# SCH_ReA4091_Rev3_20221019.net
KiCad netlist of a schematic drawn in EasyEDA
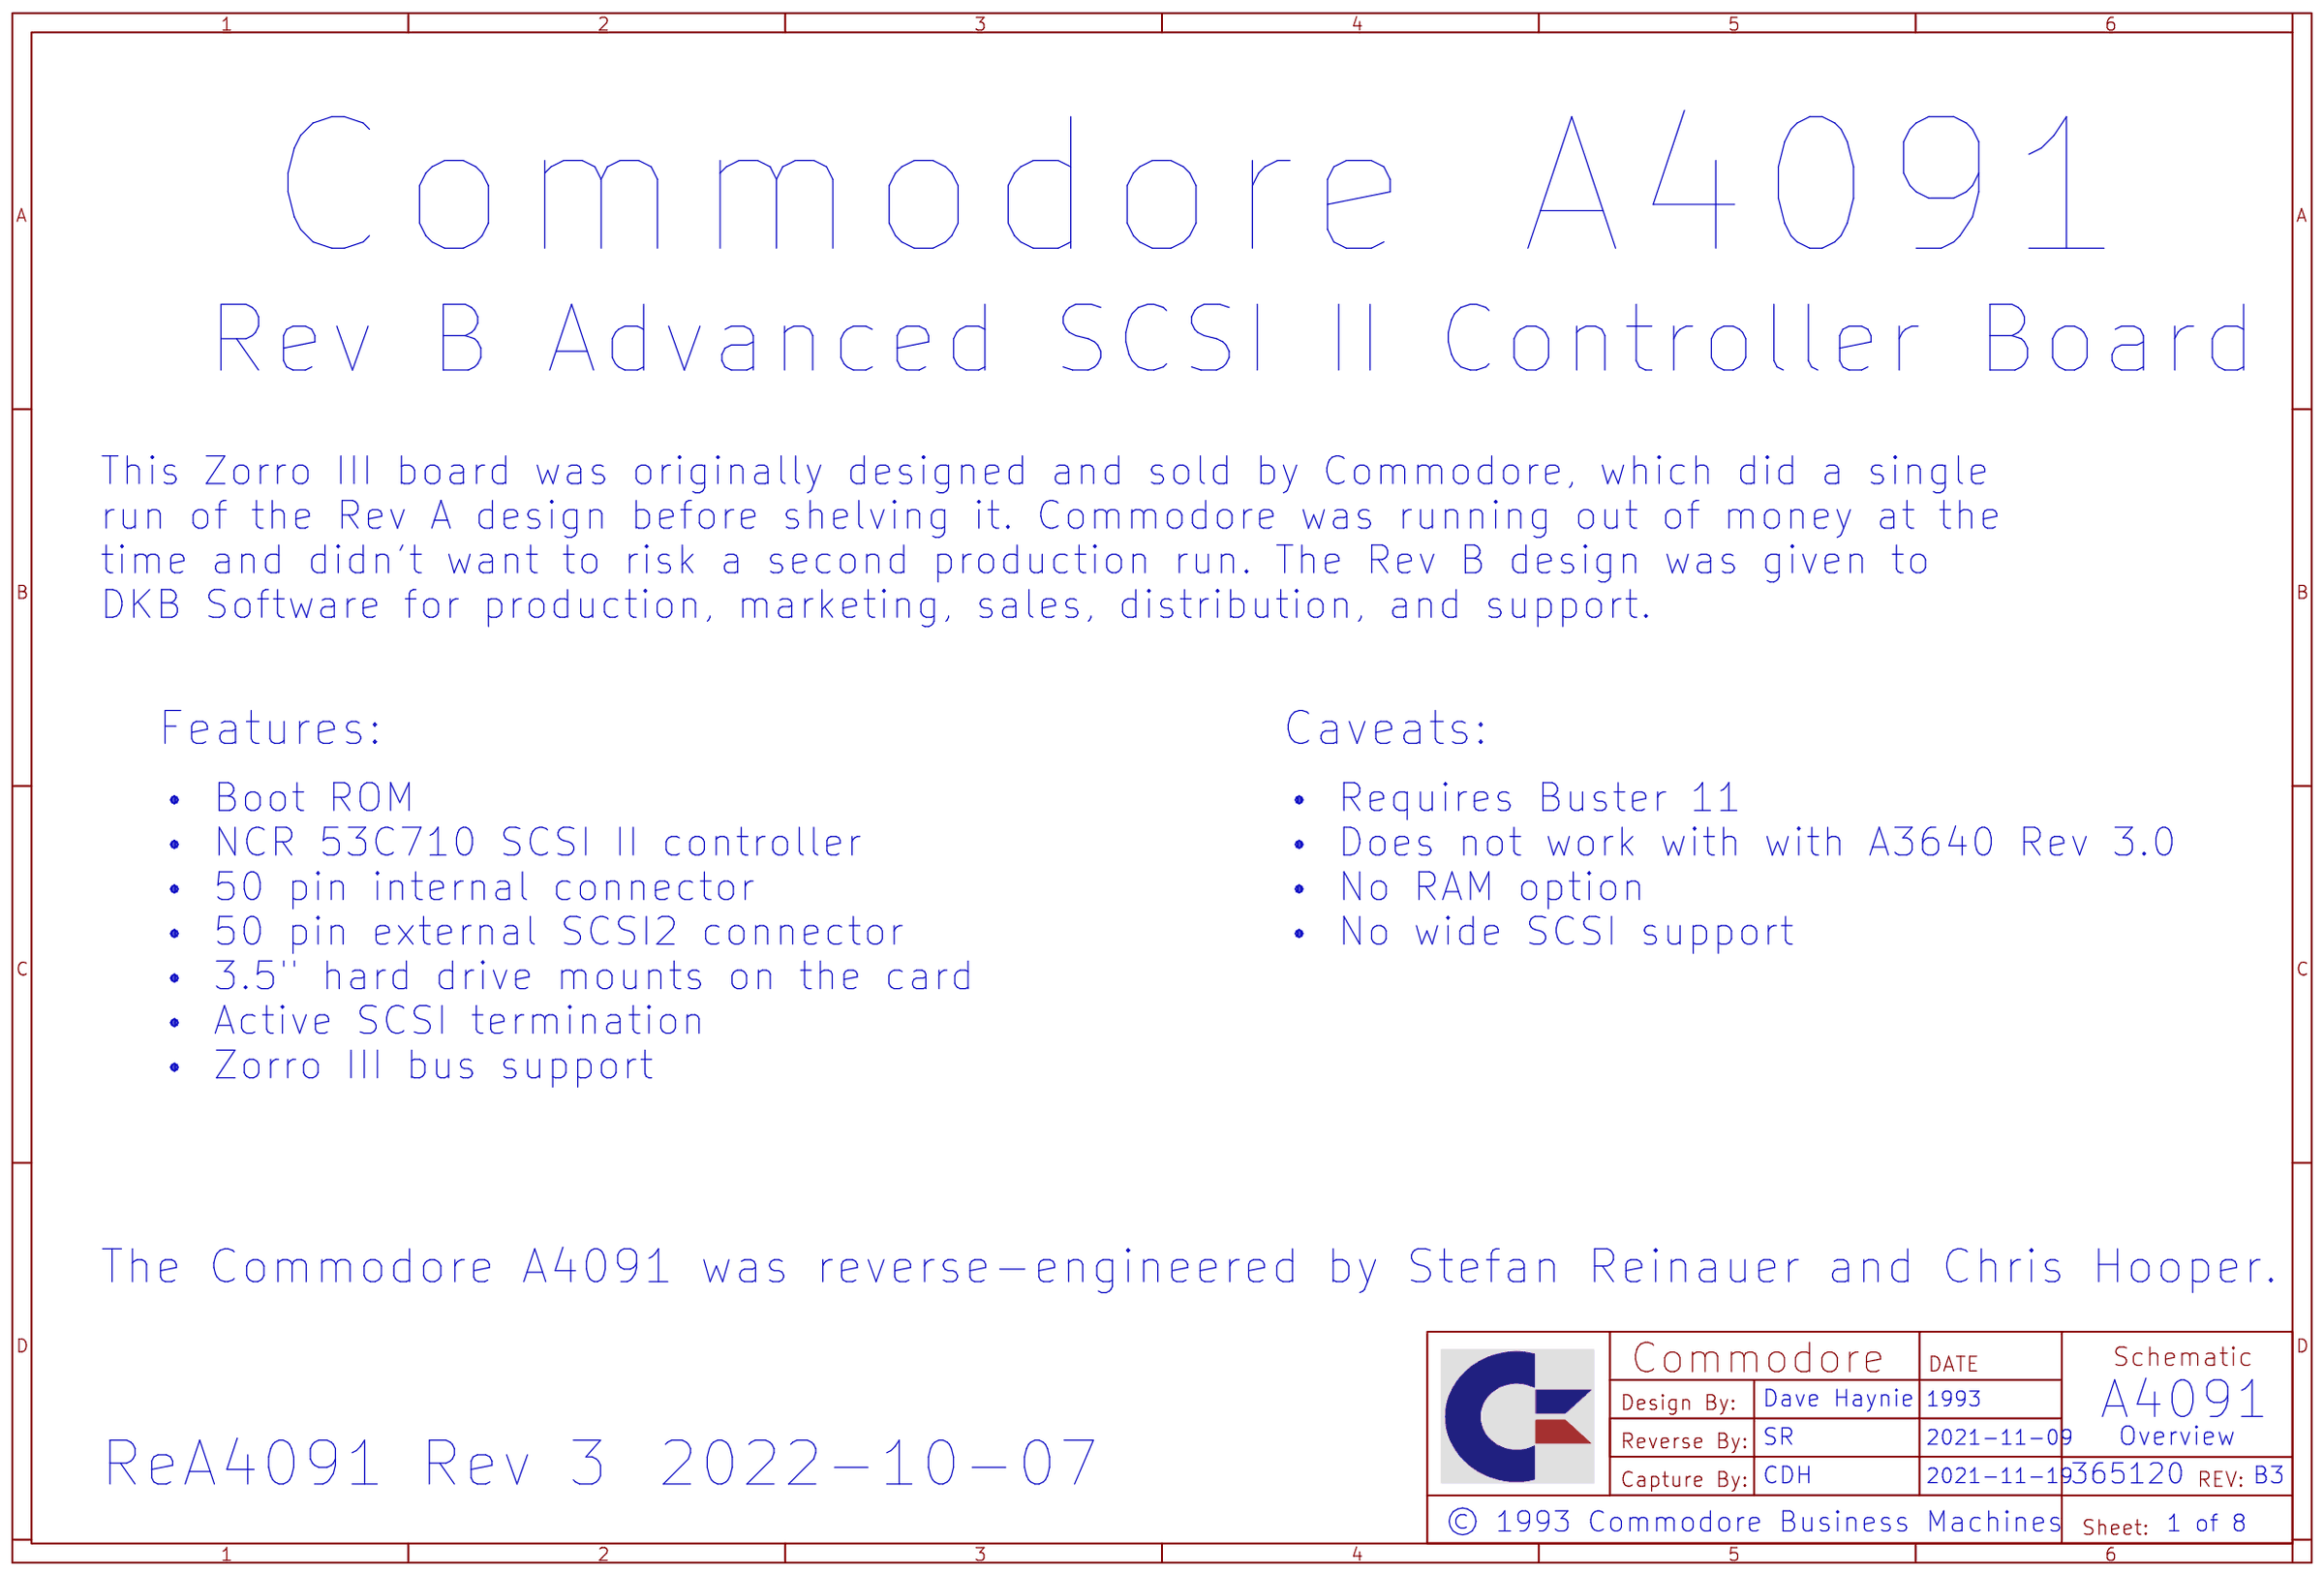
[diagram p0: Overview]
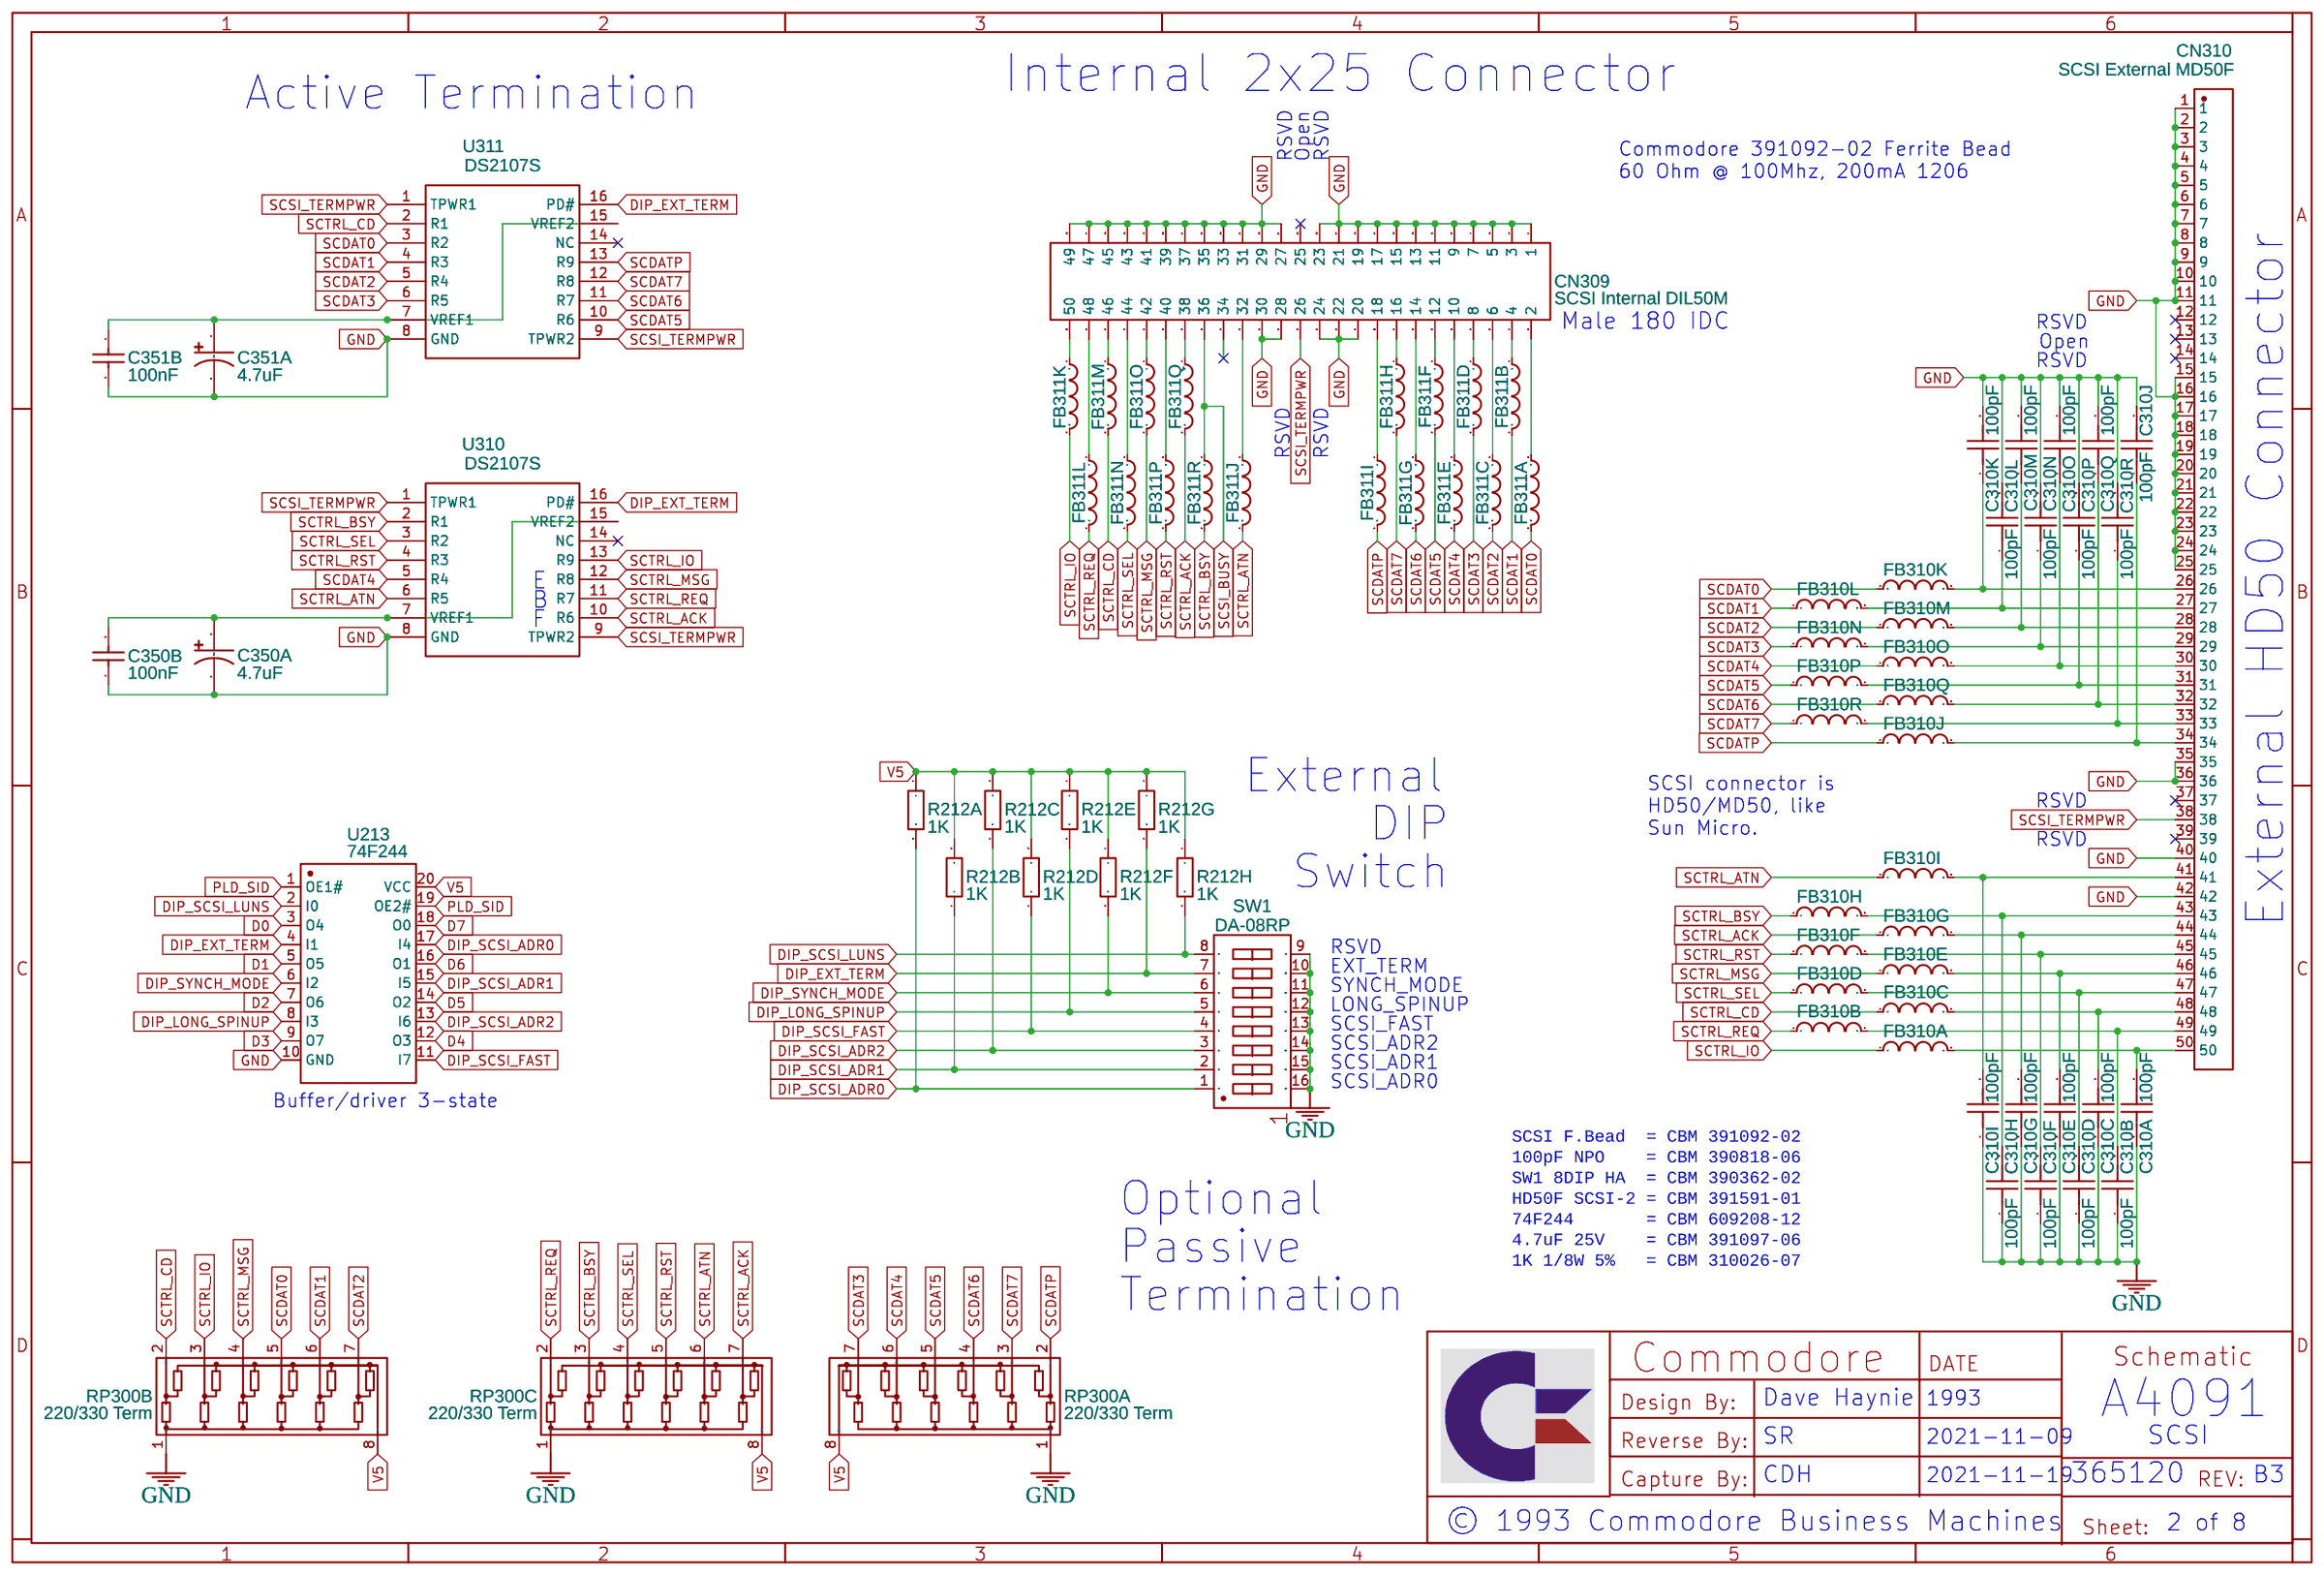
[diagram p1: SCSI]
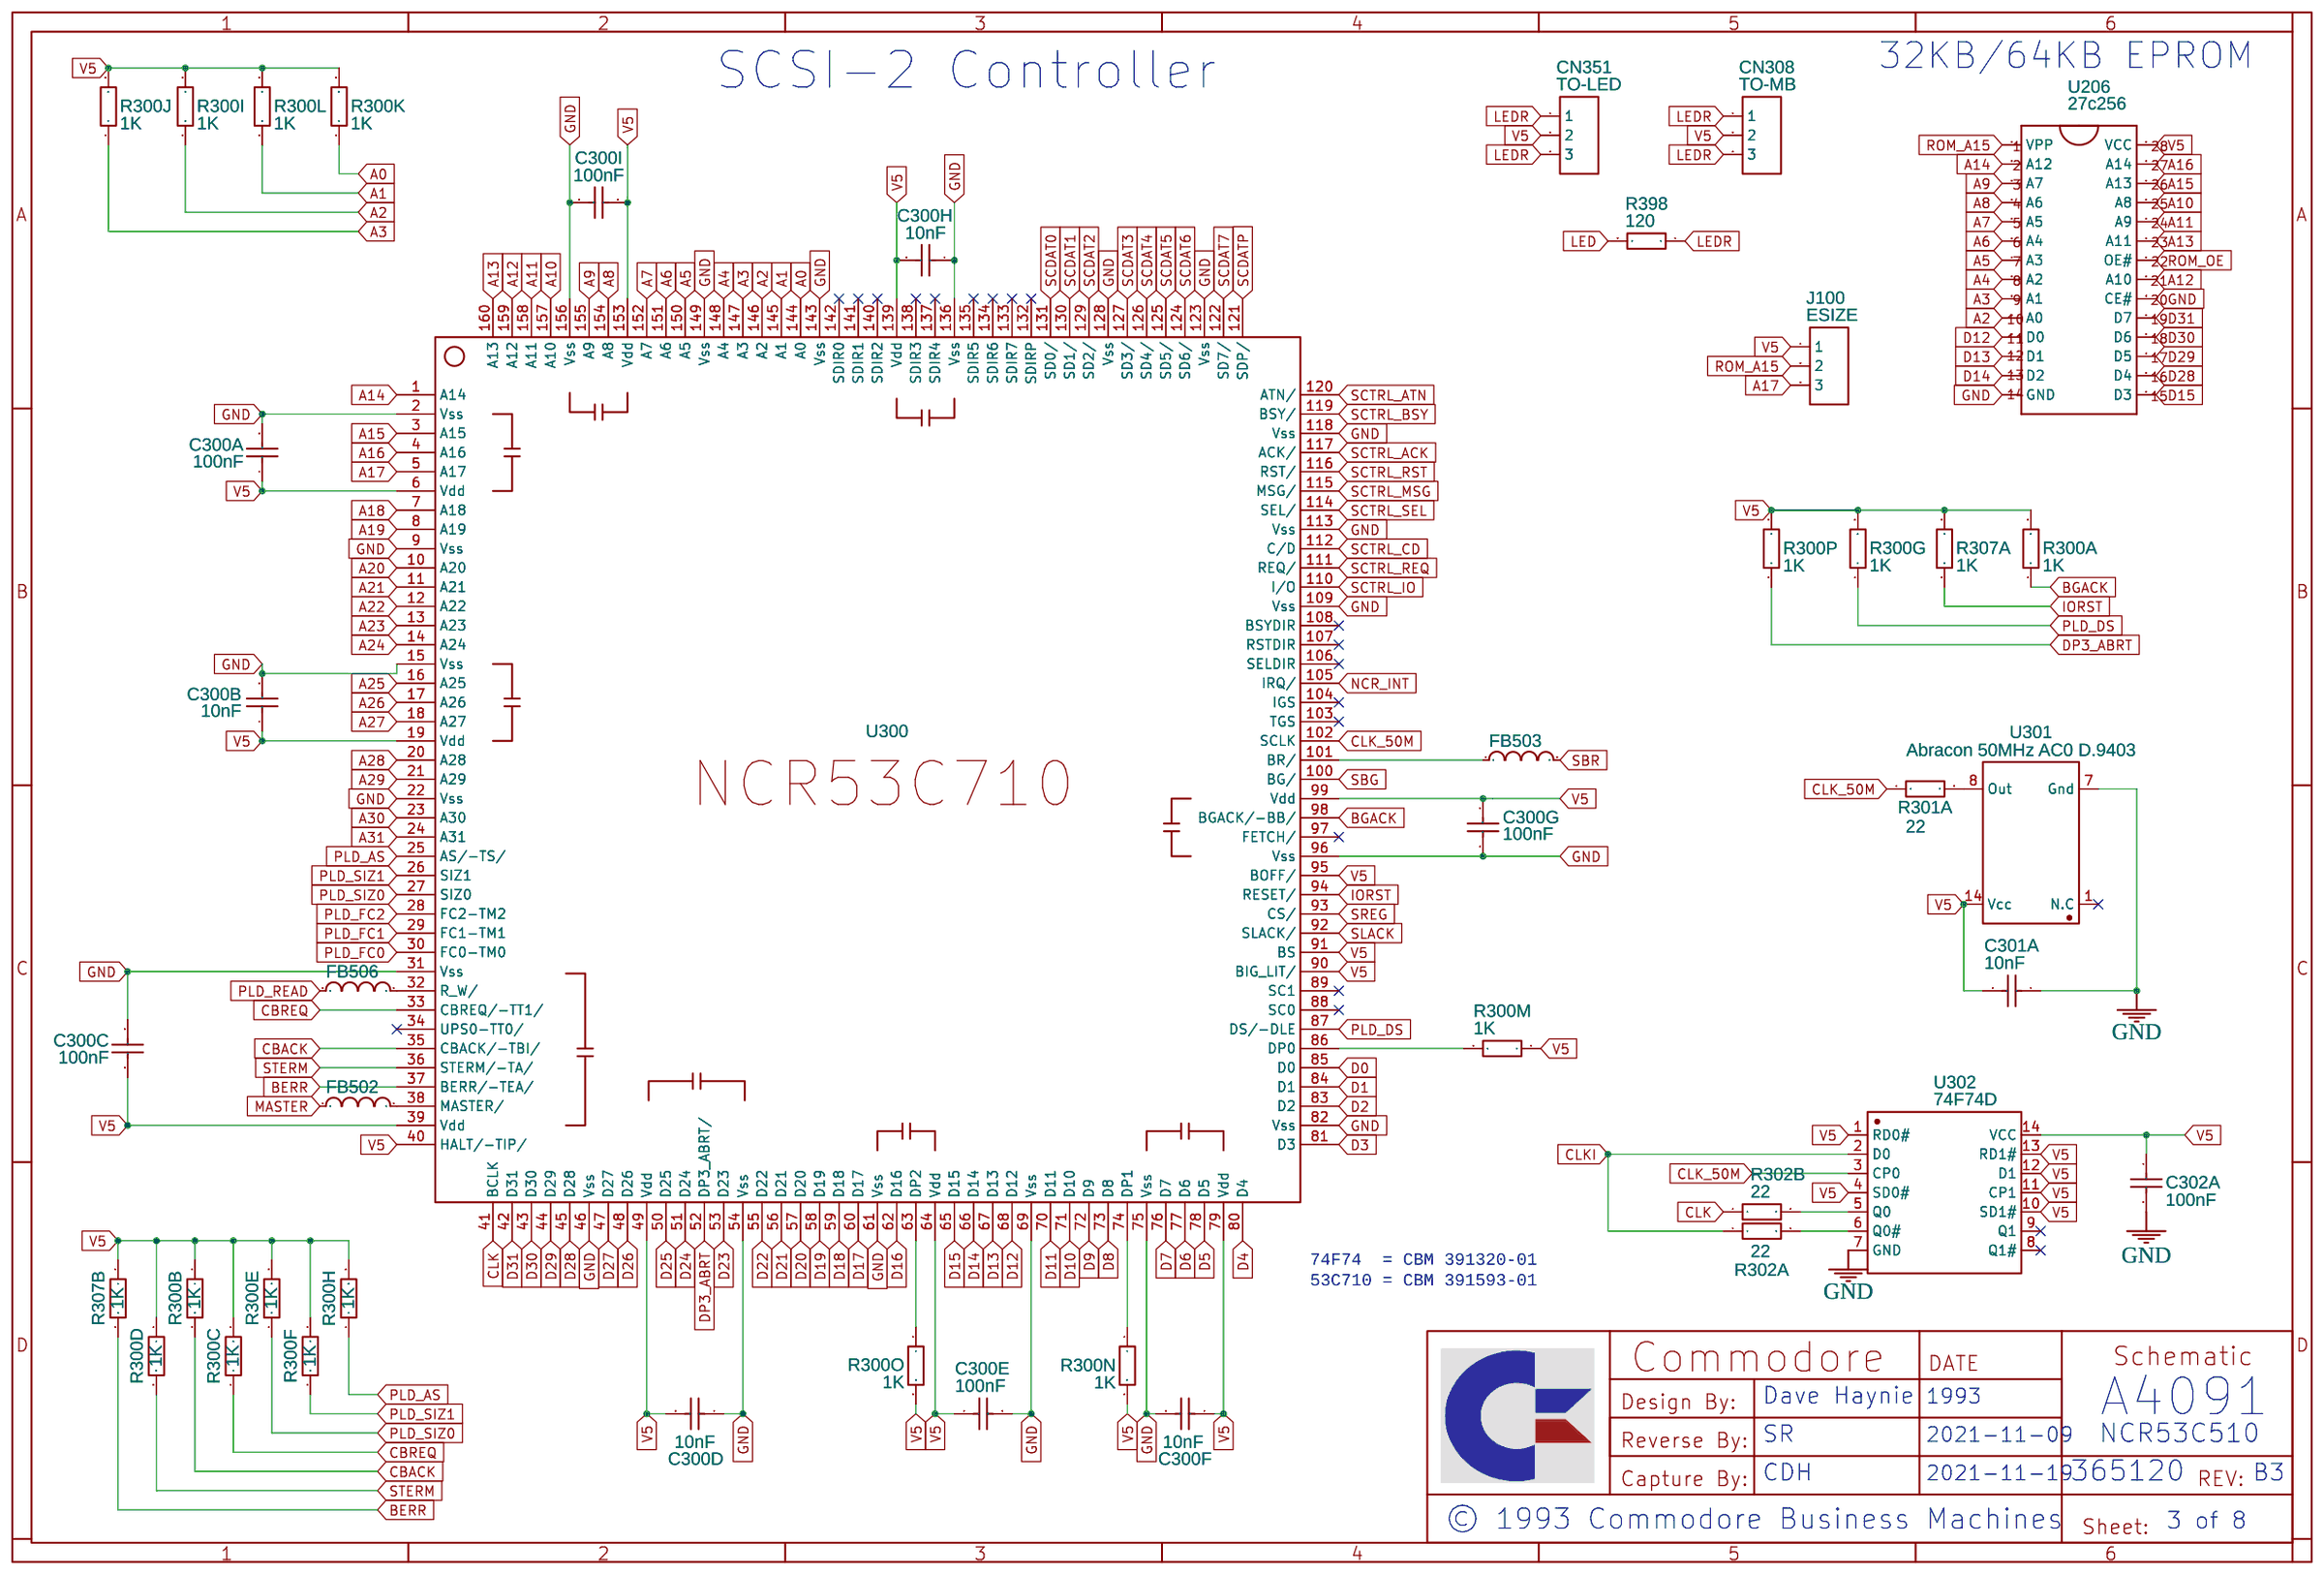
[diagram p2: NCR53C710]
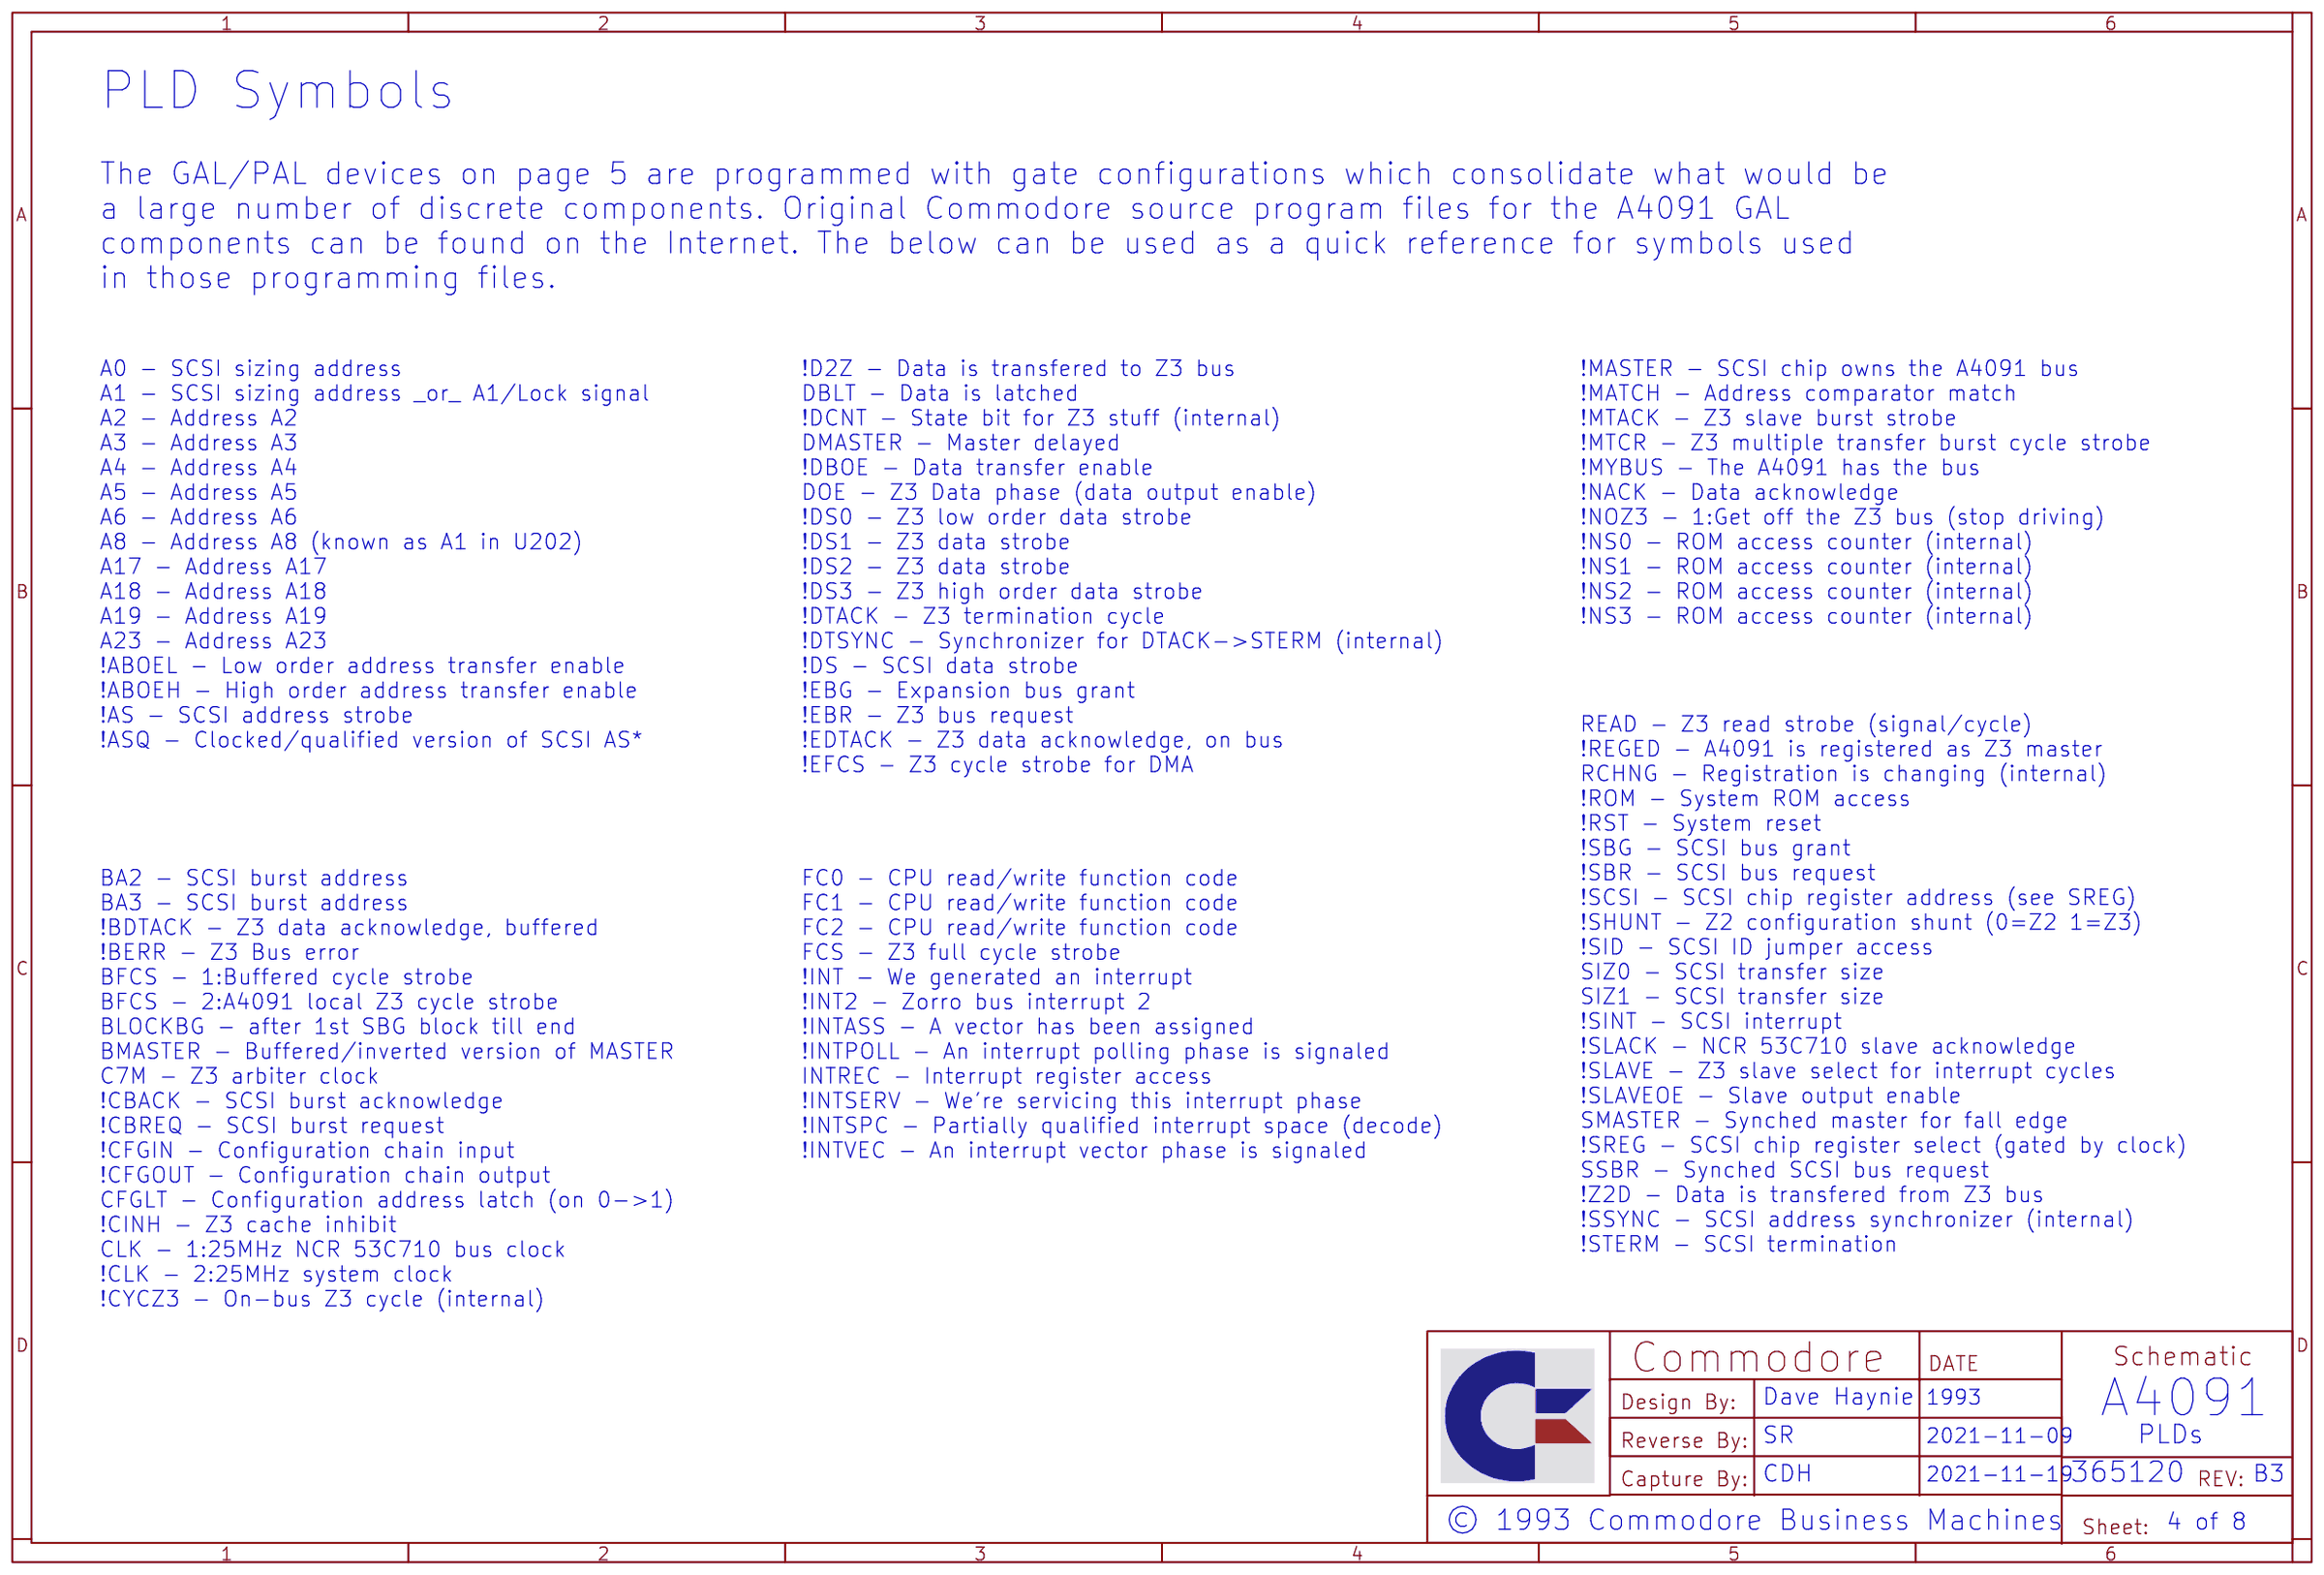
[diagram p3: PLD Symbols]
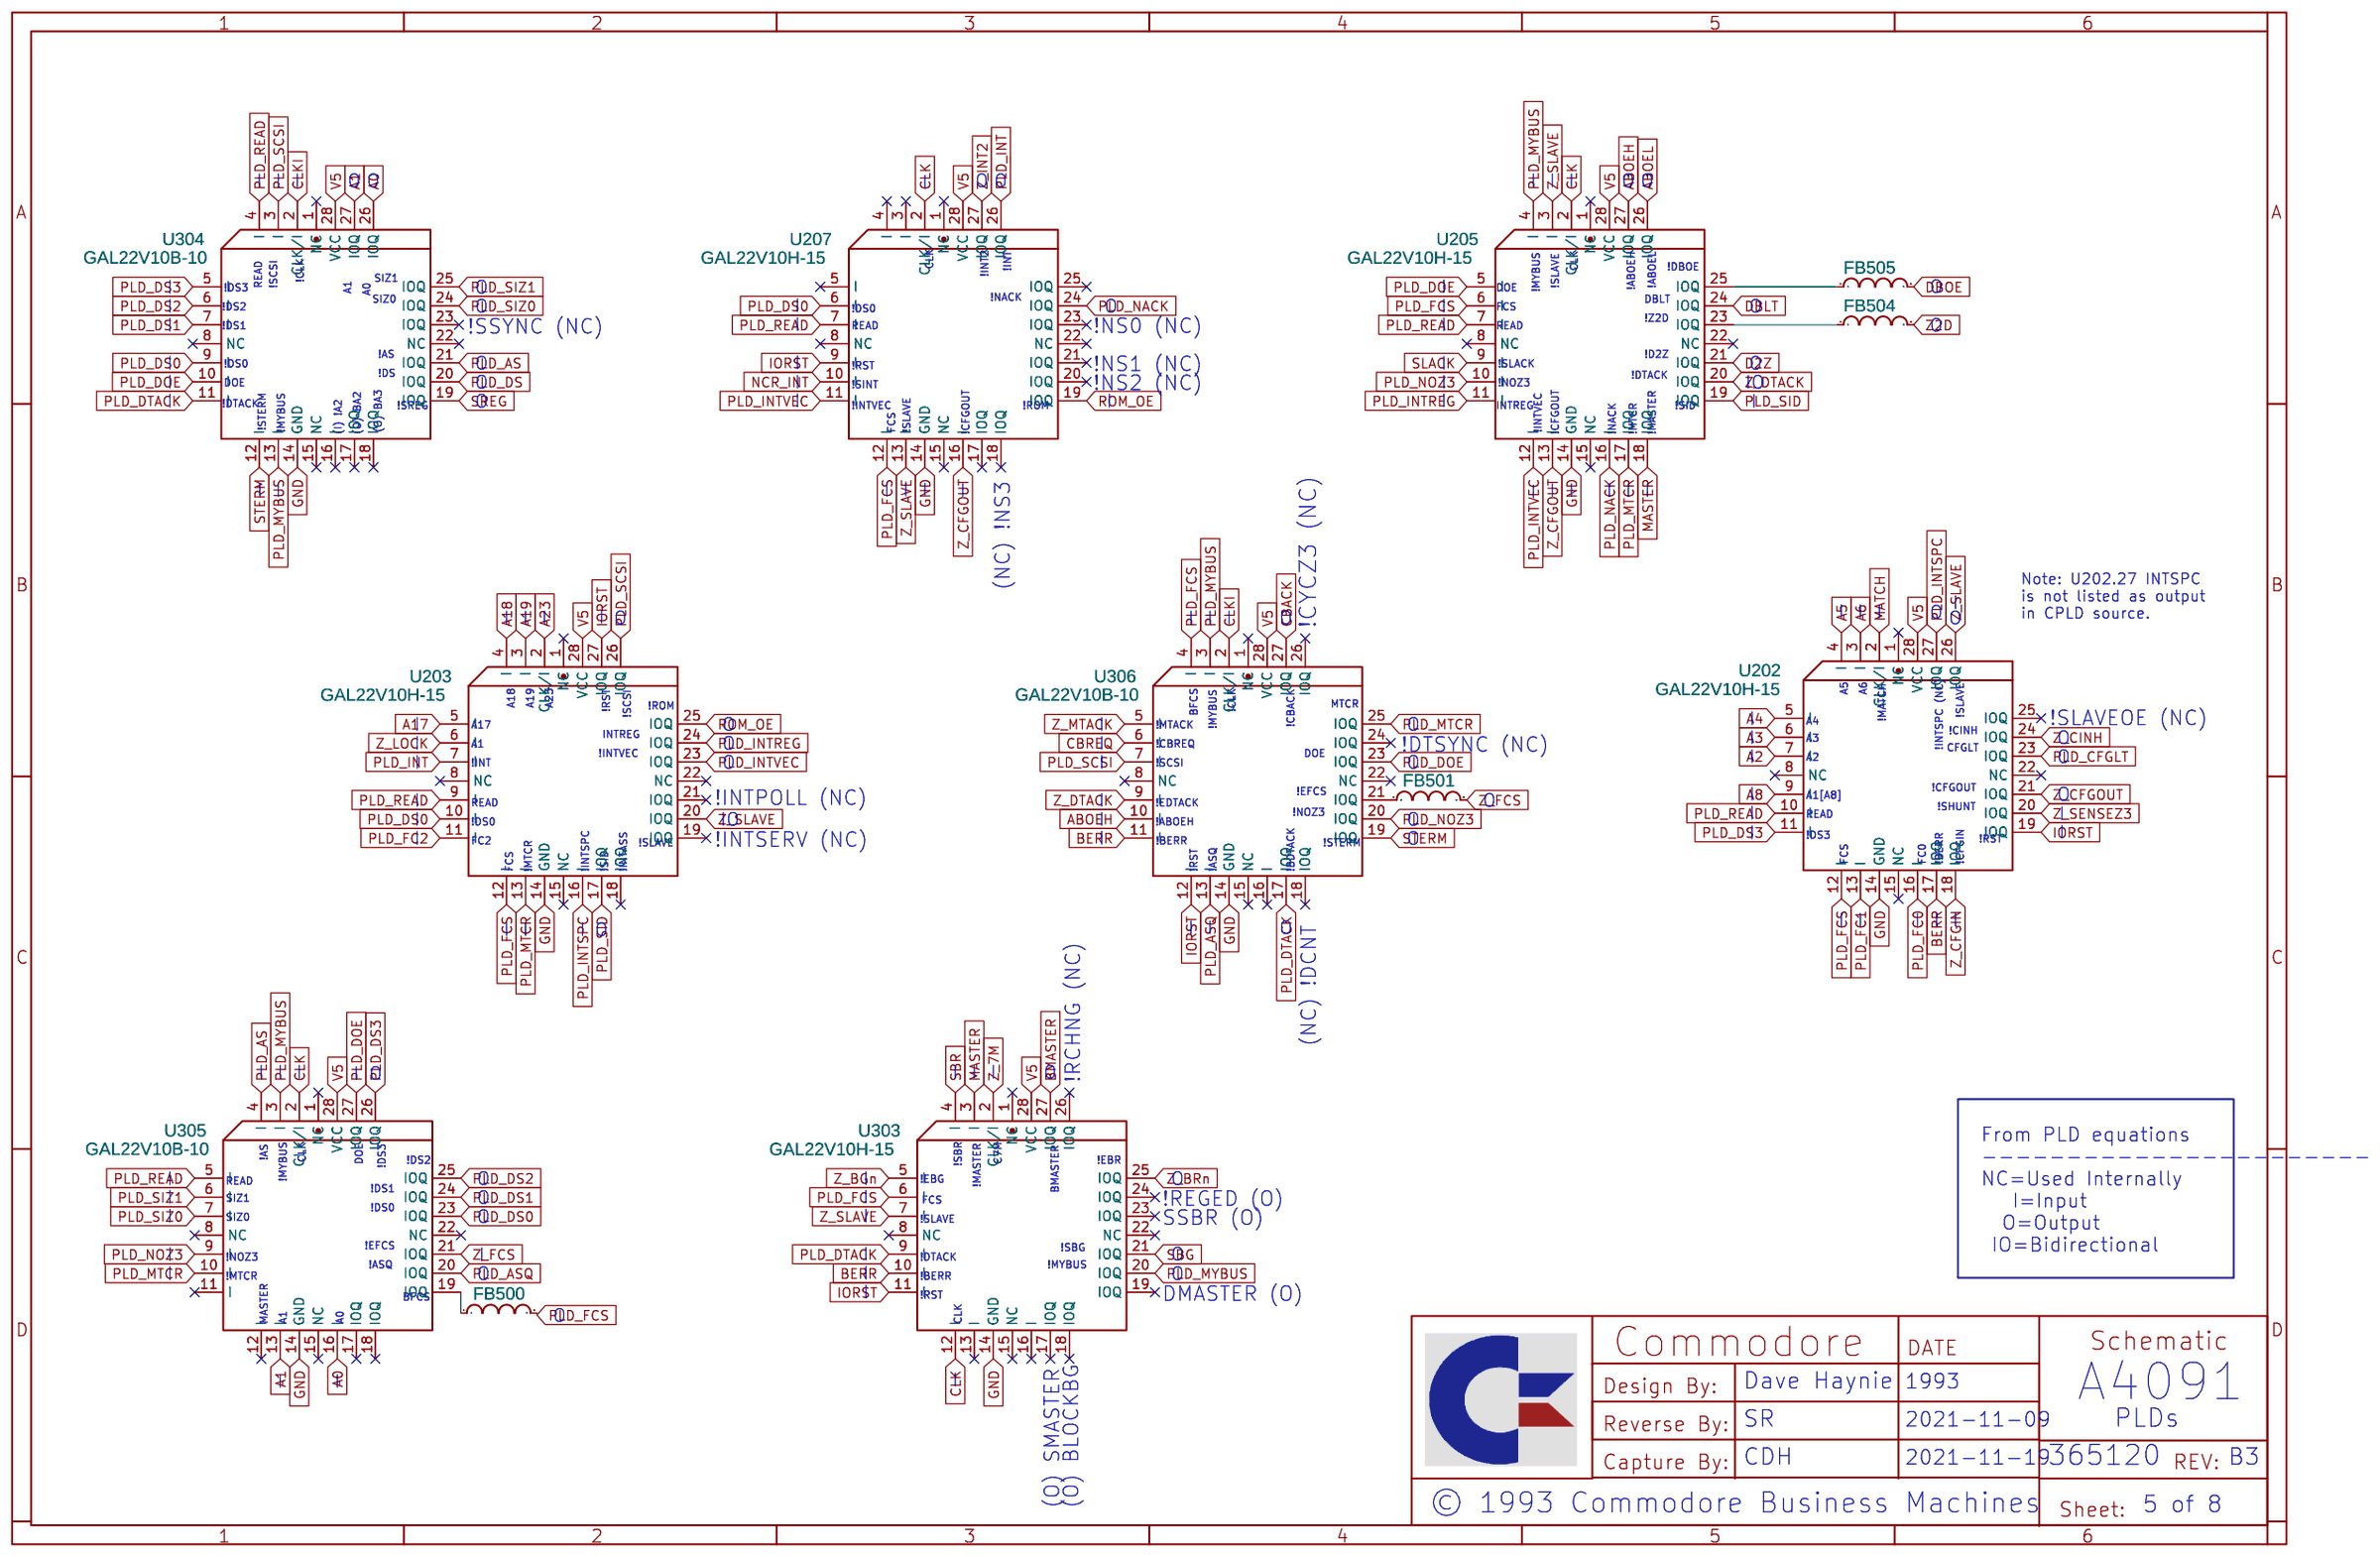
[diagram p4: PLDs]
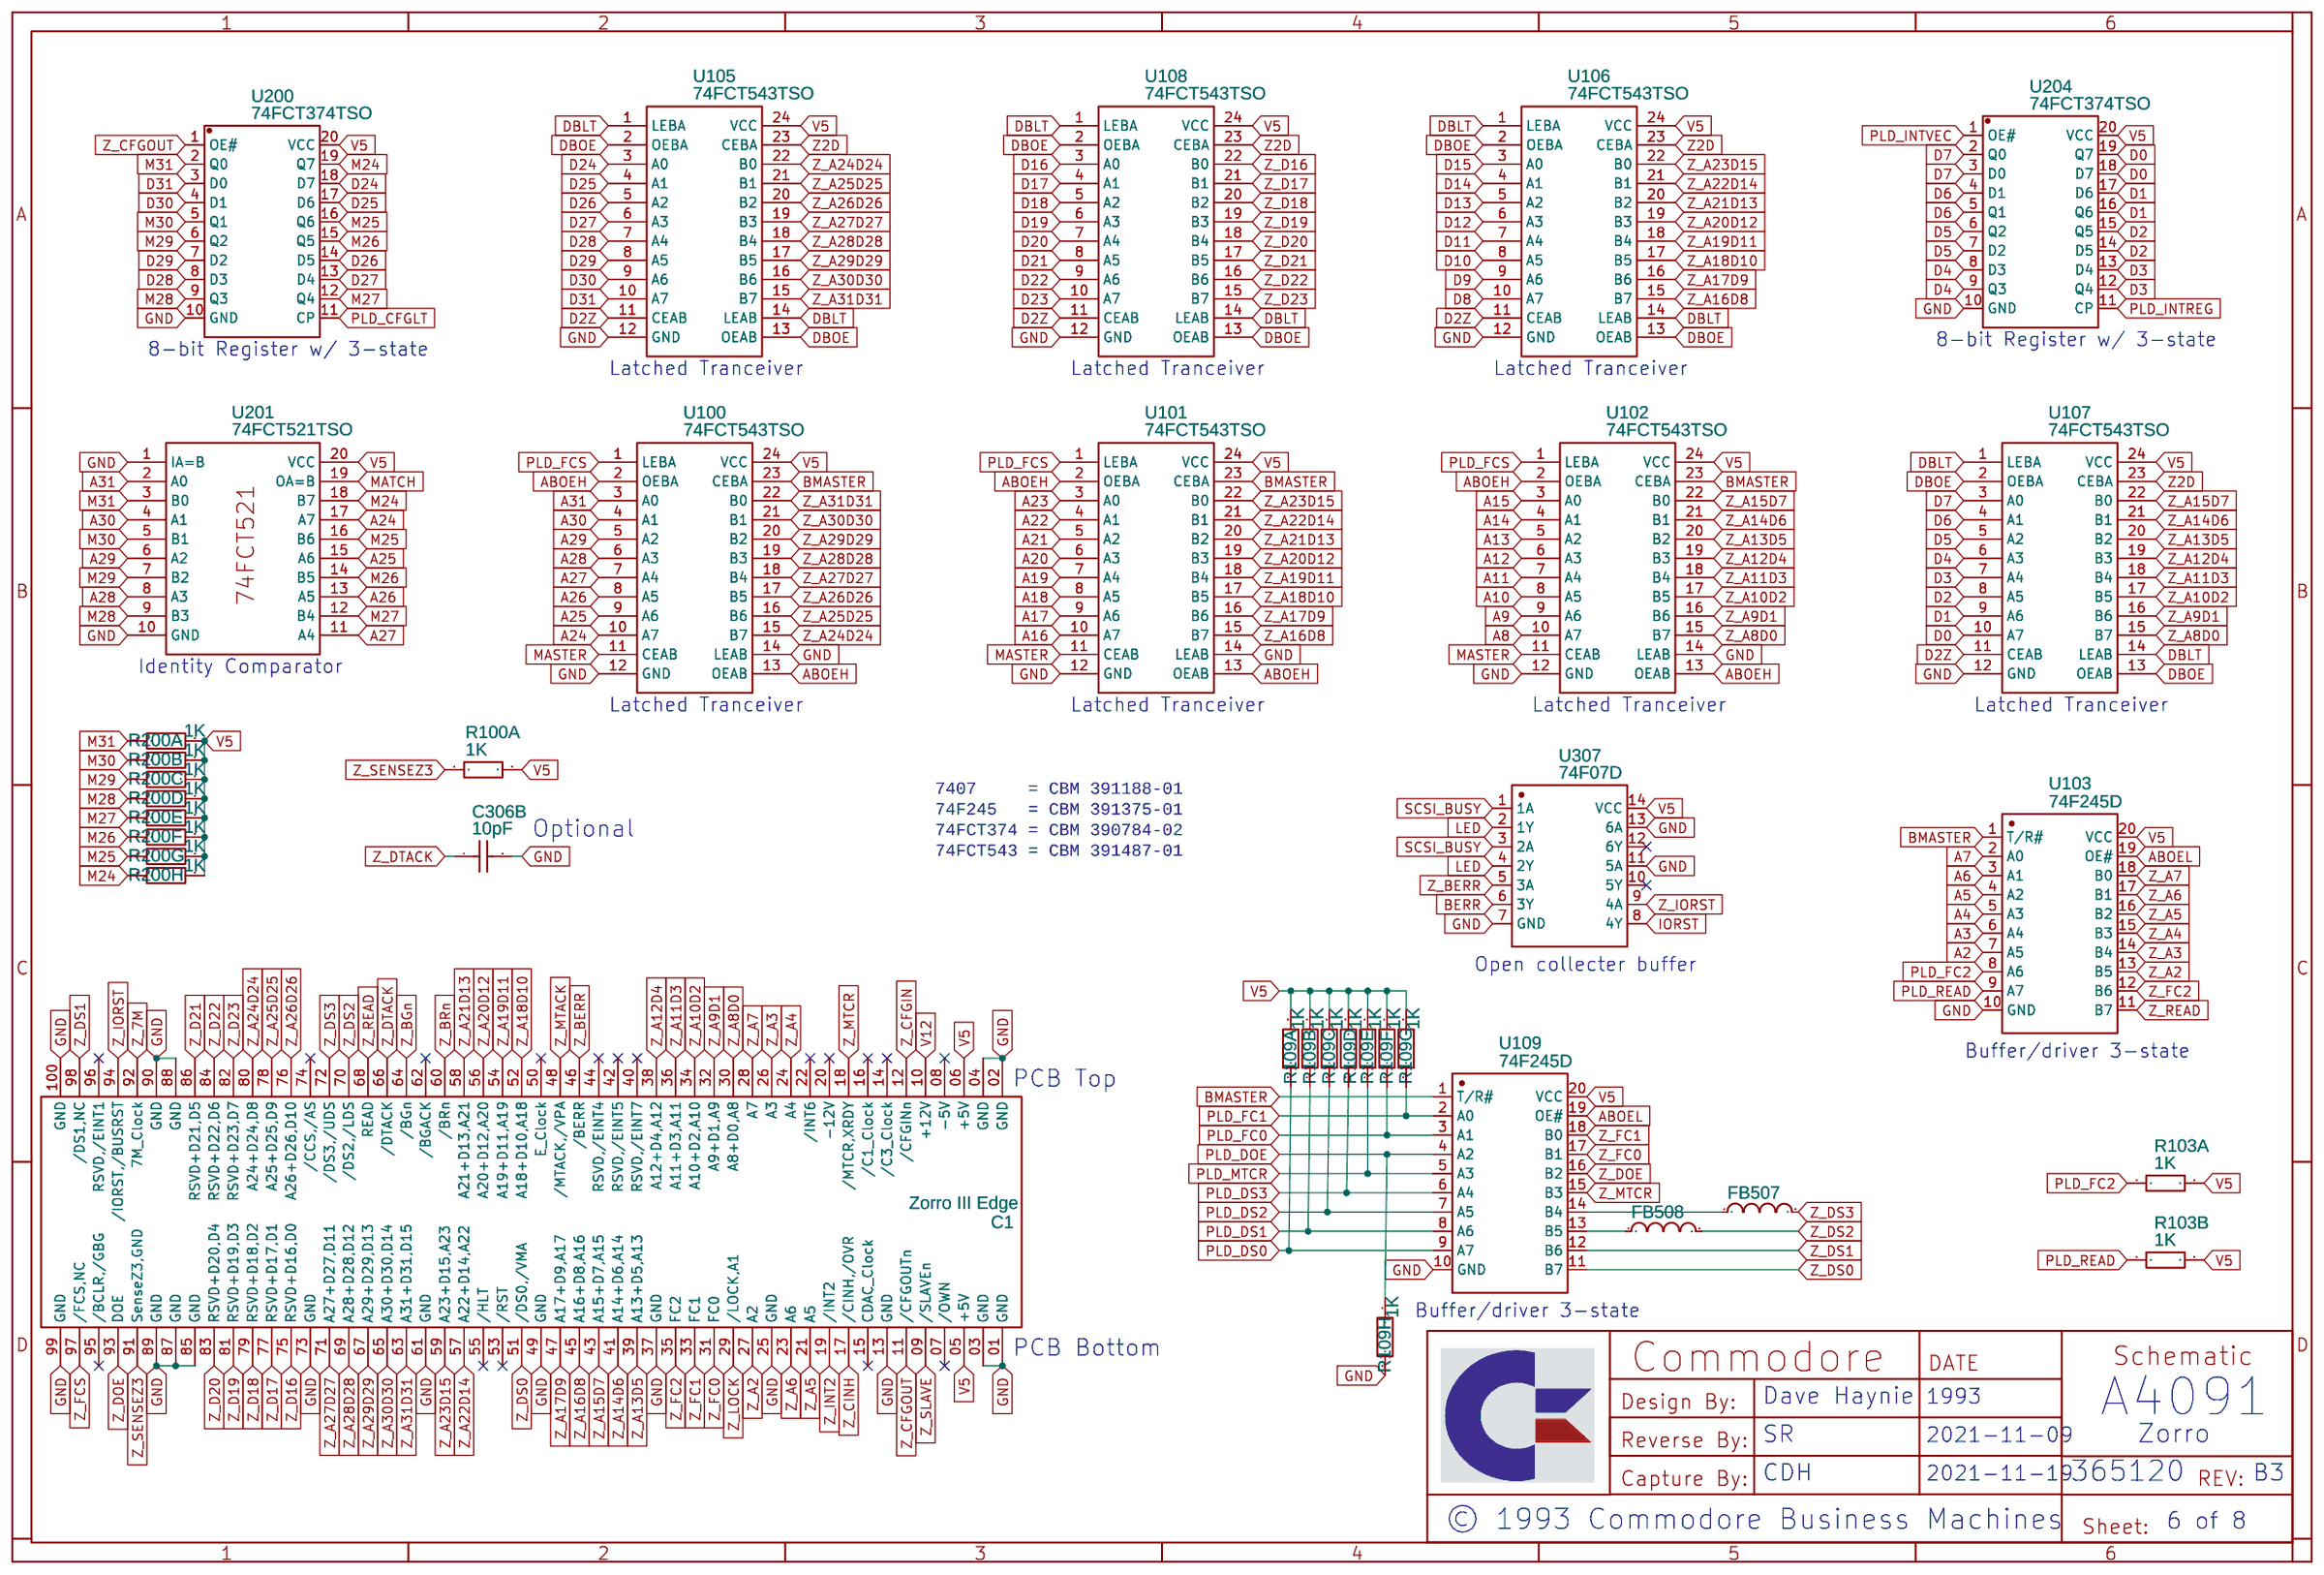
[diagram p5: Zorro]
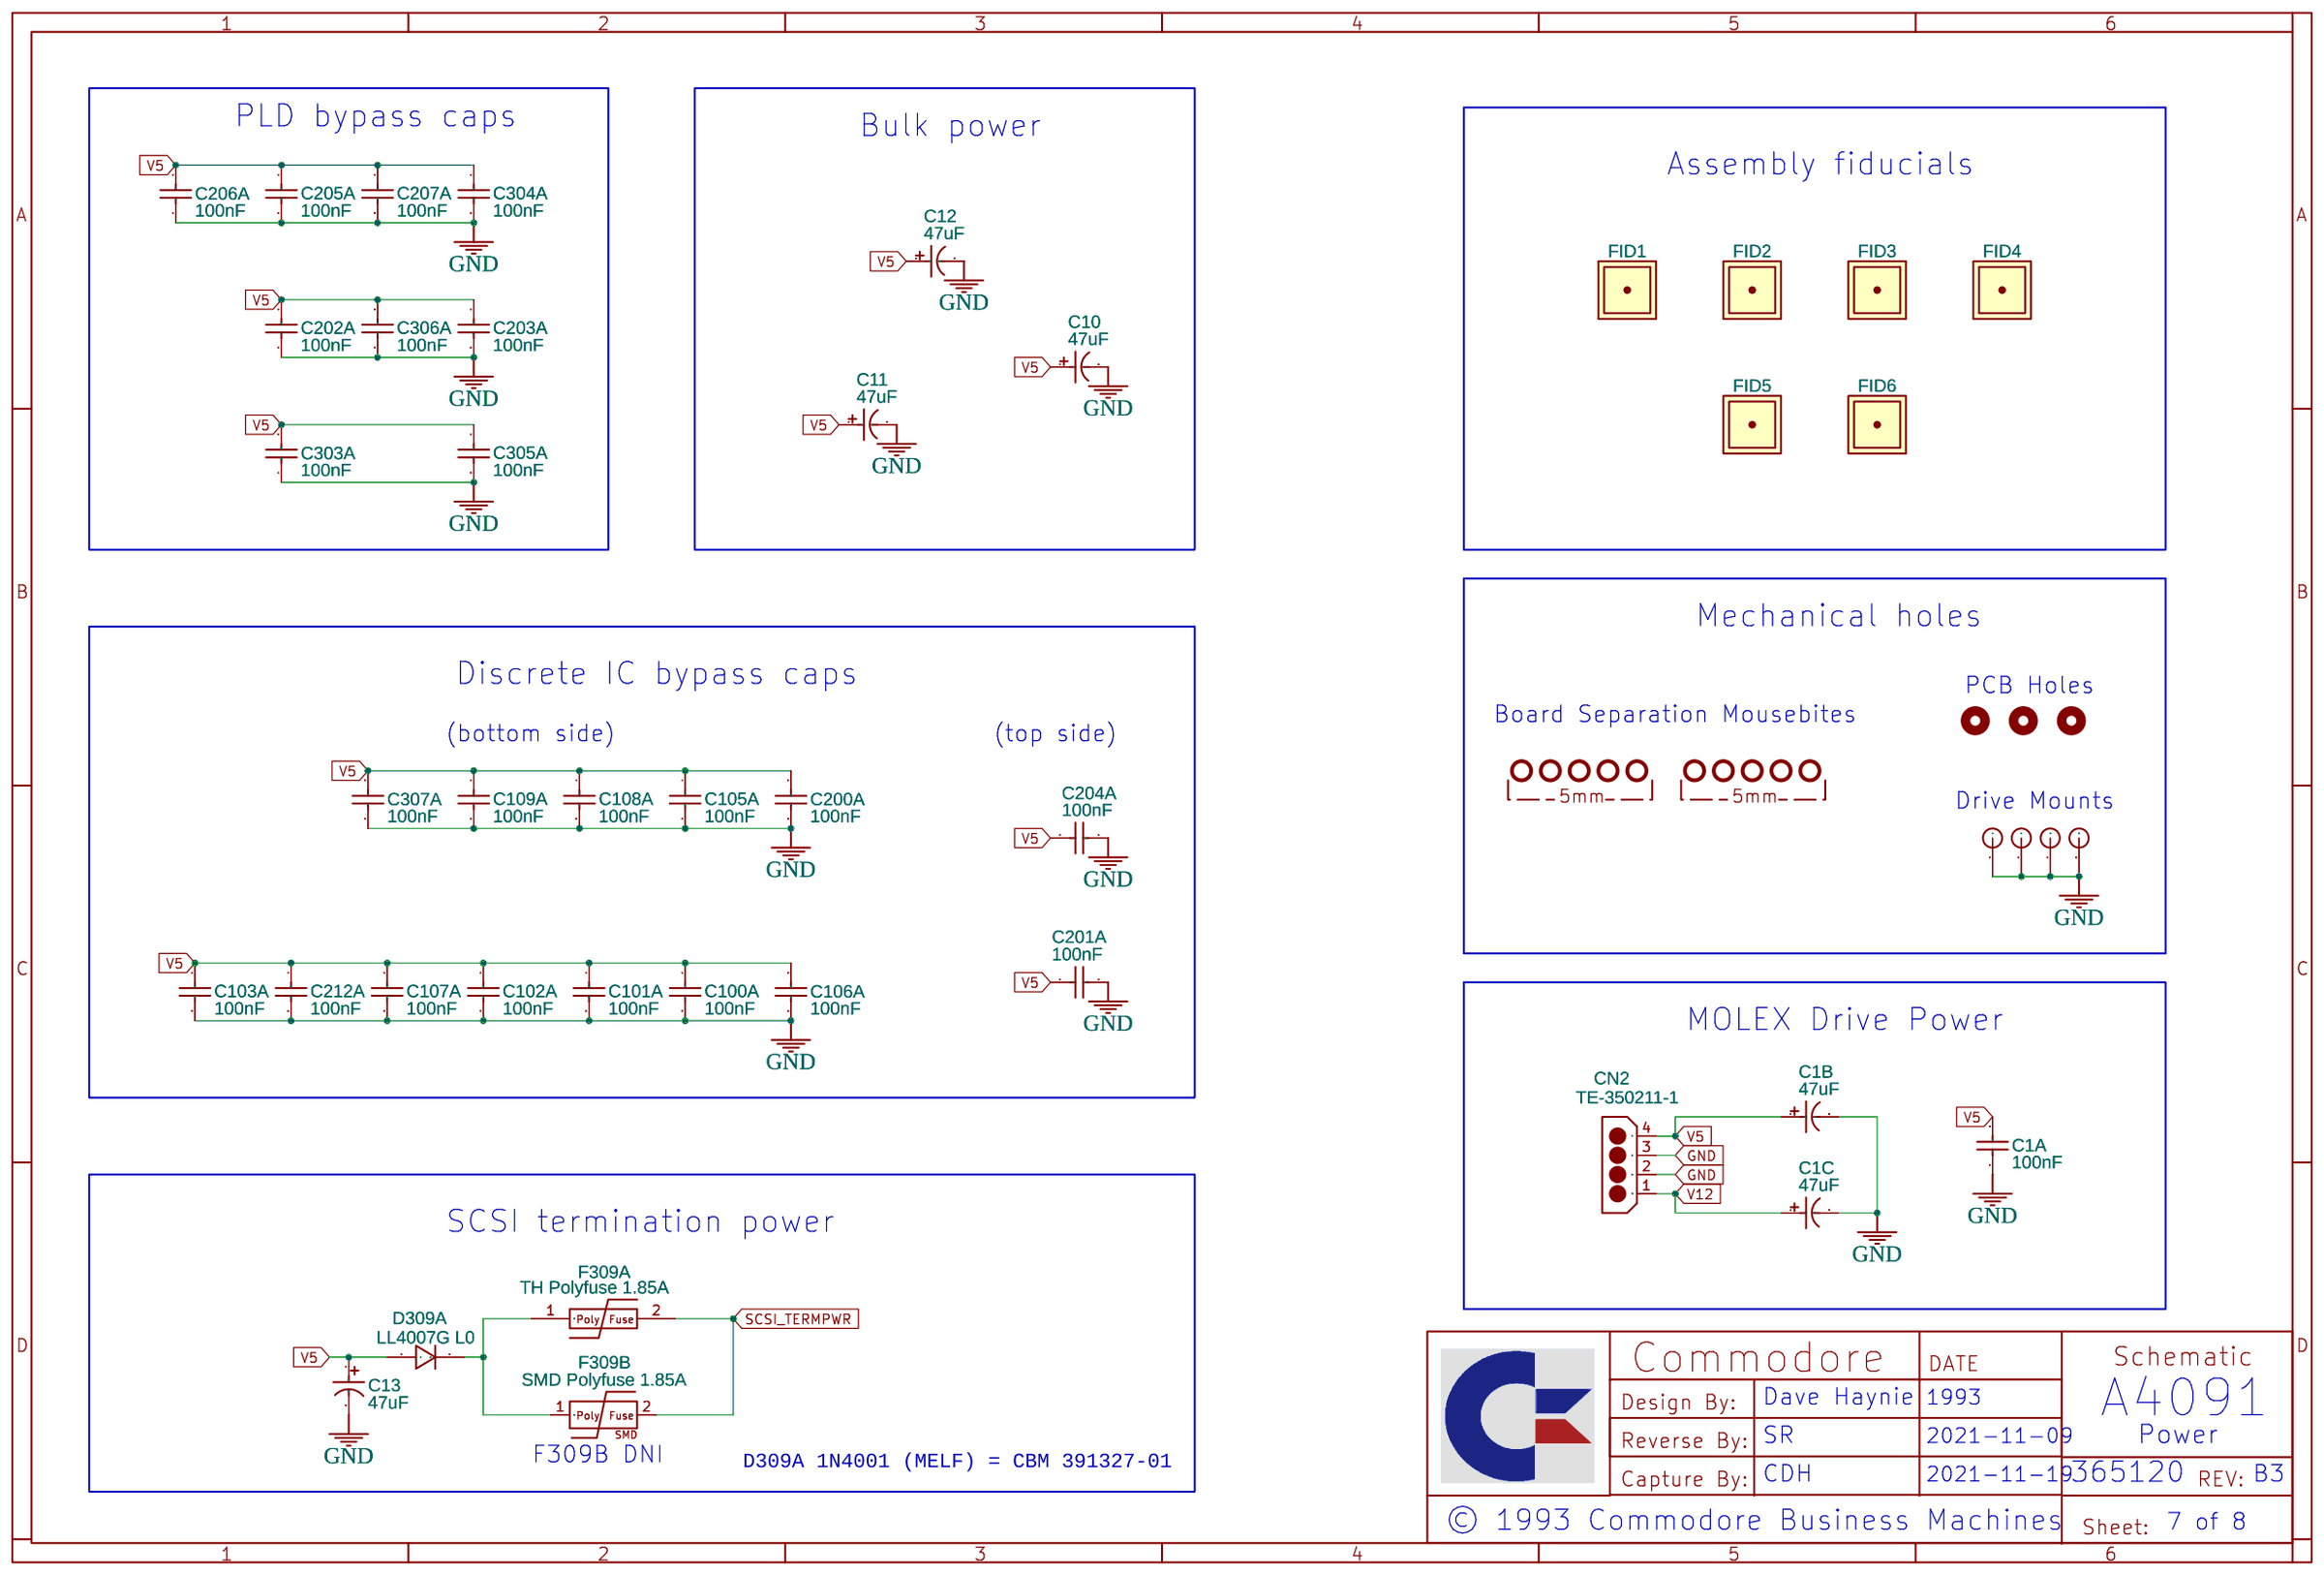
[diagram p6: Power]
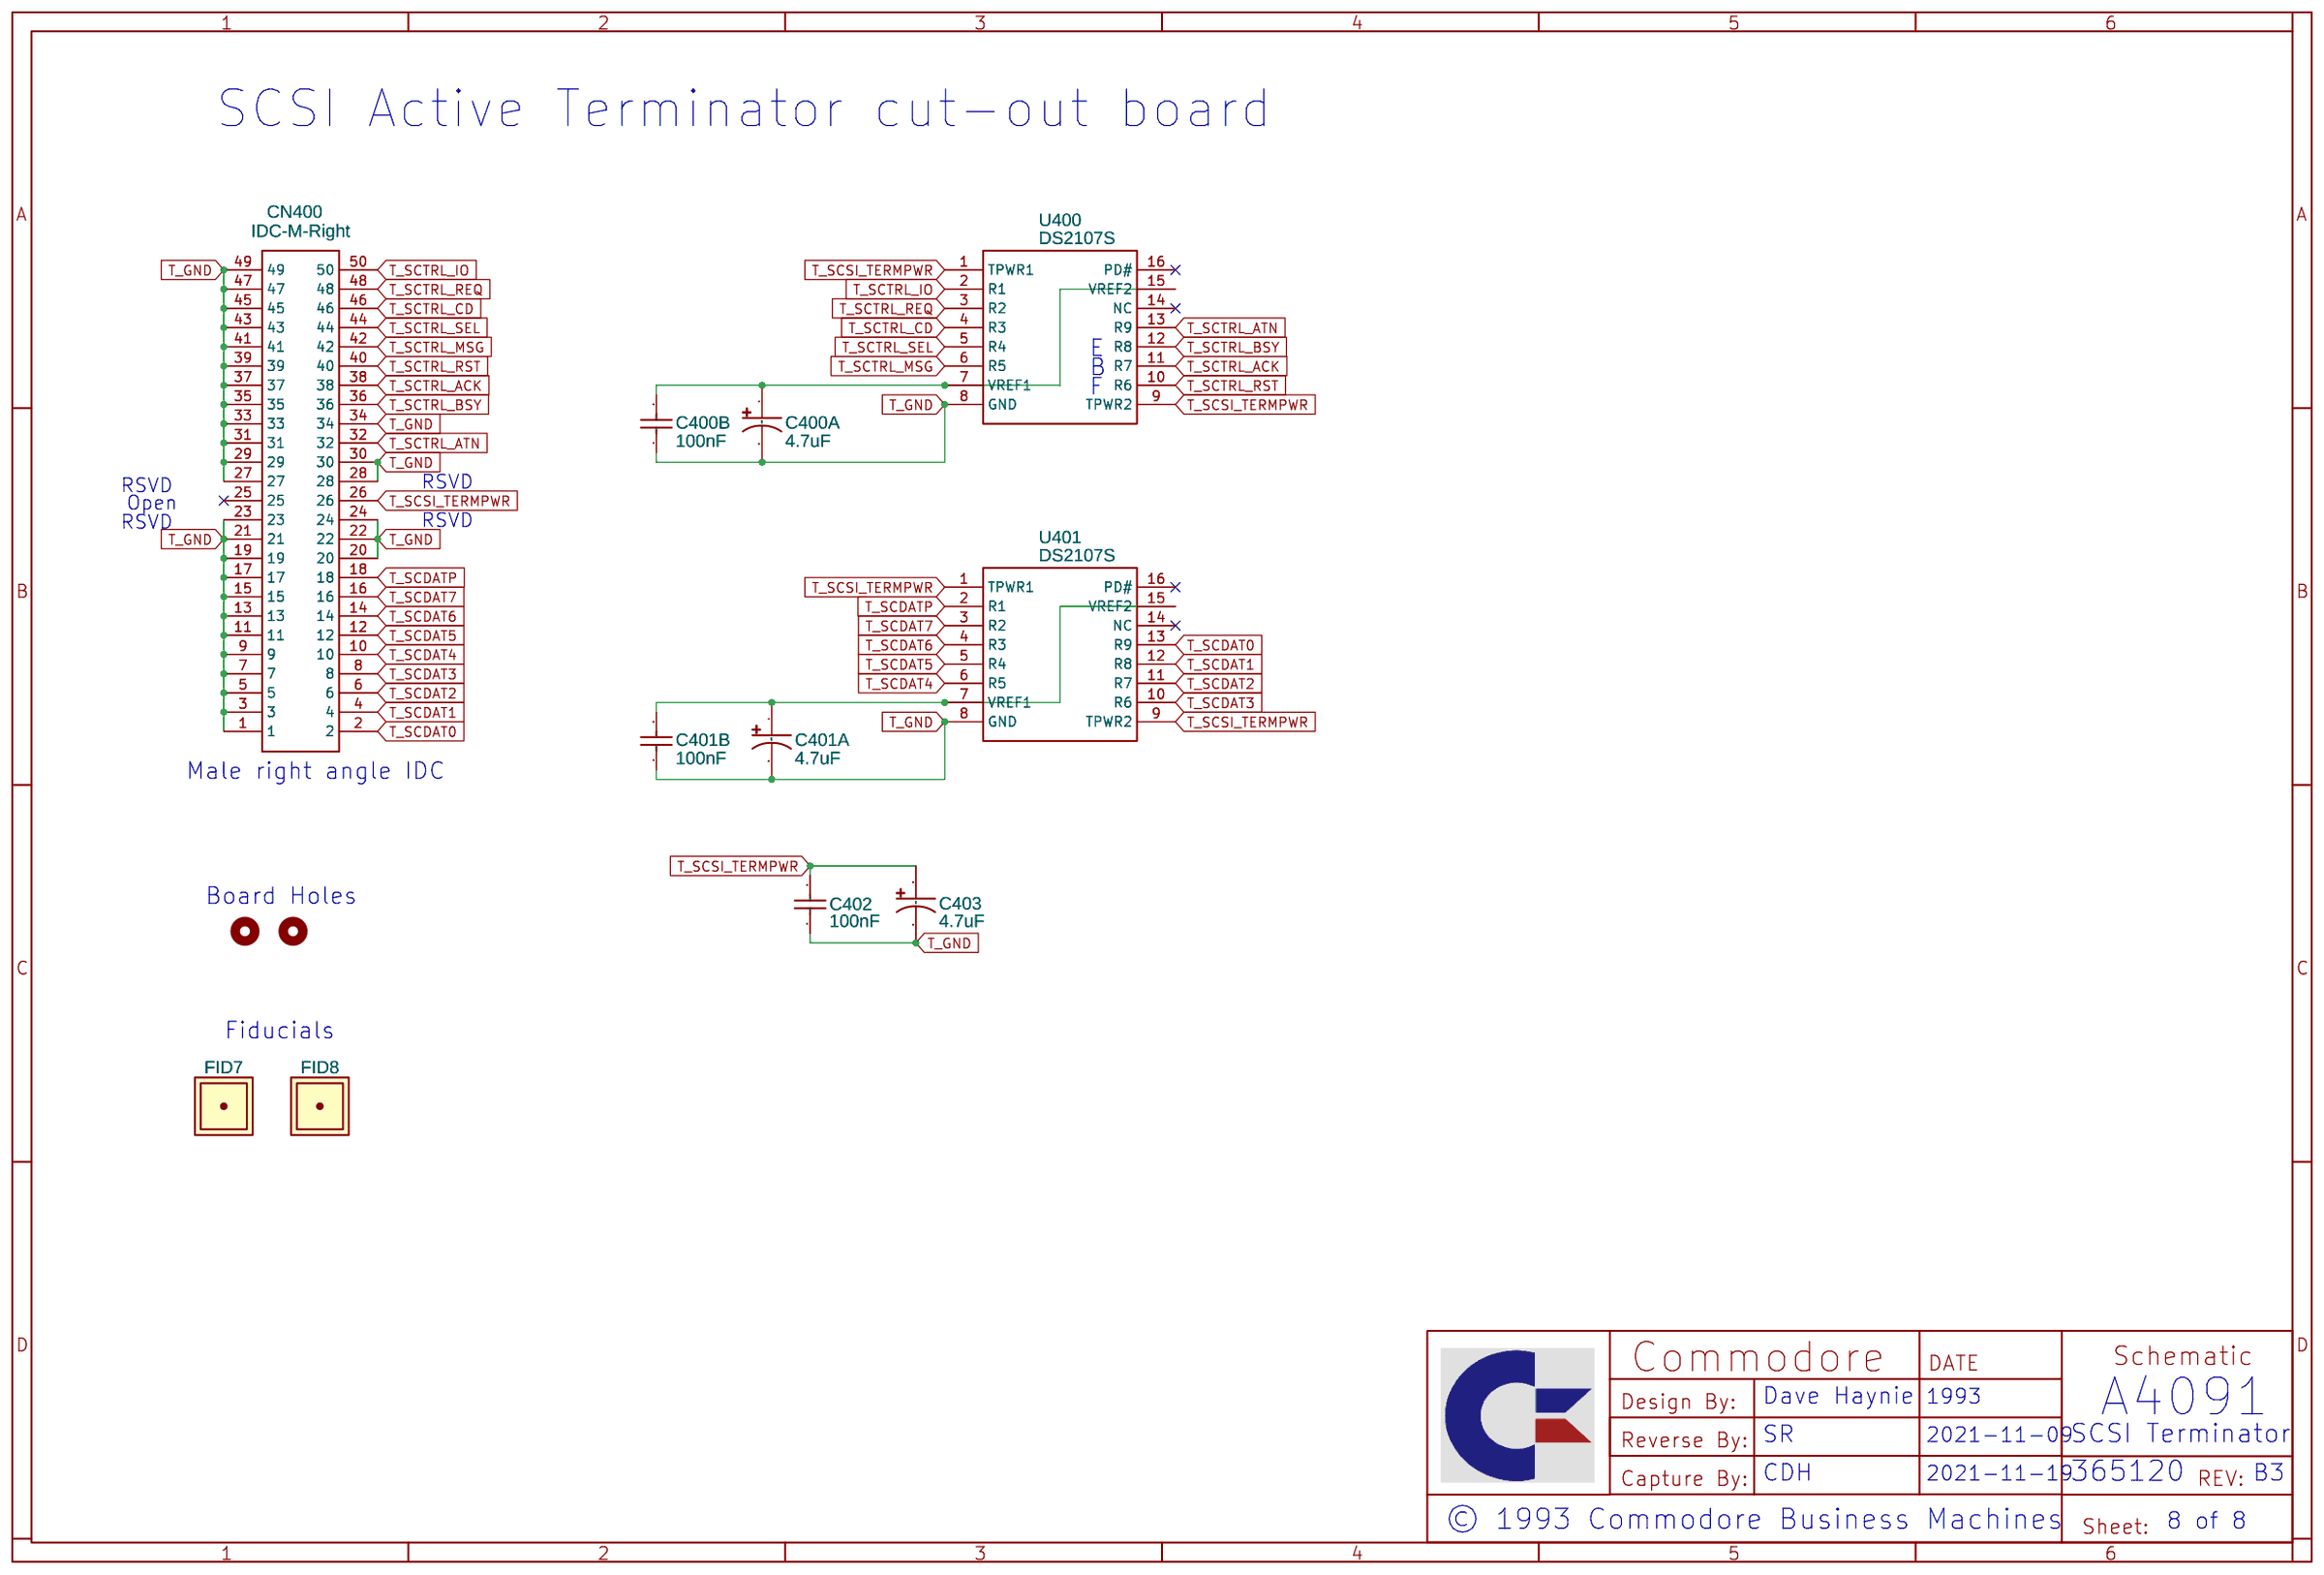
[diagram p7: SCSI Term]

(export (version "E")
  (design (tool "Eeschema 10.0.6"))
  (components
    (comp (ref "C310A")
      (value "100pF")
      (fields
        (field (name "BOM_Manufacturer Part") "CL31C101JHFNNNE")
        (field (name "BOM_Supplier Part") "C307580")
      )
      (libsource (lib "") (part "CL31C101JHFNNNE_13"))
    )
    (comp (ref "C310B")
      (value "100pF")
      (fields
        (field (name "BOM_Manufacturer Part") "CL31C101JHFNNNE")
        (field (name "BOM_Supplier Part") "C307580")
      )
      (libsource (lib "") (part "CL31C101JHFNNNE_3"))
    )
    (comp (ref "C310C")
      (value "100pF")
      (fields
        (field (name "BOM_Manufacturer Part") "CL31C101JHFNNNE")
        (field (name "BOM_Supplier Part") "C307580")
      )
      (libsource (lib "") (part "CL31C101JHFNNNE_7"))
    )
    (comp (ref "C310D")
      (value "100pF")
      (fields
        (field (name "BOM_Manufacturer Part") "CL31C101JHFNNNE")
        (field (name "BOM_Supplier Part") "C307580")
      )
      (libsource (lib "") (part "CL31C101JHFNNNE"))
    )
    (comp (ref "C310E")
      (value "100pF")
      (fields
        (field (name "BOM_Manufacturer Part") "CL31C101JHFNNNE")
        (field (name "BOM_Supplier Part") "C307580")
      )
      (libsource (lib "") (part "CL31C101JHFNNNE_4"))
    )
    (comp (ref "C310F")
      (value "100pF")
      (fields
        (field (name "BOM_Manufacturer Part") "CL31C101JHFNNNE")
        (field (name "BOM_Supplier Part") "C307580")
      )
      (libsource (lib "") (part "CL31C101JHFNNNE_1"))
    )
    (comp (ref "C310G")
      (value "100pF")
      (fields
        (field (name "BOM_Manufacturer Part") "CL31C101JHFNNNE")
        (field (name "BOM_Supplier Part") "C307580")
      )
      (libsource (lib "") (part "CL31C101JHFNNNE_2"))
    )
    (comp (ref "C310H")
      (value "100pF")
      (fields
        (field (name "BOM_Manufacturer Part") "CL31C101JHFNNNE")
        (field (name "BOM_Supplier Part") "C307580")
      )
      (libsource (lib "") (part "CL31C101JHFNNNE_14"))
    )
    (comp (ref "C310I")
      (value "100pF")
      (fields
        (field (name "BOM_Manufacturer Part") "CL31C101JHFNNNE")
        (field (name "BOM_Supplier Part") "C307580")
      )
      (libsource (lib "") (part "CL31C101JHFNNNE_17"))
    )
    (comp (ref "C310J")
      (value "100pF")
      (fields
        (field (name "BOM_Manufacturer Part") "CL31C101JHFNNNE")
        (field (name "BOM_Supplier Part") "C307580")
      )
      (libsource (lib "") (part "CL31C101JHFNNNE_16"))
    )
    (comp (ref "C310K")
      (value "100pF")
      (fields
        (field (name "BOM_Manufacturer Part") "CL31C101JHFNNNE")
        (field (name "BOM_Supplier Part") "C307580")
      )
      (libsource (lib "") (part "CL31C101JHFNNNE_11"))
    )
    (comp (ref "C310L")
      (value "100pF")
      (fields
        (field (name "BOM_Manufacturer Part") "CL31C101JHFNNNE")
        (field (name "BOM_Supplier Part") "C307580")
      )
      (libsource (lib "") (part "CL31C101JHFNNNE_9"))
    )
    (comp (ref "C310M")
      (value "100pF")
      (fields
        (field (name "BOM_Manufacturer Part") "CL31C101JHFNNNE")
        (field (name "BOM_Supplier Part") "C307580")
      )
      (libsource (lib "") (part "CL31C101JHFNNNE_6"))
    )
    (comp (ref "C310N")
      (value "100pF")
      (fields
        (field (name "BOM_Manufacturer Part") "CL31C101JHFNNNE")
        (field (name "BOM_Supplier Part") "C307580")
      )
      (libsource (lib "") (part "CL31C101JHFNNNE_10"))
    )
    (comp (ref "C310O")
      (value "100pF")
      (fields
        (field (name "BOM_Manufacturer Part") "CL31C101JHFNNNE")
        (field (name "BOM_Supplier Part") "C307580")
      )
      (libsource (lib "") (part "CL31C101JHFNNNE_8"))
    )
    (comp (ref "C310P")
      (value "100pF")
      (fields
        (field (name "BOM_Manufacturer Part") "CL31C101JHFNNNE")
        (field (name "BOM_Supplier Part") "C307580")
      )
      (libsource (lib "") (part "CL31C101JHFNNNE_12"))
    )
    (comp (ref "C310Q")
      (value "100pF")
      (fields
        (field (name "BOM_Manufacturer Part") "CL31C101JHFNNNE")
        (field (name "BOM_Supplier Part") "C307580")
      )
      (libsource (lib "") (part "CL31C101JHFNNNE_15"))
    )
    (comp (ref "C310R")
      (value "100pF")
      (fields
        (field (name "BOM_Manufacturer Part") "CL31C101JHFNNNE")
        (field (name "BOM_Supplier Part") "C307580")
      )
      (libsource (lib "") (part "CL31C101JHFNNNE_5"))
    )
    (comp (ref "C350A")
      (value "4.7uF")
      (fields
        (field (name "BOM_Manufacturer Part") "VZH4R7M1HTR-0406")
        (field (name "BOM_Supplier Part") "C164079")
      )
      (libsource (lib "") (part "VZH4R7M1HTR-0406"))
    )
    (comp (ref "C350B")
      (value "100nF")
      (fields
        (field (name "BOM_Manufacturer Part") "CL31B104KBCNNNC")
        (field (name "BOM_Supplier Part") "C24497")
      )
      (libsource (lib "") (part "CL31B104KBCNNNC"))
    )
    (comp (ref "C351A")
      (value "4.7uF")
      (fields
        (field (name "BOM_Manufacturer Part") "VZH4R7M1HTR-0406")
        (field (name "BOM_Supplier Part") "C164079")
      )
      (libsource (lib "") (part "VZH4R7M1HTR-0406_1"))
    )
    (comp (ref "C351B")
      (value "100nF")
      (fields
        (field (name "BOM_Manufacturer Part") "CL31B104KBCNNNC")
        (field (name "BOM_Supplier Part") "C24497")
      )
      (libsource (lib "") (part "CL31B104KBCNNNC_1"))
    )
    (comp (ref "CN309")
      (value "SCSI Internal DIL50M")
      (fields
        (field (name "BOM_Manufacturer Part") "Header-Male-2.54_2x20")
        (field (name "BOM_Supplier Part") "C50980")
      )
      (libsource (lib "") (part "HEADER-MALE-2.54_2X25"))
    )
    (comp (ref "CN310") (value "SCSI External MD50F") (libsource (lib "") (part "MD50R")))
    (comp (ref "FB310A")
      (value "60Ω")
      (fields
        (field (name "BOM_Manufacturer Part") "CBG321609U600T")
        (field (name "BOM_Supplier Part") "C1020")
      )
      (libsource (lib "") (part "MLB3216-601(f)_1"))
    )
    (comp (ref "FB310B")
      (value "60Ω")
      (fields
        (field (name "BOM_Manufacturer Part") "CBG321609U600T")
        (field (name "BOM_Supplier Part") "C1020")
      )
      (libsource (lib "") (part "MLB3216-601(f)_27"))
    )
    (comp (ref "FB310C")
      (value "60Ω")
      (fields
        (field (name "BOM_Manufacturer Part") "CBG321609U600T")
        (field (name "BOM_Supplier Part") "C1020")
      )
      (libsource (lib "") (part "MLB3216-601(f)_21"))
    )
    (comp (ref "FB310D")
      (value "60Ω")
      (fields
        (field (name "BOM_Manufacturer Part") "CBG321609U600T")
        (field (name "BOM_Supplier Part") "C1020")
      )
      (libsource (lib "") (part "MLB3216-601(f)_7"))
    )
    (comp (ref "FB310E")
      (value "60Ω")
      (fields
        (field (name "BOM_Manufacturer Part") "CBG321609U600T")
        (field (name "BOM_Supplier Part") "C1020")
      )
      (libsource (lib "") (part "MLB3216-601(f)_14"))
    )
    (comp (ref "FB310F")
      (value "60Ω")
      (fields
        (field (name "BOM_Manufacturer Part") "CBG321609U600T")
        (field (name "BOM_Supplier Part") "C1020")
      )
      (libsource (lib "") (part "MLB3216-601(f)_23"))
    )
    (comp (ref "FB310G")
      (value "60Ω")
      (fields
        (field (name "BOM_Manufacturer Part") "CBG321609U600T")
        (field (name "BOM_Supplier Part") "C1020")
      )
      (libsource (lib "") (part "MLB3216-601(f)_5"))
    )
    (comp (ref "FB310H")
      (value "60Ω")
      (fields
        (field (name "BOM_Manufacturer Part") "CBG321609U600T")
        (field (name "BOM_Supplier Part") "C1020")
      )
      (libsource (lib "") (part "MLB3216-601(f)_28"))
    )
    (comp (ref "FB310I")
      (value "60Ω")
      (fields
        (field (name "BOM_Manufacturer Part") "CBG321609U600T")
        (field (name "BOM_Supplier Part") "C1020")
      )
      (libsource (lib "") (part "MLB3216-601(f)_15"))
    )
    (comp (ref "FB310J")
      (value "60Ω")
      (fields
        (field (name "BOM_Manufacturer Part") "CBG321609U600T")
        (field (name "BOM_Supplier Part") "C1020")
      )
      (libsource (lib "") (part "MLB3216-601(f)_11"))
    )
    (comp (ref "FB310K")
      (value "60Ω")
      (fields
        (field (name "BOM_Manufacturer Part") "CBG321609U600T")
        (field (name "BOM_Supplier Part") "C1020")
      )
      (libsource (lib "") (part "MLB3216-601(f)_20"))
    )
    (comp (ref "FB310L")
      (value "60Ω")
      (fields
        (field (name "BOM_Manufacturer Part") "CBG321609U600T")
        (field (name "BOM_Supplier Part") "C1020")
      )
      (libsource (lib "") (part "MLB3216-601(f)_2"))
    )
    (comp (ref "FB310M")
      (value "60Ω")
      (fields
        (field (name "BOM_Manufacturer Part") "CBG321609U600T")
        (field (name "BOM_Supplier Part") "C1020")
      )
      (libsource (lib "") (part "MLB3216-601(f)_9"))
    )
    (comp (ref "FB310N")
      (value "60Ω")
      (fields
        (field (name "BOM_Manufacturer Part") "CBG321609U600T")
        (field (name "BOM_Supplier Part") "C1020")
      )
      (libsource (lib "") (part "MLB3216-601(f)_6"))
    )
    (comp (ref "FB310O")
      (value "60Ω")
      (fields
        (field (name "BOM_Manufacturer Part") "CBG321609U600T")
        (field (name "BOM_Supplier Part") "C1020")
      )
      (libsource (lib "") (part "MLB3216-601(f)_25"))
    )
    (comp (ref "FB310P")
      (value "60Ω")
      (fields
        (field (name "BOM_Manufacturer Part") "CBG321609U600T")
        (field (name "BOM_Supplier Part") "C1020")
      )
      (libsource (lib "") (part "MLB3216-601(f)_35"))
    )
    (comp (ref "FB310Q")
      (value "60Ω")
      (fields
        (field (name "BOM_Manufacturer Part") "CBG321609U600T")
        (field (name "BOM_Supplier Part") "C1020")
      )
      (libsource (lib "") (part "MLB3216-601(f)_16"))
    )
    (comp (ref "FB310R")
      (value "60Ω")
      (fields
        (field (name "BOM_Manufacturer Part") "CBG321609U600T")
        (field (name "BOM_Supplier Part") "C1020")
      )
      (libsource (lib "") (part "MLB3216-601(f)_8"))
    )
    (comp (ref "FB311A")
      (value "60Ω")
      (fields
        (field (name "BOM_Manufacturer Part") "CBG321609U600T")
        (field (name "BOM_Supplier Part") "C1020")
      )
      (libsource (lib "") (part "MLB3216-601(f)_24"))
    )
    (comp (ref "FB311B")
      (value "60Ω")
      (fields
        (field (name "BOM_Manufacturer Part") "CBG321609U600T")
        (field (name "BOM_Supplier Part") "C1020")
      )
      (libsource (lib "") (part "MLB3216-601(f)_19"))
    )
    (comp (ref "FB311C")
      (value "60Ω")
      (fields
        (field (name "BOM_Manufacturer Part") "CBG321609U600T")
        (field (name "BOM_Supplier Part") "C1020")
      )
      (libsource (lib "") (part "MLB3216-601(f)_34"))
    )
    (comp (ref "FB311D")
      (value "60Ω")
      (fields
        (field (name "BOM_Manufacturer Part") "CBG321609U600T")
        (field (name "BOM_Supplier Part") "C1020")
      )
      (libsource (lib "") (part "MLB3216-601(f)_18"))
    )
    (comp (ref "FB311E")
      (value "60Ω")
      (fields
        (field (name "BOM_Manufacturer Part") "CBG321609U600T")
        (field (name "BOM_Supplier Part") "C1020")
      )
      (libsource (lib "") (part "MLB3216-601(f)_30"))
    )
    (comp (ref "FB311F")
      (value "60Ω")
      (fields
        (field (name "BOM_Manufacturer Part") "CBG321609U600T")
        (field (name "BOM_Supplier Part") "C1020")
      )
      (libsource (lib "") (part "MLB3216-601(f)_33"))
    )
    (comp (ref "FB311G")
      (value "60Ω")
      (fields
        (field (name "BOM_Manufacturer Part") "CBG321609U600T")
        (field (name "BOM_Supplier Part") "C1020")
      )
      (libsource (lib "") (part "MLB3216-601(f)_10"))
    )
    (comp (ref "FB311H")
      (value "60Ω")
      (fields
        (field (name "BOM_Manufacturer Part") "CBG321609U600T")
        (field (name "BOM_Supplier Part") "C1020")
      )
      (libsource (lib "") (part "MLB3216-601(f)_13"))
    )
    (comp (ref "FB311I")
      (value "60Ω")
      (fields
        (field (name "BOM_Manufacturer Part") "CBG321609U600T")
        (field (name "BOM_Supplier Part") "C1020")
      )
      (libsource (lib "") (part "MLB3216-601(f)_31"))
    )
    (comp (ref "FB311J")
      (value "60Ω")
      (fields
        (field (name "BOM_Manufacturer Part") "CBG321609U600T")
        (field (name "BOM_Supplier Part") "C1020")
      )
      (libsource (lib "") (part "MLB3216-601(f)"))
    )
    (comp (ref "FB311K")
      (value "60Ω")
      (fields
        (field (name "BOM_Manufacturer Part") "CBG321609U600T")
        (field (name "BOM_Supplier Part") "C1020")
      )
      (libsource (lib "") (part "MLB3216-601(f)_4"))
    )
    (comp (ref "FB311L")
      (value "60Ω")
      (fields
        (field (name "BOM_Manufacturer Part") "CBG321609U600T")
        (field (name "BOM_Supplier Part") "C1020")
      )
      (libsource (lib "") (part "MLB3216-601(f)_22"))
    )
    (comp (ref "FB311M")
      (value "60Ω")
      (fields
        (field (name "BOM_Manufacturer Part") "CBG321609U600T")
        (field (name "BOM_Supplier Part") "C1020")
      )
      (libsource (lib "") (part "MLB3216-601(f)_12"))
    )
    (comp (ref "FB311N")
      (value "60Ω")
      (fields
        (field (name "BOM_Manufacturer Part") "CBG321609U600T")
        (field (name "BOM_Supplier Part") "C1020")
      )
      (libsource (lib "") (part "MLB3216-601(f)_17"))
    )
    (comp (ref "FB311O")
      (value "60Ω")
      (fields
        (field (name "BOM_Manufacturer Part") "CBG321609U600T")
        (field (name "BOM_Supplier Part") "C1020")
      )
      (libsource (lib "") (part "MLB3216-601(f)_3"))
    )
    (comp (ref "FB311P")
      (value "60Ω")
      (fields
        (field (name "BOM_Manufacturer Part") "CBG321609U600T")
        (field (name "BOM_Supplier Part") "C1020")
      )
      (libsource (lib "") (part "MLB3216-601(f)_26"))
    )
    (comp (ref "FB311Q")
      (value "60Ω")
      (fields
        (field (name "BOM_Manufacturer Part") "CBG321609U600T")
        (field (name "BOM_Supplier Part") "C1020")
      )
      (libsource (lib "") (part "MLB3216-601(f)_29"))
    )
    (comp (ref "FB311R")
      (value "60Ω")
      (fields
        (field (name "BOM_Manufacturer Part") "CBG321609U600T")
        (field (name "BOM_Supplier Part") "C1020")
      )
      (libsource (lib "") (part "MLB3216-601(f)_32"))
    )
    (comp (ref "R212A")
      (value "1K")
      (fields
        (field (name "BOM_Manufacturer Part") "1206W4F1001T5E")
        (field (name "BOM_Supplier Part") "C4410")
      )
      (libsource (lib "") (part "1206W4F1001T5E_7"))
    )
    (comp (ref "R212B")
      (value "1K")
      (fields
        (field (name "BOM_Manufacturer Part") "1206W4F1001T5E")
        (field (name "BOM_Supplier Part") "C4410")
      )
      (libsource (lib "") (part "1206W4F1001T5E_6"))
    )
    (comp (ref "R212C")
      (value "1K")
      (fields
        (field (name "BOM_Manufacturer Part") "1206W4F1001T5E")
        (field (name "BOM_Supplier Part") "C4410")
      )
      (libsource (lib "") (part "1206W4F1001T5E_1"))
    )
    (comp (ref "R212D")
      (value "1K")
      (fields
        (field (name "BOM_Manufacturer Part") "1206W4F1001T5E")
        (field (name "BOM_Supplier Part") "C4410")
      )
      (libsource (lib "") (part "1206W4F1001T5E_2"))
    )
    (comp (ref "R212E")
      (value "1K")
      (fields
        (field (name "BOM_Manufacturer Part") "1206W4F1001T5E")
        (field (name "BOM_Supplier Part") "C4410")
      )
      (libsource (lib "") (part "1206W4F1001T5E"))
    )
    (comp (ref "R212F")
      (value "1K")
      (fields
        (field (name "BOM_Manufacturer Part") "1206W4F1001T5E")
        (field (name "BOM_Supplier Part") "C4410")
      )
      (libsource (lib "") (part "1206W4F1001T5E_4"))
    )
    (comp (ref "R212G")
      (value "1K")
      (fields
        (field (name "BOM_Manufacturer Part") "1206W4F1001T5E")
        (field (name "BOM_Supplier Part") "C4410")
      )
      (libsource (lib "") (part "1206W4F1001T5E_5"))
    )
    (comp (ref "R212H")
      (value "1K")
      (fields
        (field (name "BOM_Manufacturer Part") "1206W4F1001T5E")
        (field (name "BOM_Supplier Part") "C4410")
      )
      (libsource (lib "") (part "1206W4F1001T5E_3"))
    )
    (comp (ref "RP300A")
      (value "220/330 Term")
      (fields
        (field (name "BOM_Manufacturer Part") "4608X-104-331/221L")
        (field (name "BOM_Supplier Part") "652-4608X104331/221L")
      )
      (libsource (lib "") (part "SCSI Terminator sip-8"))
    )
    (comp (ref "RP300B")
      (value "220/330 Term")
      (fields
        (field (name "BOM_Manufacturer Part") "4608X-104-331/221L")
        (field (name "BOM_Supplier Part") "652-4608X104331/221L")
      )
      (libsource (lib "") (part "SCSI Terminator sip-8_1"))
    )
    (comp (ref "RP300C")
      (value "220/330 Term")
      (fields
        (field (name "BOM_Manufacturer Part") "4608X-104-331/221L")
        (field (name "BOM_Supplier Part") "652-4608X104331/221L")
      )
      (libsource (lib "") (part "SCSI Terminator sip-8_2"))
    )
    (comp (ref "SW1")
      (value "DA-08RP")
      (fields (field (name "BOM_Supplier Part") "C129027"))
      (libsource (lib "") (part "DA-08RP"))
    )
    (comp (ref "U213")
      (value "74F244")
      (fields (field (name "BOM_Manufacturer Part") "74F244SCX") (field (name "BOM_Supplier Part") "C5555"))
      (libsource (lib "") (part "74F244SCX"))
    )
    (comp (ref "U310") (value "DS2107S") (libsource (lib "") (part "DS2107S")))
    (comp (ref "U311") (value "DS2107S") (libsource (lib "") (part "DS2107S")))
    (comp (ref "C300A")
      (value "100nF")
      (fields
        (field (name "BOM_Manufacturer Part") "CL31B104KBCNNNC")
        (field (name "BOM_Supplier Part") "C24497")
      )
      (libsource (lib "") (part "CL31B104KBCNNNC"))
    )
    (comp (ref "C300B")
      (value "10nF")
      (fields
        (field (name "BOM_Manufacturer Part") "1206B103K500NT")
        (field (name "BOM_Supplier Part") "C1846")
      )
      (libsource (lib "") (part "1206B103K500NT_2"))
    )
    (comp (ref "C300C")
      (value "100nF")
      (fields
        (field (name "BOM_Manufacturer Part") "CL31B104KBCNNNC")
        (field (name "BOM_Supplier Part") "C24497")
      )
      (libsource (lib "") (part "CL31B104KBCNNNC_5"))
    )
    (comp (ref "C300D")
      (value "10nF")
      (fields
        (field (name "BOM_Manufacturer Part") "1206B103K500NT")
        (field (name "BOM_Supplier Part") "C1846")
      )
      (libsource (lib "") (part "1206B103K500NT_4"))
    )
    (comp (ref "C300E")
      (value "100nF")
      (fields
        (field (name "BOM_Manufacturer Part") "CL31B104KBCNNNC")
        (field (name "BOM_Supplier Part") "C24497")
      )
      (libsource (lib "") (part "CL31B104KBCNNNC_3"))
    )
    (comp (ref "C300F")
      (value "10nF")
      (fields
        (field (name "BOM_Manufacturer Part") "1206B103K500NT")
        (field (name "BOM_Supplier Part") "C1846")
      )
      (libsource (lib "") (part "1206B103K500NT_3"))
    )
    (comp (ref "C300G")
      (value "100nF")
      (fields
        (field (name "BOM_Manufacturer Part") "CL31B104KBCNNNC")
        (field (name "BOM_Supplier Part") "C24497")
      )
      (libsource (lib "") (part "CL31B104KBCNNNC_2"))
    )
    (comp (ref "C300H")
      (value "10nF")
      (fields
        (field (name "BOM_Manufacturer Part") "1206B103K500NT")
        (field (name "BOM_Supplier Part") "C1846")
      )
      (libsource (lib "") (part "1206B103K500NT_1"))
    )
    (comp (ref "C300I")
      (value "100nF")
      (fields
        (field (name "BOM_Manufacturer Part") "CL31B104KBCNNNC")
        (field (name "BOM_Supplier Part") "C24497")
      )
      (libsource (lib "") (part "CL31B104KBCNNNC_1"))
    )
    (comp (ref "C301A")
      (value "10nF")
      (fields
        (field (name "BOM_Manufacturer Part") "1206B103K500NT")
        (field (name "BOM_Supplier Part") "C1846")
      )
      (libsource (lib "") (part "1206B103K500NT"))
    )
    (comp (ref "C302A")
      (value "100nF")
      (fields
        (field (name "BOM_Manufacturer Part") "CL31B104KBCNNNC")
        (field (name "BOM_Supplier Part") "C24497")
      )
      (libsource (lib "") (part "CL31B104KBCNNNC_4"))
    )
    (comp (ref "CN308")
      (value "TO-MB")
      (fields
        (field (name "BOM_Manufacturer Part") "Header2.54mm 1*3P")
        (field (name "BOM_Supplier Part") "C49257")
      )
      (libsource (lib "") (part "Header-Male-2.54_1x3"))
    )
    (comp (ref "CN351")
      (value "TO-LED")
      (fields
        (field (name "BOM_Manufacturer Part") "Header2.54mm 1*3P")
        (field (name "BOM_Supplier Part") "C49257")
      )
      (libsource (lib "") (part "Header-Male-2.54_1x3"))
    )
    (comp (ref "FB502")
      (value "60Ω")
      (fields
        (field (name "BOM_Manufacturer Part") "CBG321609U600T")
        (field (name "BOM_Supplier Part") "C1020")
      )
      (libsource (lib "") (part "MLB3216-601(f)_1"))
    )
    (comp (ref "FB503")
      (value "60Ω")
      (fields
        (field (name "BOM_Manufacturer Part") "CBG321609U600T")
        (field (name "BOM_Supplier Part") "C1020")
      )
      (libsource (lib "") (part "MLB3216-601(f)"))
    )
    (comp (ref "FB506")
      (value "60Ω")
      (fields
        (field (name "BOM_Manufacturer Part") "CBG321609U600T")
        (field (name "BOM_Supplier Part") "C1020")
      )
      (libsource (lib "") (part "MLB3216-601(f)_1"))
    )
    (comp (ref "J100")
      (value "ESIZE")
      (fields
        (field (name "BOM_Manufacturer Part") "Header2.54mm 1*3P")
        (field (name "BOM_Supplier Part") "C49257")
      )
      (libsource (lib "") (part "Header-Male-2.54_1x3_1"))
    )
    (comp (ref "R300A")
      (value "1K")
      (fields
        (field (name "BOM_Manufacturer Part") "1206W4F1001T5E")
        (field (name "BOM_Supplier Part") "C4410")
      )
      (libsource (lib "") (part "1206W4F1001T5E"))
    )
    (comp (ref "R300B")
      (value "1K")
      (fields
        (field (name "BOM_Manufacturer Part") "1206W4F1001T5E")
        (field (name "BOM_Supplier Part") "C4410")
      )
      (libsource (lib "") (part "1206W4F1001T5E_5"))
    )
    (comp (ref "R300C")
      (value "1K")
      (fields
        (field (name "BOM_Manufacturer Part") "1206W4F1001T5E")
        (field (name "BOM_Supplier Part") "C4410")
      )
      (libsource (lib "") (part "1206W4F1001T5E_15"))
    )
    (comp (ref "R300D")
      (value "1K")
      (fields
        (field (name "BOM_Manufacturer Part") "1206W4F1001T5E")
        (field (name "BOM_Supplier Part") "C4410")
      )
      (libsource (lib "") (part "1206W4F1001T5E_1"))
    )
    (comp (ref "R300E")
      (value "1K")
      (fields
        (field (name "BOM_Manufacturer Part") "1206W4F1001T5E")
        (field (name "BOM_Supplier Part") "C4410")
      )
      (libsource (lib "") (part "1206W4F1001T5E_17"))
    )
    (comp (ref "R300F")
      (value "1K")
      (fields
        (field (name "BOM_Manufacturer Part") "1206W4F1001T5E")
        (field (name "BOM_Supplier Part") "C4410")
      )
      (libsource (lib "") (part "1206W4F1001T5E_9"))
    )
    (comp (ref "R300G")
      (value "1K")
      (fields
        (field (name "BOM_Manufacturer Part") "1206W4F1001T5E")
        (field (name "BOM_Supplier Part") "C4410")
      )
      (libsource (lib "") (part "1206W4F1001T5E_11"))
    )
    (comp (ref "R300H")
      (value "1K")
      (fields
        (field (name "BOM_Manufacturer Part") "1206W4F1001T5E")
        (field (name "BOM_Supplier Part") "C4410")
      )
      (libsource (lib "") (part "1206W4F1001T5E_14"))
    )
    (comp (ref "R300I")
      (value "1K")
      (fields
        (field (name "BOM_Manufacturer Part") "1206W4F1001T5E")
        (field (name "BOM_Supplier Part") "C4410")
      )
      (libsource (lib "") (part "1206W4F1001T5E_8"))
    )
    (comp (ref "R300J")
      (value "1K")
      (fields
        (field (name "BOM_Manufacturer Part") "1206W4F1001T5E")
        (field (name "BOM_Supplier Part") "C4410")
      )
      (libsource (lib "") (part "1206W4F1001T5E_4"))
    )
    (comp (ref "R300K")
      (value "1K")
      (fields
        (field (name "BOM_Manufacturer Part") "1206W4F1001T5E")
        (field (name "BOM_Supplier Part") "C4410")
      )
      (libsource (lib "") (part "1206W4F1001T5E_13"))
    )
    (comp (ref "R300L")
      (value "1K")
      (fields
        (field (name "BOM_Manufacturer Part") "1206W4F1001T5E")
        (field (name "BOM_Supplier Part") "C4410")
      )
      (libsource (lib "") (part "1206W4F1001T5E_6"))
    )
    (comp (ref "R300M")
      (value "1K")
      (fields
        (field (name "BOM_Manufacturer Part") "1206W4F1001T5E")
        (field (name "BOM_Supplier Part") "C4410")
      )
      (libsource (lib "") (part "1206W4F1001T5E_3"))
    )
    (comp (ref "R300N")
      (value "1K")
      (fields
        (field (name "BOM_Manufacturer Part") "1206W4F1001T5E")
        (field (name "BOM_Supplier Part") "C4410")
      )
      (libsource (lib "") (part "1206W4F1001T5E_2"))
    )
    (comp (ref "R300O")
      (value "1K")
      (fields
        (field (name "BOM_Manufacturer Part") "1206W4F1001T5E")
        (field (name "BOM_Supplier Part") "C4410")
      )
      (libsource (lib "") (part "1206W4F1001T5E_16"))
    )
    (comp (ref "R300P")
      (value "1K")
      (fields
        (field (name "BOM_Manufacturer Part") "1206W4F1001T5E")
        (field (name "BOM_Supplier Part") "C4410")
      )
      (libsource (lib "") (part "1206W4F1001T5E_12"))
    )
    (comp (ref "R301A")
      (value "22")
      (fields
        (field (name "BOM_Manufacturer Part") "RS-06K22R0FT")
        (field (name "BOM_Supplier Part") "C140034")
      )
      (libsource (lib "") (part "RS-06K22R0FT_2"))
    )
    (comp (ref "R302A")
      (value "22")
      (fields
        (field (name "BOM_Manufacturer Part") "RS-06K22R0FT")
        (field (name "BOM_Supplier Part") "C140034")
      )
      (libsource (lib "") (part "RS-06K22R0FT_1"))
    )
    (comp (ref "R302B")
      (value "22")
      (fields
        (field (name "BOM_Manufacturer Part") "RS-06K22R0FT")
        (field (name "BOM_Supplier Part") "C140034")
      )
      (libsource (lib "") (part "RS-06K22R0FT"))
    )
    (comp (ref "R307A")
      (value "1K")
      (fields
        (field (name "BOM_Manufacturer Part") "1206W4F1001T5E")
        (field (name "BOM_Supplier Part") "C4410")
      )
      (libsource (lib "") (part "1206W4F1001T5E_10"))
    )
    (comp (ref "R307B")
      (value "1K")
      (fields
        (field (name "BOM_Manufacturer Part") "1206W4F1001T5E")
        (field (name "BOM_Supplier Part") "C4410")
      )
      (libsource (lib "") (part "1206W4F1001T5E_7"))
    )
    (comp (ref "R398")
      (value "120")
      (fields
        (field (name "BOM_Manufacturer Part") "RTT061200FTP")
        (field (name "BOM_Supplier Part") "C159715")
      )
      (libsource (lib "") (part "RTT061200FTP"))
    )
    (comp (ref "U206")
      (value "27c256")
      (fields (field (name "BOM_Manufacturer Part") "27C256"))
      (libsource (lib "") (part "27c256"))
    )
    (comp (ref "U300") (value "NCR53C710") (libsource (lib "") (part "NCR53C710")))
    (comp (ref "U301") (value "Abracon 50MHz AC0 D.9403") (libsource (lib "") (part "Osc")))
    (comp (ref "U302")
      (value "74F74D")
      (fields (field (name "BOM_Supplier Part") "C5573"))
      (libsource (lib "") (part "74F74D"))
    )
    (comp (ref "FB500")
      (value "60Ω")
      (fields
        (field (name "BOM_Manufacturer Part") "CBG321609U600T")
        (field (name "BOM_Supplier Part") "C1020")
      )
      (libsource (lib "") (part "MLB3216-601(f)_1"))
    )
    (comp (ref "FB501")
      (value "60Ω")
      (fields
        (field (name "BOM_Manufacturer Part") "CBG321609U600T")
        (field (name "BOM_Supplier Part") "C1020")
      )
      (libsource (lib "") (part "MLB3216-601(f)"))
    )
    (comp (ref "FB504")
      (value "60Ω")
      (fields
        (field (name "BOM_Manufacturer Part") "CBG321609U600T")
        (field (name "BOM_Supplier Part") "C1020")
      )
      (libsource (lib "") (part "MLB3216-601(f)"))
    )
    (comp (ref "FB505")
      (value "60Ω")
      (fields
        (field (name "BOM_Manufacturer Part") "CBG321609U600T")
        (field (name "BOM_Supplier Part") "C1020")
      )
      (libsource (lib "") (part "MLB3216-601(f)"))
    )
    (comp (ref "U202")
      (value "GAL22V10H-15")
      (fields (field (name "BOM_Manufacturer Part") "GAL220V10"))
      (libsource (lib "") (part "GAL22V10"))
    )
    (comp (ref "U203")
      (value "GAL22V10H-15")
      (fields (field (name "BOM_Manufacturer Part") "GAL220V10"))
      (libsource (lib "") (part "GAL22V10"))
    )
    (comp (ref "U205")
      (value "GAL22V10H-15")
      (fields (field (name "BOM_Manufacturer Part") "GAL220V10"))
      (libsource (lib "") (part "GAL22V10"))
    )
    (comp (ref "U207")
      (value "GAL22V10H-15")
      (fields (field (name "BOM_Manufacturer Part") "GAL220V10"))
      (libsource (lib "") (part "GAL22V10"))
    )
    (comp (ref "U303")
      (value "GAL22V10H-15")
      (fields (field (name "BOM_Manufacturer Part") "GAL220V10"))
      (libsource (lib "") (part "GAL22V10"))
    )
    (comp (ref "U304")
      (value "GAL22V10B-10")
      (fields (field (name "BOM_Manufacturer Part") "GAL220V10"))
      (libsource (lib "") (part "GAL22V10"))
    )
    (comp (ref "U305")
      (value "GAL22V10B-10")
      (fields (field (name "BOM_Manufacturer Part") "GAL220V10"))
      (libsource (lib "") (part "GAL22V10"))
    )
    (comp (ref "U306")
      (value "GAL22V10B-10")
      (fields (field (name "BOM_Manufacturer Part") "GAL220V10"))
      (libsource (lib "") (part "GAL22V10"))
    )
    (comp (ref "C1") (value "Zorro III Edge") (libsource (lib "") (part "Zorro III Edge")))
    (comp (ref "C306B")
      (value "10pF")
      (fields
        (field (name "BOM_Manufacturer Part") "CL21C100JBANNNC")
        (field (name "BOM_Supplier Part") "C1785")
      )
      (libsource (lib "") (part "CL21C100JBANNNC"))
    )
    (comp (ref "FB507")
      (value "60Ω")
      (fields
        (field (name "BOM_Manufacturer Part") "CBG321609U600T")
        (field (name "BOM_Supplier Part") "C1020")
      )
      (libsource (lib "") (part "MLB3216-601(f)"))
    )
    (comp (ref "FB508")
      (value "60Ω")
      (fields
        (field (name "BOM_Manufacturer Part") "CBG321609U600T")
        (field (name "BOM_Supplier Part") "C1020")
      )
      (libsource (lib "") (part "MLB3216-601(f)"))
    )
    (comp (ref "R100A")
      (value "1K")
      (fields
        (field (name "BOM_Manufacturer Part") "1206W4F1001T5E")
        (field (name "BOM_Supplier Part") "C4410")
      )
      (libsource (lib "") (part "1206W4F1001T5E_4"))
    )
    (comp (ref "R103A")
      (value "1K")
      (fields
        (field (name "BOM_Manufacturer Part") "1206W4F1001T5E")
        (field (name "BOM_Supplier Part") "C4410")
      )
      (libsource (lib "") (part "1206W4F1001T5E_15"))
    )
    (comp (ref "R103B")
      (value "1K")
      (fields
        (field (name "BOM_Manufacturer Part") "1206W4F1001T5E")
        (field (name "BOM_Supplier Part") "C4410")
      )
      (libsource (lib "") (part "1206W4F1001T5E_6"))
    )
    (comp (ref "R109A")
      (value "1K")
      (fields
        (field (name "BOM_Manufacturer Part") "1206W4F1001T5E")
        (field (name "BOM_Supplier Part") "C4410")
      )
      (libsource (lib "") (part "1206W4F1001T5E_1"))
    )
    (comp (ref "R109B")
      (value "1K")
      (fields
        (field (name "BOM_Manufacturer Part") "1206W4F1001T5E")
        (field (name "BOM_Supplier Part") "C4410")
      )
      (libsource (lib "") (part "1206W4F1001T5E"))
    )
    (comp (ref "R109C")
      (value "1K")
      (fields
        (field (name "BOM_Manufacturer Part") "1206W4F1001T5E")
        (field (name "BOM_Supplier Part") "C4410")
      )
      (libsource (lib "") (part "1206W4F1001T5E_12"))
    )
    (comp (ref "R109D")
      (value "1K")
      (fields
        (field (name "BOM_Manufacturer Part") "1206W4F1001T5E")
        (field (name "BOM_Supplier Part") "C4410")
      )
      (libsource (lib "") (part "1206W4F1001T5E_2"))
    )
    (comp (ref "R109E")
      (value "1K")
      (fields
        (field (name "BOM_Manufacturer Part") "1206W4F1001T5E")
        (field (name "BOM_Supplier Part") "C4410")
      )
      (libsource (lib "") (part "1206W4F1001T5E_3"))
    )
    (comp (ref "R109F")
      (value "1K")
      (fields
        (field (name "BOM_Manufacturer Part") "1206W4F1001T5E")
        (field (name "BOM_Supplier Part") "C4410")
      )
      (libsource (lib "") (part "1206W4F1001T5E_13"))
    )
    (comp (ref "R109G")
      (value "1K")
      (fields
        (field (name "BOM_Manufacturer Part") "1206W4F1001T5E")
        (field (name "BOM_Supplier Part") "C4410")
      )
      (libsource (lib "") (part "1206W4F1001T5E_5"))
    )
    (comp (ref "R109H")
      (value "1K")
      (fields
        (field (name "BOM_Manufacturer Part") "1206W4F1001T5E")
        (field (name "BOM_Supplier Part") "C4410")
      )
      (libsource (lib "") (part "1206W4F1001T5E_11"))
    )
    (comp (ref "R200A")
      (value "1K")
      (fields
        (field (name "BOM_Manufacturer Part") "1206W4F1001T5E")
        (field (name "BOM_Supplier Part") "C4410")
      )
      (libsource (lib "") (part "1206W4F1001T5E_17"))
    )
    (comp (ref "R200B")
      (value "1K")
      (fields
        (field (name "BOM_Manufacturer Part") "1206W4F1001T5E")
        (field (name "BOM_Supplier Part") "C4410")
      )
      (libsource (lib "") (part "1206W4F1001T5E_7"))
    )
    (comp (ref "R200C")
      (value "1K")
      (fields
        (field (name "BOM_Manufacturer Part") "1206W4F1001T5E")
        (field (name "BOM_Supplier Part") "C4410")
      )
      (libsource (lib "") (part "1206W4F1001T5E_16"))
    )
    (comp (ref "R200D")
      (value "1K")
      (fields
        (field (name "BOM_Manufacturer Part") "1206W4F1001T5E")
        (field (name "BOM_Supplier Part") "C4410")
      )
      (libsource (lib "") (part "1206W4F1001T5E_10"))
    )
    (comp (ref "R200E")
      (value "1K")
      (fields
        (field (name "BOM_Manufacturer Part") "1206W4F1001T5E")
        (field (name "BOM_Supplier Part") "C4410")
      )
      (libsource (lib "") (part "1206W4F1001T5E_9"))
    )
    (comp (ref "R200F")
      (value "1K")
      (fields
        (field (name "BOM_Manufacturer Part") "1206W4F1001T5E")
        (field (name "BOM_Supplier Part") "C4410")
      )
      (libsource (lib "") (part "1206W4F1001T5E_18"))
    )
    (comp (ref "R200G")
      (value "1K")
      (fields
        (field (name "BOM_Manufacturer Part") "1206W4F1001T5E")
        (field (name "BOM_Supplier Part") "C4410")
      )
      (libsource (lib "") (part "1206W4F1001T5E_8"))
    )
    (comp (ref "R200H")
      (value "1K")
      (fields
        (field (name "BOM_Manufacturer Part") "1206W4F1001T5E")
        (field (name "BOM_Supplier Part") "C4410")
      )
      (libsource (lib "") (part "1206W4F1001T5E_14"))
    )
    (comp (ref "U100")
      (value "74FCT543TSO")
      (fields (field (name "BOM_Manufacturer Part") "CY74FCT543TSOC"))
      (libsource (lib "") (part "74FCT543TSO"))
    )
    (comp (ref "U101")
      (value "74FCT543TSO")
      (fields (field (name "BOM_Manufacturer Part") "CY74FCT543TSOC"))
      (libsource (lib "") (part "74FCT543TSO"))
    )
    (comp (ref "U102")
      (value "74FCT543TSO")
      (fields (field (name "BOM_Manufacturer Part") "CY74FCT543TSOC"))
      (libsource (lib "") (part "74FCT543TSO"))
    )
    (comp (ref "U103")
      (value "74F245D")
      (fields (field (name "BOM_Supplier Part") "C5557"))
      (libsource (lib "") (part "74F245D"))
    )
    (comp (ref "U105")
      (value "74FCT543TSO")
      (fields (field (name "BOM_Manufacturer Part") "CY74FCT543TSOC"))
      (libsource (lib "") (part "74FCT543TSO"))
    )
    (comp (ref "U106")
      (value "74FCT543TSO")
      (fields (field (name "BOM_Manufacturer Part") "CY74FCT543TSOC"))
      (libsource (lib "") (part "74FCT543TSO"))
    )
    (comp (ref "U107")
      (value "74FCT543TSO")
      (fields (field (name "BOM_Manufacturer Part") "CY74FCT543TSOC"))
      (libsource (lib "") (part "74FCT543TSO"))
    )
    (comp (ref "U108")
      (value "74FCT543TSO")
      (fields (field (name "BOM_Manufacturer Part") "CY74FCT543TSOC"))
      (libsource (lib "") (part "74FCT543TSO"))
    )
    (comp (ref "U109")
      (value "74F245D")
      (fields (field (name "BOM_Supplier Part") "C5557"))
      (libsource (lib "") (part "74F245D"))
    )
    (comp (ref "U200")
      (value "74FCT374TSO")
      (fields (field (name "BOM_Manufacturer Part") "74F374D") (field (name "BOM_Supplier Part") "C5564"))
      (libsource (lib "") (part "74F374D"))
    )
    (comp (ref "U201")
      (value "74FCT521TSO")
      (fields
        (field (name "BOM_Manufacturer Part") "74FCT521CTSOG8")
        (field (name "BOM_Supplier Part") "972-74FCT521CTSOG8")
      )
      (libsource (lib "") (part "74FCT521TSO"))
    )
    (comp (ref "U204")
      (value "74FCT374TSO")
      (fields (field (name "BOM_Manufacturer Part") "74F374D") (field (name "BOM_Supplier Part") "C5564"))
      (libsource (lib "") (part "74F374D"))
    )
    (comp (ref "U307")
      (value "74F07D")
      (fields (field (name "BOM_Supplier Part") "C5540"))
      (libsource (lib "") (part "74F07D"))
    )
    (comp (ref "C1A")
      (value "100nF")
      (fields
        (field (name "BOM_Manufacturer Part") "CL31B104KBCNNNC")
        (field (name "BOM_Supplier Part") "C24497")
      )
      (libsource (lib "") (part "CL31B104KBCNNNC_6"))
    )
    (comp (ref "C1B")
      (value "47uF")
      (fields
        (field (name "BOM_Manufacturer Part") "RVT1V470M0605")
        (field (name "BOM_Supplier Part") "C3344")
      )
      (libsource (lib "") (part "RVT1V470M0605_3"))
    )
    (comp (ref "C1C")
      (value "47uF")
      (fields
        (field (name "BOM_Manufacturer Part") "RVT1V470M0605")
        (field (name "BOM_Supplier Part") "C3344")
      )
      (libsource (lib "") (part "RVT1V470M0605_1"))
    )
    (comp (ref "C10")
      (value "47uF")
      (fields
        (field (name "BOM_Manufacturer Part") "RVT1V470M0605")
        (field (name "BOM_Supplier Part") "C3344")
      )
      (libsource (lib "") (part "RVT1V470M0605"))
    )
    (comp (ref "C11")
      (value "47uF")
      (fields
        (field (name "BOM_Manufacturer Part") "RVT1V470M0605")
        (field (name "BOM_Supplier Part") "C3344")
      )
      (libsource (lib "") (part "RVT1V470M0605"))
    )
    (comp (ref "C12")
      (value "47uF")
      (fields
        (field (name "BOM_Manufacturer Part") "RVT1V470M0605")
        (field (name "BOM_Supplier Part") "C3344")
      )
      (libsource (lib "") (part "RVT1V470M0605"))
    )
    (comp (ref "C13")
      (value "47uF")
      (fields
        (field (name "BOM_Manufacturer Part") "RVT1V470M0605")
        (field (name "BOM_Supplier Part") "C3344")
      )
      (libsource (lib "") (part "RVT1V470M0605_2"))
    )
    (comp (ref "C100A")
      (value "100nF")
      (fields
        (field (name "BOM_Manufacturer Part") "CL31B104KBCNNNC")
        (field (name "BOM_Supplier Part") "C24497")
      )
      (libsource (lib "") (part "CL31B104KBCNNNC_22"))
    )
    (comp (ref "C101A")
      (value "100nF")
      (fields
        (field (name "BOM_Manufacturer Part") "CL31B104KBCNNNC")
        (field (name "BOM_Supplier Part") "C24497")
      )
      (libsource (lib "") (part "CL31B104KBCNNNC_13"))
    )
    (comp (ref "C102A")
      (value "100nF")
      (fields
        (field (name "BOM_Manufacturer Part") "CL31B104KBCNNNC")
        (field (name "BOM_Supplier Part") "C24497")
      )
      (libsource (lib "") (part "CL31B104KBCNNNC_9"))
    )
    (comp (ref "C103A")
      (value "100nF")
      (fields
        (field (name "BOM_Manufacturer Part") "CL31B104KBCNNNC")
        (field (name "BOM_Supplier Part") "C24497")
      )
      (libsource (lib "") (part "CL31B104KBCNNNC_11"))
    )
    (comp (ref "C105A")
      (value "100nF")
      (fields
        (field (name "BOM_Manufacturer Part") "CL31B104KBCNNNC")
        (field (name "BOM_Supplier Part") "C24497")
      )
      (libsource (lib "") (part "CL31B104KBCNNNC_20"))
    )
    (comp (ref "C106A")
      (value "100nF")
      (fields
        (field (name "BOM_Manufacturer Part") "CL31B104KBCNNNC")
        (field (name "BOM_Supplier Part") "C24497")
      )
      (libsource (lib "") (part "CL31B104KBCNNNC_12"))
    )
    (comp (ref "C107A")
      (value "100nF")
      (fields
        (field (name "BOM_Manufacturer Part") "CL31B104KBCNNNC")
        (field (name "BOM_Supplier Part") "C24497")
      )
      (libsource (lib "") (part "CL31B104KBCNNNC_23"))
    )
    (comp (ref "C108A")
      (value "100nF")
      (fields
        (field (name "BOM_Manufacturer Part") "CL31B104KBCNNNC")
        (field (name "BOM_Supplier Part") "C24497")
      )
      (libsource (lib "") (part "CL31B104KBCNNNC_19"))
    )
    (comp (ref "C109A")
      (value "100nF")
      (fields
        (field (name "BOM_Manufacturer Part") "CL31B104KBCNNNC")
        (field (name "BOM_Supplier Part") "C24497")
      )
      (libsource (lib "") (part "CL31B104KBCNNNC_18"))
    )
    (comp (ref "C200A")
      (value "100nF")
      (fields
        (field (name "BOM_Manufacturer Part") "CL31B104KBCNNNC")
        (field (name "BOM_Supplier Part") "C24497")
      )
      (libsource (lib "") (part "CL31B104KBCNNNC"))
    )
    (comp (ref "C201A")
      (value "100nF")
      (fields
        (field (name "BOM_Manufacturer Part") "CL31B104KBCNNNC")
        (field (name "BOM_Supplier Part") "C24497")
      )
      (libsource (lib "") (part "CL31B104KBCNNNC_2"))
    )
    (comp (ref "C202A")
      (value "100nF")
      (fields
        (field (name "BOM_Manufacturer Part") "CL31B104KBCNNNC")
        (field (name "BOM_Supplier Part") "C24497")
      )
      (libsource (lib "") (part "CL31B104KBCNNNC_21"))
    )
    (comp (ref "C203A")
      (value "100nF")
      (fields
        (field (name "BOM_Manufacturer Part") "CL31B104KBCNNNC")
        (field (name "BOM_Supplier Part") "C24497")
      )
      (libsource (lib "") (part "CL31B104KBCNNNC_5"))
    )
    (comp (ref "C204A")
      (value "100nF")
      (fields
        (field (name "BOM_Manufacturer Part") "CL31B104KBCNNNC")
        (field (name "BOM_Supplier Part") "C24497")
      )
      (libsource (lib "") (part "CL31B104KBCNNNC_4"))
    )
    (comp (ref "C205A")
      (value "100nF")
      (fields
        (field (name "BOM_Manufacturer Part") "CL31B104KBCNNNC")
        (field (name "BOM_Supplier Part") "C24497")
      )
      (libsource (lib "") (part "CL31B104KBCNNNC_7"))
    )
    (comp (ref "C206A")
      (value "100nF")
      (fields
        (field (name "BOM_Manufacturer Part") "CL31B104KBCNNNC")
        (field (name "BOM_Supplier Part") "C24497")
      )
      (libsource (lib "") (part "CL31B104KBCNNNC_1"))
    )
    (comp (ref "C207A")
      (value "100nF")
      (fields
        (field (name "BOM_Manufacturer Part") "CL31B104KBCNNNC")
        (field (name "BOM_Supplier Part") "C24497")
      )
      (libsource (lib "") (part "CL31B104KBCNNNC_10"))
    )
    (comp (ref "C212A")
      (value "100nF")
      (fields
        (field (name "BOM_Manufacturer Part") "CL31B104KBCNNNC")
        (field (name "BOM_Supplier Part") "C24497")
      )
      (libsource (lib "") (part "CL31B104KBCNNNC_8"))
    )
    (comp (ref "C303A")
      (value "100nF")
      (fields
        (field (name "BOM_Manufacturer Part") "CL31B104KBCNNNC")
        (field (name "BOM_Supplier Part") "C24497")
      )
      (libsource (lib "") (part "CL31B104KBCNNNC_14"))
    )
    (comp (ref "C304A")
      (value "100nF")
      (fields
        (field (name "BOM_Manufacturer Part") "CL31B104KBCNNNC")
        (field (name "BOM_Supplier Part") "C24497")
      )
      (libsource (lib "") (part "CL31B104KBCNNNC_3"))
    )
    (comp (ref "C305A")
      (value "100nF")
      (fields
        (field (name "BOM_Manufacturer Part") "CL31B104KBCNNNC")
        (field (name "BOM_Supplier Part") "C24497")
      )
      (libsource (lib "") (part "CL31B104KBCNNNC_17"))
    )
    (comp (ref "C306A")
      (value "100nF")
      (fields
        (field (name "BOM_Manufacturer Part") "CL31B104KBCNNNC")
        (field (name "BOM_Supplier Part") "C24497")
      )
      (libsource (lib "") (part "CL31B104KBCNNNC_15"))
    )
    (comp (ref "C307A")
      (value "100nF")
      (fields
        (field (name "BOM_Manufacturer Part") "CL31B104KBCNNNC")
        (field (name "BOM_Supplier Part") "C24497")
      )
      (libsource (lib "") (part "CL31B104KBCNNNC_16"))
    )
    (comp (ref "CN2")
      (value "TE-350211-1")
      (fields
        (field (name "BOM_Manufacturer Part") "350211-1")
        (field (name "BOM_Supplier Part") "AN1212-ND")
      )
      (libsource (lib "") (part "TE-350211-1-Simple"))
    )
    (comp (ref "D309A")
      (value "LL4007G L0")
      (fields (field (name "BOM_Supplier Part") "C483912"))
      (libsource (lib "") (part "LL4007G L0"))
    )
    (comp (ref "F309A")
      (value "TH Polyfuse 1.85A")
      (fields (field (name "BOM_Manufacturer Part") "A72-185") (field (name "BOM_Supplier Part") "C135432"))
      (libsource (lib "") (part "A72-185 POLYFUSE"))
    )
    (comp (ref "F309B")
      (value "SMD Polyfuse 1.85A")
      (fields (field (name "BOM_Manufacturer Part") "A72-185") (field (name "BOM_Supplier Part") "C135432"))
      (libsource (lib "") (part "A72-185-POLYFUSE-SMD"))
    )
    (comp (ref "FID1")
      (value "FIDUCIAL_SQUARE_DOT_128_100")
      (libsource (lib "") (part "FIDUCIAL_SQUARE_DOT_128_100"))
    )
    (comp (ref "FID2")
      (value "FIDUCIAL_SQUARE_DOT_128_100")
      (libsource (lib "") (part "FIDUCIAL_SQUARE_DOT_128_100"))
    )
    (comp (ref "FID3")
      (value "FIDUCIAL_SQUARE_DOT_128_100")
      (libsource (lib "") (part "FIDUCIAL_SQUARE_DOT_128_100"))
    )
    (comp (ref "FID4")
      (value "FIDUCIAL_SQUARE_DOT_128_100")
      (libsource (lib "") (part "FIDUCIAL_SQUARE_DOT_128_100"))
    )
    (comp (ref "FID5")
      (value "FIDUCIAL_SQUARE_DOT_128_100")
      (libsource (lib "") (part "FIDUCIAL_SQUARE_DOT_128_100"))
    )
    (comp (ref "FID6")
      (value "FIDUCIAL_SQUARE_DOT_128_100")
      (libsource (lib "") (part "FIDUCIAL_SQUARE_DOT_128_100"))
    )
    (comp (ref "MB1") (value "Mousebites") (libsource (lib "") (part "Mousebites")))
    (comp (ref "MB2") (value "Mousebites") (libsource (lib "") (part "Mousebites")))
    (comp (ref "MH1")
      (value "MOUNTINGHOLE_4MM")
      (fields (field (name "BOM_Manufacturer Part") "Mounting hole"))
      (libsource (lib "") (part "MOUNTINGHOLE_4MM"))
    )
    (comp (ref "MH2")
      (value "MOUNTINGHOLE_4MM")
      (fields (field (name "BOM_Manufacturer Part") "Mounting hole"))
      (libsource (lib "") (part "MOUNTINGHOLE_4MM"))
    )
    (comp (ref "MH3")
      (value "MOUNTINGHOLE_4MM")
      (fields (field (name "BOM_Manufacturer Part") "Mounting hole"))
      (libsource (lib "") (part "MOUNTINGHOLE_4MM"))
    )
    (comp (ref "MH4")
      (value "MOUNTINGHOLE_4MM")
      (fields (field (name "BOM_Manufacturer Part") "Mounting hole"))
      (libsource (lib "") (part "MOUNTINGHOLE_4MM"))
    )
    (comp (ref "MK5") (value "Mounting_Hole") (libsource (lib "") (part "Mounting_Hole")))
    (comp (ref "MK6") (value "Mounting_Hole") (libsource (lib "") (part "Mounting_Hole")))
    (comp (ref "MK7") (value "Mounting_Hole") (libsource (lib "") (part "Mounting_Hole")))
    (comp (ref "C400A")
      (value "4.7uF")
      (fields
        (field (name "BOM_Manufacturer Part") "VZH4R7M1HTR-0406")
        (field (name "BOM_Supplier Part") "C164079")
      )
      (libsource (lib "") (part "VZH4R7M1HTR-0406_1"))
    )
    (comp (ref "C400B")
      (value "100nF")
      (fields
        (field (name "BOM_Manufacturer Part") "CL31B104KBCNNNC")
        (field (name "BOM_Supplier Part") "C24497")
      )
      (libsource (lib "") (part "CL31B104KBCNNNC_2"))
    )
    (comp (ref "C401A")
      (value "4.7uF")
      (fields
        (field (name "BOM_Manufacturer Part") "VZH4R7M1HTR-0406")
        (field (name "BOM_Supplier Part") "C164079")
      )
      (libsource (lib "") (part "VZH4R7M1HTR-0406_2"))
    )
    (comp (ref "C401B")
      (value "100nF")
      (fields
        (field (name "BOM_Manufacturer Part") "CL31B104KBCNNNC")
        (field (name "BOM_Supplier Part") "C24497")
      )
      (libsource (lib "") (part "CL31B104KBCNNNC"))
    )
    (comp (ref "C402")
      (value "100nF")
      (fields
        (field (name "BOM_Manufacturer Part") "CL31B104KBCNNNC")
        (field (name "BOM_Supplier Part") "C24497")
      )
      (libsource (lib "") (part "CL31B104KBCNNNC_1"))
    )
    (comp (ref "C403")
      (value "4.7uF")
      (fields
        (field (name "BOM_Manufacturer Part") "VZH4R7M1HTR-0406")
        (field (name "BOM_Supplier Part") "C164079")
      )
      (libsource (lib "") (part "VZH4R7M1HTR-0406"))
    )
    (comp (ref "CN400")
      (value "IDC-M-Right")
      (fields
        (field (name "BOM_Manufacturer Part") "Z-231012050106")
        (field (name "BOM_Supplier Part") "C221060")
      )
      (libsource (lib "") (part "Z-231012050106"))
    )
    (comp (ref "FID7")
      (value "FIDUCIAL_SQUARE_DOT_128_100")
      (libsource (lib "") (part "FIDUCIAL_SQUARE_DOT_128_100"))
    )
    (comp (ref "FID8")
      (value "FIDUCIAL_SQUARE_DOT_128_100")
      (libsource (lib "") (part "FIDUCIAL_SQUARE_DOT_128_100"))
    )
    (comp (ref "MK1") (value "Mounting_Hole") (libsource (lib "") (part "Mounting_Hole")))
    (comp (ref "MK2") (value "Mounting_Hole") (libsource (lib "") (part "Mounting_Hole")))
    (comp (ref "U400") (value "DS2107S") (libsource (lib "") (part "DS2107S")))
    (comp (ref "U401") (value "DS2107S") (libsource (lib "") (part "DS2107S")))
  )
  (nets
    (net (code "1") (name "A0") (class "Default")
      (node (ref "R300K") (pin "1") (pinfunction "1_1") (pintype "input"))
      (node (ref "U300") (pin "144") (pinfunction "A0_144") (pintype "unspecified"))
      (node (ref "U304") (pin "26") (pinfunction "IOQ_26") (pintype "unspecified"))
      (node (ref "U305") (pin "16") (pinfunction "I_16") (pintype "unspecified"))
    )
    (net (code "2") (name "A1") (class "Default")
      (node (ref "R300L") (pin "1") (pinfunction "1_1") (pintype "input"))
      (node (ref "U300") (pin "145") (pinfunction "A1_145") (pintype "unspecified"))
      (node (ref "U304") (pin "27") (pinfunction "IOQ_27") (pintype "unspecified"))
      (node (ref "U305") (pin "13") (pinfunction "I_13") (pintype "unspecified"))
    )
    (net (code "3") (name "A2") (class "Default")
      (node (ref "R300I") (pin "1") (pinfunction "1_1") (pintype "input"))
      (node (ref "U103") (pin "7") (pinfunction "A5_7") (pintype "unspecified"))
      (node (ref "U202") (pin "7") (pinfunction "I_7") (pintype "unspecified"))
      (node (ref "U206") (pin "10") (pinfunction "A0_10") (pintype "input"))
      (node (ref "U300") (pin "146") (pinfunction "A2_146") (pintype "unspecified"))
    )
    (net (code "4") (name "A3") (class "Default")
      (node (ref "R300J") (pin "1") (pinfunction "1_1") (pintype "input"))
      (node (ref "U103") (pin "6") (pinfunction "A4_6") (pintype "unspecified"))
      (node (ref "U202") (pin "6") (pinfunction "I_6") (pintype "unspecified"))
      (node (ref "U206") (pin "9") (pinfunction "A1_9") (pintype "input"))
      (node (ref "U300") (pin "147") (pinfunction "A3_147") (pintype "unspecified"))
    )
    (net (code "5") (name "A4") (class "Default")
      (node (ref "U103") (pin "5") (pinfunction "A3_5") (pintype "unspecified"))
      (node (ref "U202") (pin "5") (pinfunction "I_5") (pintype "unspecified"))
      (node (ref "U206") (pin "8") (pinfunction "A2_8") (pintype "input"))
      (node (ref "U300") (pin "148") (pinfunction "A4_148") (pintype "unspecified"))
    )
    (net (code "6") (name "A5") (class "Default")
      (node (ref "U103") (pin "4") (pinfunction "A2_4") (pintype "unspecified"))
      (node (ref "U202") (pin "4") (pinfunction "I_4") (pintype "unspecified"))
      (node (ref "U206") (pin "7") (pinfunction "A3_7") (pintype "input"))
      (node (ref "U300") (pin "150") (pinfunction "A5_150") (pintype "unspecified"))
    )
    (net (code "7") (name "A6") (class "Default")
      (node (ref "U103") (pin "3") (pinfunction "A1_3") (pintype "unspecified"))
      (node (ref "U202") (pin "3") (pinfunction "I_3") (pintype "unspecified"))
      (node (ref "U206") (pin "6") (pinfunction "A4_6") (pintype "input"))
      (node (ref "U300") (pin "151") (pinfunction "A6_151") (pintype "unspecified"))
    )
    (net (code "8") (name "A7") (class "Default")
      (node (ref "U103") (pin "2") (pinfunction "A0_2") (pintype "unspecified"))
      (node (ref "U206") (pin "5") (pinfunction "A5_5") (pintype "input"))
      (node (ref "U300") (pin "152") (pinfunction "A7_152") (pintype "unspecified"))
    )
    (net (code "9") (name "A8") (class "Default")
      (node (ref "U102") (pin "10") (pinfunction "A7_10") (pintype "bidirectional"))
      (node (ref "U202") (pin "9") (pinfunction "I_9") (pintype "unspecified"))
      (node (ref "U206") (pin "4") (pinfunction "A6_4") (pintype "input"))
      (node (ref "U300") (pin "154") (pinfunction "A8_154") (pintype "unspecified"))
    )
    (net (code "10") (name "A9") (class "Default")
      (node (ref "U102") (pin "9") (pinfunction "A6_9") (pintype "bidirectional"))
      (node (ref "U206") (pin "3") (pinfunction "A7_3") (pintype "input"))
      (node (ref "U300") (pin "155") (pinfunction "A9_155") (pintype "unspecified"))
    )
    (net (code "11") (name "A10") (class "Default")
      (node (ref "U102") (pin "8") (pinfunction "A5_8") (pintype "bidirectional"))
      (node (ref "U206") (pin "25") (pinfunction "A8_25") (pintype "output"))
      (node (ref "U300") (pin "157") (pinfunction "A10_157") (pintype "unspecified"))
    )
    (net (code "12") (name "A11") (class "Default")
      (node (ref "U102") (pin "7") (pinfunction "A4_7") (pintype "bidirectional"))
      (node (ref "U206") (pin "24") (pinfunction "A9_24") (pintype "output"))
      (node (ref "U300") (pin "158") (pinfunction "A11_158") (pintype "unspecified"))
    )
    (net (code "13") (name "A12") (class "Default")
      (node (ref "U102") (pin "6") (pinfunction "A3_6") (pintype "bidirectional"))
      (node (ref "U206") (pin "21") (pinfunction "A10_21") (pintype "output"))
      (node (ref "U300") (pin "159") (pinfunction "A12_159") (pintype "unspecified"))
    )
    (net (code "14") (name "A13") (class "Default")
      (node (ref "U102") (pin "5") (pinfunction "A2_5") (pintype "bidirectional"))
      (node (ref "U206") (pin "23") (pinfunction "A11_23") (pintype "output"))
      (node (ref "U300") (pin "160") (pinfunction "A13_160") (pintype "unspecified"))
    )
    (net (code "15") (name "A14") (class "Default")
      (node (ref "U102") (pin "4") (pinfunction "A1_4") (pintype "bidirectional"))
      (node (ref "U206") (pin "2") (pinfunction "A12_2") (pintype "input"))
      (node (ref "U300") (pin "1") (pinfunction "A14_1") (pintype "unspecified"))
    )
    (net (code "16") (name "A15") (class "Default")
      (node (ref "U102") (pin "3") (pinfunction "A0_3") (pintype "bidirectional"))
      (node (ref "U206") (pin "26") (pinfunction "A13_26") (pintype "output"))
      (node (ref "U300") (pin "3") (pinfunction "A15_3") (pintype "unspecified"))
    )
    (net (code "17") (name "A16") (class "Default")
      (node (ref "U101") (pin "10") (pinfunction "A7_10") (pintype "bidirectional"))
      (node (ref "U206") (pin "27") (pinfunction "A14_27") (pintype "output"))
      (node (ref "U300") (pin "4") (pinfunction "A16_4") (pintype "unspecified"))
    )
    (net (code "18") (name "A17") (class "Default")
      (node (ref "J100") (pin "3") (pinfunction "3_3") (pintype "input"))
      (node (ref "U101") (pin "9") (pinfunction "A6_9") (pintype "bidirectional"))
      (node (ref "U203") (pin "5") (pinfunction "I_5") (pintype "unspecified"))
      (node (ref "U300") (pin "5") (pinfunction "A17_5") (pintype "unspecified"))
    )
    (net (code "19") (name "A18") (class "Default")
      (node (ref "U101") (pin "8") (pinfunction "A5_8") (pintype "bidirectional"))
      (node (ref "U203") (pin "4") (pinfunction "I_4") (pintype "unspecified"))
      (node (ref "U300") (pin "7") (pinfunction "A18_7") (pintype "unspecified"))
    )
    (net (code "20") (name "A19") (class "Default")
      (node (ref "U101") (pin "7") (pinfunction "A4_7") (pintype "bidirectional"))
      (node (ref "U203") (pin "3") (pinfunction "I_3") (pintype "unspecified"))
      (node (ref "U300") (pin "8") (pinfunction "A19_8") (pintype "unspecified"))
    )
    (net (code "21") (name "A20") (class "Default")
      (node (ref "U101") (pin "6") (pinfunction "A3_6") (pintype "bidirectional"))
      (node (ref "U300") (pin "10") (pinfunction "A20_10") (pintype "unspecified"))
    )
    (net (code "22") (name "A21") (class "Default")
      (node (ref "U101") (pin "5") (pinfunction "A2_5") (pintype "bidirectional"))
      (node (ref "U300") (pin "11") (pinfunction "A21_11") (pintype "unspecified"))
    )
    (net (code "23") (name "A22") (class "Default")
      (node (ref "U101") (pin "4") (pinfunction "A1_4") (pintype "bidirectional"))
      (node (ref "U300") (pin "12") (pinfunction "A22_12") (pintype "unspecified"))
    )
    (net (code "24") (name "A23") (class "Default")
      (node (ref "U101") (pin "3") (pinfunction "A0_3") (pintype "bidirectional"))
      (node (ref "U203") (pin "2") (pinfunction "CLK/I_2") (pintype "unspecified"))
      (node (ref "U300") (pin "13") (pinfunction "A23_13") (pintype "unspecified"))
    )
    (net (code "25") (name "A24") (class "Default")
      (node (ref "U100") (pin "10") (pinfunction "A7_10") (pintype "bidirectional"))
      (node (ref "U201") (pin "17") (pinfunction "A7_17") (pintype "unspecified"))
      (node (ref "U300") (pin "14") (pinfunction "A24_14") (pintype "unspecified"))
    )
    (net (code "26") (name "A25") (class "Default")
      (node (ref "U100") (pin "9") (pinfunction "A6_9") (pintype "bidirectional"))
      (node (ref "U201") (pin "15") (pinfunction "A6_15") (pintype "unspecified"))
      (node (ref "U300") (pin "16") (pinfunction "A25_16") (pintype "unspecified"))
    )
    (net (code "27") (name "A26") (class "Default")
      (node (ref "U100") (pin "8") (pinfunction "A5_8") (pintype "bidirectional"))
      (node (ref "U201") (pin "13") (pinfunction "A5_13") (pintype "unspecified"))
      (node (ref "U300") (pin "17") (pinfunction "A26_17") (pintype "unspecified"))
    )
    (net (code "28") (name "A27") (class "Default")
      (node (ref "U100") (pin "7") (pinfunction "A4_7") (pintype "bidirectional"))
      (node (ref "U201") (pin "11") (pinfunction "A4_11") (pintype "unspecified"))
      (node (ref "U300") (pin "18") (pinfunction "A27_18") (pintype "unspecified"))
    )
    (net (code "29") (name "A28") (class "Default")
      (node (ref "U100") (pin "6") (pinfunction "A3_6") (pintype "bidirectional"))
      (node (ref "U201") (pin "8") (pinfunction "A3_8") (pintype "unspecified"))
      (node (ref "U300") (pin "20") (pinfunction "A28_20") (pintype "unspecified"))
    )
    (net (code "30") (name "A29") (class "Default")
      (node (ref "U100") (pin "5") (pinfunction "A2_5") (pintype "bidirectional"))
      (node (ref "U201") (pin "6") (pinfunction "A2_6") (pintype "unspecified"))
      (node (ref "U300") (pin "21") (pinfunction "A29_21") (pintype "unspecified"))
    )
    (net (code "31") (name "A30") (class "Default")
      (node (ref "U100") (pin "4") (pinfunction "A1_4") (pintype "bidirectional"))
      (node (ref "U201") (pin "4") (pinfunction "A1_4") (pintype "unspecified"))
      (node (ref "U300") (pin "23") (pinfunction "A30_23") (pintype "unspecified"))
    )
    (net (code "32") (name "A31") (class "Default")
      (node (ref "U100") (pin "3") (pinfunction "A0_3") (pintype "bidirectional"))
      (node (ref "U201") (pin "2") (pinfunction "A0_2") (pintype "unspecified"))
      (node (ref "U300") (pin "24") (pinfunction "A31_24") (pintype "unspecified"))
    )
    (net (code "33") (name "ABOEH") (class "Default")
      (node (ref "U100") (pin "13") (pinfunction "OEAB_13") (pintype "unspecified"))
      (node (ref "U100") (pin "2") (pinfunction "OEBA_2") (pintype "unspecified"))
      (node (ref "U101") (pin "13") (pinfunction "OEAB_13") (pintype "unspecified"))
      (node (ref "U101") (pin "2") (pinfunction "OEBA_2") (pintype "unspecified"))
      (node (ref "U102") (pin "13") (pinfunction "OEAB_13") (pintype "unspecified"))
      (node (ref "U102") (pin "2") (pinfunction "OEBA_2") (pintype "unspecified"))
      (node (ref "U205") (pin "27") (pinfunction "IOQ_27") (pintype "unspecified"))
      (node (ref "U306") (pin "10") (pinfunction "I_10") (pintype "unspecified"))
    )
    (net (code "34") (name "ABOEL") (class "Default")
      (node (ref "U103") (pin "19") (pinfunction "OE#_19") (pintype "unspecified"))
      (node (ref "U109") (pin "19") (pinfunction "OE#_19") (pintype "unspecified"))
      (node (ref "U205") (pin "26") (pinfunction "IOQ_26") (pintype "unspecified"))
    )
    (net (code "35") (name "BERR") (class "Default")
      (node (ref "R307B") (pin "2") (pinfunction "2_2") (pintype "input"))
      (node (ref "U202") (pin "17") (pinfunction "IOQ_17") (pintype "unspecified"))
      (node (ref "U300") (pin "37") (pinfunction "BERR/-TEA/_37") (pintype "unspecified"))
      (node (ref "U303") (pin "10") (pinfunction "I_10") (pintype "unspecified"))
      (node (ref "U306") (pin "11") (pinfunction "I_11") (pintype "unspecified"))
      (node (ref "U307") (pin "6") (pinfunction "3Y_6") (pintype "unspecified"))
    )
    (net (code "36") (name "BGACK") (class "Default")
      (node (ref "R300A") (pin "1") (pinfunction "1_1") (pintype "input"))
      (node (ref "U300") (pin "98") (pinfunction "BGACK/-BB/_98") (pintype "unspecified"))
    )
    (net (code "37") (name "BMASTER") (class "Default")
      (node (ref "U100") (pin "23") (pinfunction "CEBA_23") (pintype "unspecified"))
      (node (ref "U101") (pin "23") (pinfunction "CEBA_23") (pintype "unspecified"))
      (node (ref "U102") (pin "23") (pinfunction "CEBA_23") (pintype "unspecified"))
      (node (ref "U103") (pin "1") (pinfunction "T/R#_1") (pintype "unspecified"))
      (node (ref "U109") (pin "1") (pinfunction "T/R#_1") (pintype "unspecified"))
      (node (ref "U303") (pin "27") (pinfunction "IOQ_27") (pintype "unspecified"))
    )
    (net (code "38") (name "CBACK") (class "Default")
      (node (ref "R300B") (pin "2") (pinfunction "2_2") (pintype "input"))
      (node (ref "U300") (pin "35") (pinfunction "CBACK/-TBI/_35") (pintype "unspecified"))
      (node (ref "U306") (pin "27") (pinfunction "IOQ_27") (pintype "unspecified"))
    )
    (net (code "39") (name "CBREQ") (class "Default")
      (node (ref "R300C") (pin "1") (pinfunction "1_1") (pintype "input"))
      (node (ref "U300") (pin "33") (pinfunction "CBREQ/-TT1/_33") (pintype "unspecified"))
      (node (ref "U306") (pin "6") (pinfunction "I_6") (pintype "unspecified"))
    )
    (net (code "40") (name "CLK") (class "Default")
      (node (ref "R302B") (pin "1") (pinfunction "1_1") (pintype "input"))
      (node (ref "U205") (pin "2") (pinfunction "CLK/I_2") (pintype "unspecified"))
      (node (ref "U207") (pin "2") (pinfunction "CLK/I_2") (pintype "unspecified"))
      (node (ref "U300") (pin "41") (pinfunction "BCLK_41") (pintype "unspecified"))
      (node (ref "U303") (pin "12") (pinfunction "I_12") (pintype "unspecified"))
      (node (ref "U305") (pin "2") (pinfunction "CLK/I_2") (pintype "unspecified"))
    )
    (net (code "41") (name "CLKI") (class "Default")
      (node (ref "R302A") (pin "1") (pinfunction "1_1") (pintype "input"))
      (node (ref "U302") (pin "2") (pinfunction "D0_2") (pintype "unspecified"))
      (node (ref "U304") (pin "2") (pinfunction "CLK/I_2") (pintype "unspecified"))
      (node (ref "U306") (pin "2") (pinfunction "CLK/I_2") (pintype "unspecified"))
    )
    (net (code "42") (name "CLK_50M") (class "Default")
      (node (ref "R301A") (pin "1") (pinfunction "1_1") (pintype "input"))
      (node (ref "U300") (pin "102") (pinfunction "SCLK_102") (pintype "unspecified"))
      (node (ref "U302") (pin "3") (pinfunction "CP0_3") (pintype "unspecified"))
    )
    (net (code "43") (name "D0") (class "Default")
      (node (ref "U107") (pin "10") (pinfunction "A7_10") (pintype "bidirectional"))
      (node (ref "U204") (pin "18") (pinfunction "D7_18") (pintype "unspecified"))
      (node (ref "U204") (pin "19") (pinfunction "Q7_19") (pintype "unspecified"))
      (node (ref "U213") (pin "3") (pinfunction "O4_3") (pintype "unspecified"))
      (node (ref "U300") (pin "85") (pinfunction "D0_85") (pintype "unspecified"))
    )
    (net (code "44") (name "D1") (class "Default")
      (node (ref "U107") (pin "9") (pinfunction "A6_9") (pintype "bidirectional"))
      (node (ref "U204") (pin "16") (pinfunction "Q6_16") (pintype "unspecified"))
      (node (ref "U204") (pin "17") (pinfunction "D6_17") (pintype "unspecified"))
      (node (ref "U213") (pin "5") (pinfunction "O5_5") (pintype "unspecified"))
      (node (ref "U300") (pin "84") (pinfunction "D1_84") (pintype "unspecified"))
    )
    (net (code "45") (name "D2") (class "Default")
      (node (ref "U107") (pin "8") (pinfunction "A5_8") (pintype "bidirectional"))
      (node (ref "U204") (pin "14") (pinfunction "D5_14") (pintype "unspecified"))
      (node (ref "U204") (pin "15") (pinfunction "Q5_15") (pintype "unspecified"))
      (node (ref "U213") (pin "7") (pinfunction "O6_7") (pintype "unspecified"))
      (node (ref "U300") (pin "83") (pinfunction "D2_83") (pintype "unspecified"))
    )
    (net (code "46") (name "D2Z") (class "Default")
      (node (ref "U105") (pin "11") (pinfunction "CEAB_11") (pintype "unspecified"))
      (node (ref "U106") (pin "11") (pinfunction "CEAB_11") (pintype "unspecified"))
      (node (ref "U107") (pin "11") (pinfunction "CEAB_11") (pintype "unspecified"))
      (node (ref "U108") (pin "11") (pinfunction "CEAB_11") (pintype "unspecified"))
      (node (ref "U205") (pin "21") (pinfunction "IOQ_21") (pintype "unspecified"))
    )
    (net (code "47") (name "D3") (class "Default")
      (node (ref "U107") (pin "7") (pinfunction "A4_7") (pintype "bidirectional"))
      (node (ref "U204") (pin "12") (pinfunction "Q4_12") (pintype "unspecified"))
      (node (ref "U204") (pin "13") (pinfunction "D4_13") (pintype "unspecified"))
      (node (ref "U213") (pin "9") (pinfunction "O7_9") (pintype "unspecified"))
      (node (ref "U300") (pin "81") (pinfunction "D3_81") (pintype "unspecified"))
    )
    (net (code "48") (name "D4") (class "Default")
      (node (ref "U107") (pin "6") (pinfunction "A3_6") (pintype "bidirectional"))
      (node (ref "U204") (pin "8") (pinfunction "D3_8") (pintype "unspecified"))
      (node (ref "U204") (pin "9") (pinfunction "Q3_9") (pintype "unspecified"))
      (node (ref "U213") (pin "12") (pinfunction "O3_12") (pintype "unspecified"))
      (node (ref "U300") (pin "80") (pinfunction "D4_80") (pintype "unspecified"))
    )
    (net (code "49") (name "D5") (class "Default")
      (node (ref "U107") (pin "5") (pinfunction "A2_5") (pintype "bidirectional"))
      (node (ref "U204") (pin "6") (pinfunction "Q2_6") (pintype "unspecified"))
      (node (ref "U204") (pin "7") (pinfunction "D2_7") (pintype "unspecified"))
      (node (ref "U213") (pin "14") (pinfunction "O2_14") (pintype "unspecified"))
      (node (ref "U300") (pin "78") (pinfunction "D5_78") (pintype "unspecified"))
    )
    (net (code "50") (name "D6") (class "Default")
      (node (ref "U107") (pin "4") (pinfunction "A1_4") (pintype "bidirectional"))
      (node (ref "U204") (pin "4") (pinfunction "D1_4") (pintype "unspecified"))
      (node (ref "U204") (pin "5") (pinfunction "Q1_5") (pintype "unspecified"))
      (node (ref "U213") (pin "16") (pinfunction "O1_16") (pintype "unspecified"))
      (node (ref "U300") (pin "77") (pinfunction "D6_77") (pintype "unspecified"))
    )
    (net (code "51") (name "D7") (class "Default")
      (node (ref "U107") (pin "3") (pinfunction "A0_3") (pintype "bidirectional"))
      (node (ref "U204") (pin "2") (pinfunction "Q0_2") (pintype "unspecified"))
      (node (ref "U204") (pin "3") (pinfunction "D0_3") (pintype "unspecified"))
      (node (ref "U213") (pin "18") (pinfunction "O0_18") (pintype "unspecified"))
      (node (ref "U300") (pin "76") (pinfunction "D7_76") (pintype "unspecified"))
    )
    (net (code "52") (name "D8") (class "Default")
      (node (ref "U106") (pin "10") (pinfunction "A7_10") (pintype "bidirectional"))
      (node (ref "U300") (pin "73") (pinfunction "D8_73") (pintype "unspecified"))
    )
    (net (code "53") (name "D9") (class "Default")
      (node (ref "U106") (pin "9") (pinfunction "A6_9") (pintype "bidirectional"))
      (node (ref "U300") (pin "72") (pinfunction "D9_72") (pintype "unspecified"))
    )
    (net (code "54") (name "D10") (class "Default")
      (node (ref "U106") (pin "8") (pinfunction "A5_8") (pintype "bidirectional"))
      (node (ref "U300") (pin "71") (pinfunction "D10_71") (pintype "unspecified"))
    )
    (net (code "55") (name "D11") (class "Default")
      (node (ref "U106") (pin "7") (pinfunction "A4_7") (pintype "bidirectional"))
      (node (ref "U300") (pin "70") (pinfunction "D11_70") (pintype "unspecified"))
    )
    (net (code "56") (name "D12") (class "Default")
      (node (ref "U106") (pin "6") (pinfunction "A3_6") (pintype "bidirectional"))
      (node (ref "U206") (pin "11") (pinfunction "D0_11") (pintype "input"))
      (node (ref "U300") (pin "68") (pinfunction "D12_68") (pintype "unspecified"))
    )
    (net (code "57") (name "D13") (class "Default")
      (node (ref "U106") (pin "5") (pinfunction "A2_5") (pintype "bidirectional"))
      (node (ref "U206") (pin "12") (pinfunction "D1_12") (pintype "passive"))
      (node (ref "U300") (pin "67") (pinfunction "D13_67") (pintype "unspecified"))
    )
    (net (code "58") (name "D14") (class "Default")
      (node (ref "U106") (pin "4") (pinfunction "A1_4") (pintype "bidirectional"))
      (node (ref "U206") (pin "13") (pinfunction "D2_13") (pintype "input"))
      (node (ref "U300") (pin "66") (pinfunction "D14_66") (pintype "unspecified"))
    )
    (net (code "59") (name "D15") (class "Default")
      (node (ref "U106") (pin "3") (pinfunction "A0_3") (pintype "bidirectional"))
      (node (ref "U206") (pin "15") (pinfunction "D3_15") (pintype "output"))
      (node (ref "U300") (pin "65") (pinfunction "D15_65") (pintype "unspecified"))
    )
    (net (code "60") (name "D16") (class "Default")
      (node (ref "U108") (pin "3") (pinfunction "A0_3") (pintype "bidirectional"))
      (node (ref "U300") (pin "62") (pinfunction "D16_62") (pintype "unspecified"))
    )
    (net (code "61") (name "D17") (class "Default")
      (node (ref "U108") (pin "4") (pinfunction "A1_4") (pintype "bidirectional"))
      (node (ref "U300") (pin "60") (pinfunction "D17_60") (pintype "unspecified"))
    )
    (net (code "62") (name "D18") (class "Default")
      (node (ref "U108") (pin "5") (pinfunction "A2_5") (pintype "bidirectional"))
      (node (ref "U300") (pin "59") (pinfunction "D18_59") (pintype "unspecified"))
    )
    (net (code "63") (name "D19") (class "Default")
      (node (ref "U108") (pin "6") (pinfunction "A3_6") (pintype "bidirectional"))
      (node (ref "U300") (pin "58") (pinfunction "D19_58") (pintype "unspecified"))
    )
    (net (code "64") (name "D20") (class "Default")
      (node (ref "U108") (pin "7") (pinfunction "A4_7") (pintype "bidirectional"))
      (node (ref "U300") (pin "57") (pinfunction "D20_57") (pintype "unspecified"))
    )
    (net (code "65") (name "D21") (class "Default")
      (node (ref "U108") (pin "8") (pinfunction "A5_8") (pintype "bidirectional"))
      (node (ref "U300") (pin "56") (pinfunction "D21_56") (pintype "unspecified"))
    )
    (net (code "66") (name "D22") (class "Default")
      (node (ref "U108") (pin "9") (pinfunction "A6_9") (pintype "bidirectional"))
      (node (ref "U300") (pin "55") (pinfunction "D22_55") (pintype "unspecified"))
    )
    (net (code "67") (name "D23") (class "Default")
      (node (ref "U108") (pin "10") (pinfunction "A7_10") (pintype "bidirectional"))
      (node (ref "U300") (pin "53") (pinfunction "D23_53") (pintype "unspecified"))
    )
    (net (code "68") (name "D24") (class "Default")
      (node (ref "U105") (pin "3") (pinfunction "A0_3") (pintype "bidirectional"))
      (node (ref "U200") (pin "18") (pinfunction "D7_18") (pintype "unspecified"))
      (node (ref "U300") (pin "51") (pinfunction "D24_51") (pintype "unspecified"))
    )
    (net (code "69") (name "D25") (class "Default")
      (node (ref "U105") (pin "4") (pinfunction "A1_4") (pintype "bidirectional"))
      (node (ref "U200") (pin "17") (pinfunction "D6_17") (pintype "unspecified"))
      (node (ref "U300") (pin "50") (pinfunction "D25_50") (pintype "unspecified"))
    )
    (net (code "70") (name "D26") (class "Default")
      (node (ref "U105") (pin "5") (pinfunction "A2_5") (pintype "bidirectional"))
      (node (ref "U200") (pin "14") (pinfunction "D5_14") (pintype "unspecified"))
      (node (ref "U300") (pin "48") (pinfunction "D26_48") (pintype "unspecified"))
    )
    (net (code "71") (name "D27") (class "Default")
      (node (ref "U105") (pin "6") (pinfunction "A3_6") (pintype "bidirectional"))
      (node (ref "U200") (pin "13") (pinfunction "D4_13") (pintype "unspecified"))
      (node (ref "U300") (pin "47") (pinfunction "D27_47") (pintype "unspecified"))
    )
    (net (code "72") (name "D28") (class "Default")
      (node (ref "U105") (pin "7") (pinfunction "A4_7") (pintype "bidirectional"))
      (node (ref "U200") (pin "8") (pinfunction "D3_8") (pintype "unspecified"))
      (node (ref "U206") (pin "16") (pinfunction "D4_16") (pintype "output"))
      (node (ref "U300") (pin "45") (pinfunction "D28_45") (pintype "unspecified"))
    )
    (net (code "73") (name "D29") (class "Default")
      (node (ref "U105") (pin "8") (pinfunction "A5_8") (pintype "bidirectional"))
      (node (ref "U200") (pin "7") (pinfunction "D2_7") (pintype "unspecified"))
      (node (ref "U206") (pin "17") (pinfunction "D5_17") (pintype "output"))
      (node (ref "U300") (pin "44") (pinfunction "D29_44") (pintype "unspecified"))
    )
    (net (code "74") (name "D30") (class "Default")
      (node (ref "U105") (pin "9") (pinfunction "A6_9") (pintype "bidirectional"))
      (node (ref "U200") (pin "4") (pinfunction "D1_4") (pintype "unspecified"))
      (node (ref "U206") (pin "18") (pinfunction "D6_18") (pintype "output"))
      (node (ref "U300") (pin "43") (pinfunction "D30_43") (pintype "unspecified"))
    )
    (net (code "75") (name "D31") (class "Default")
      (node (ref "U105") (pin "10") (pinfunction "A7_10") (pintype "bidirectional"))
      (node (ref "U200") (pin "3") (pinfunction "D0_3") (pintype "unspecified"))
      (node (ref "U206") (pin "19") (pinfunction "D7_19") (pintype "output"))
      (node (ref "U300") (pin "42") (pinfunction "D31_42") (pintype "unspecified"))
    )
    (net (code "76") (name "DBLT") (class "Default")
      (node (ref "U105") (pin "1") (pinfunction "LEBA_1") (pintype "unspecified"))
      (node (ref "U105") (pin "14") (pinfunction "LEAB_14") (pintype "unspecified"))
      (node (ref "U106") (pin "1") (pinfunction "LEBA_1") (pintype "unspecified"))
      (node (ref "U106") (pin "14") (pinfunction "LEAB_14") (pintype "unspecified"))
      (node (ref "U107") (pin "1") (pinfunction "LEBA_1") (pintype "unspecified"))
      (node (ref "U107") (pin "14") (pinfunction "LEAB_14") (pintype "unspecified"))
      (node (ref "U108") (pin "1") (pinfunction "LEBA_1") (pintype "unspecified"))
      (node (ref "U108") (pin "14") (pinfunction "LEAB_14") (pintype "unspecified"))
      (node (ref "U205") (pin "24") (pinfunction "IOQ_24") (pintype "unspecified"))
    )
    (net (code "77") (name "DBOE") (class "Default")
      (node (ref "FB505") (pin "2") (pinfunction "2_2") (pintype "unspecified"))
      (node (ref "U105") (pin "13") (pinfunction "OEAB_13") (pintype "unspecified"))
      (node (ref "U105") (pin "2") (pinfunction "OEBA_2") (pintype "unspecified"))
      (node (ref "U106") (pin "13") (pinfunction "OEAB_13") (pintype "unspecified"))
      (node (ref "U106") (pin "2") (pinfunction "OEBA_2") (pintype "unspecified"))
      (node (ref "U107") (pin "13") (pinfunction "OEAB_13") (pintype "unspecified"))
      (node (ref "U107") (pin "2") (pinfunction "OEBA_2") (pintype "unspecified"))
      (node (ref "U108") (pin "13") (pinfunction "OEAB_13") (pintype "unspecified"))
      (node (ref "U108") (pin "2") (pinfunction "OEBA_2") (pintype "unspecified"))
    )
    (net (code "78") (name "DIP_EXT_TERM") (class "Default")
      (node (ref "R212G") (pin "2") (pinfunction "2_2") (pintype "input"))
      (node (ref "SW1") (pin "7") (pinfunction "PIN7_7") (pintype "unspecified"))
      (node (ref "U213") (pin "4") (pinfunction "I1_4") (pintype "unspecified"))
      (node (ref "U310") (pin "16") (pinfunction "PD#_16") (pintype "unspecified"))
      (node (ref "U311") (pin "16") (pinfunction "PD#_16") (pintype "unspecified"))
    )
    (net (code "79") (name "DIP_LONG_SPINUP") (class "Default")
      (node (ref "R212E") (pin "2") (pinfunction "2_2") (pintype "input"))
      (node (ref "SW1") (pin "5") (pinfunction "PIN5_5") (pintype "unspecified"))
      (node (ref "U213") (pin "8") (pinfunction "I3_8") (pintype "unspecified"))
    )
    (net (code "80") (name "DIP_SCSI_ADR0") (class "Default")
      (node (ref "R212A") (pin "2") (pinfunction "2_2") (pintype "input"))
      (node (ref "SW1") (pin "1") (pinfunction "PIN1_1") (pintype "unspecified"))
      (node (ref "U213") (pin "17") (pinfunction "I4_17") (pintype "unspecified"))
    )
    (net (code "81") (name "DIP_SCSI_ADR1") (class "Default")
      (node (ref "R212B") (pin "1") (pinfunction "1_1") (pintype "input"))
      (node (ref "SW1") (pin "2") (pinfunction "PIN2_2") (pintype "unspecified"))
      (node (ref "U213") (pin "15") (pinfunction "I5_15") (pintype "unspecified"))
    )
    (net (code "82") (name "DIP_SCSI_ADR2") (class "Default")
      (node (ref "R212C") (pin "1") (pinfunction "1_1") (pintype "input"))
      (node (ref "SW1") (pin "3") (pinfunction "PIN3_3") (pintype "unspecified"))
      (node (ref "U213") (pin "13") (pinfunction "I6_13") (pintype "unspecified"))
    )
    (net (code "83") (name "DIP_SCSI_FAST") (class "Default")
      (node (ref "R212D") (pin "1") (pinfunction "1_1") (pintype "input"))
      (node (ref "SW1") (pin "4") (pinfunction "PIN4_4") (pintype "unspecified"))
      (node (ref "U213") (pin "11") (pinfunction "I7_11") (pintype "unspecified"))
    )
    (net (code "84") (name "DIP_SCSI_LUNS") (class "Default")
      (node (ref "R212H") (pin "2") (pinfunction "2_2") (pintype "input"))
      (node (ref "SW1") (pin "8") (pinfunction "PIN8_8") (pintype "unspecified"))
      (node (ref "U213") (pin "2") (pinfunction "I0_2") (pintype "unspecified"))
    )
    (net (code "85") (name "DIP_SYNCH_MODE") (class "Default")
      (node (ref "R212F") (pin "2") (pinfunction "2_2") (pintype "input"))
      (node (ref "SW1") (pin "6") (pinfunction "PIN6_6") (pintype "unspecified"))
      (node (ref "U213") (pin "6") (pinfunction "I2_6") (pintype "unspecified"))
    )
    (net (code "86") (name "DP3_ABRT") (class "Default")
      (node (ref "R300P") (pin "1") (pinfunction "1_1") (pintype "input"))
      (node (ref "U300") (pin "52") (pinfunction "DP3_ABRT/_52") (pintype "unspecified"))
    )
    (net (code "87") (name "GND") (class "Default")
      (node (ref "C1") (pin "01") (pinfunction "GND_01") (pintype "bidirectional"))
      (node (ref "C1") (pin "02") (pinfunction "GND_02") (pintype "unspecified"))
      (node (ref "C1") (pin "03") (pinfunction "GND_03") (pintype "output"))
      (node (ref "C1") (pin "04") (pinfunction "GND_04") (pintype "bidirectional"))
      (node (ref "C1") (pin "100") (pinfunction "GND_100") (pintype "bidirectional"))
      (node (ref "C1") (pin "13") (pinfunction "GND_13") (pintype "bidirectional"))
      (node (ref "C1") (pin "25") (pinfunction "GND_25") (pintype "output"))
      (node (ref "C1") (pin "37") (pinfunction "GND_37") (pintype "unspecified"))
      (node (ref "C1") (pin "49") (pinfunction "GND_49") (pintype "unspecified"))
      (node (ref "C1") (pin "61") (pinfunction "GND_61") (pintype "bidirectional"))
      (node (ref "C1") (pin "73") (pinfunction "GND_73") (pintype "unspecified"))
      (node (ref "C1") (pin "85") (pinfunction "GND_85") (pintype "unspecified"))
      (node (ref "C1") (pin "87") (pinfunction "GND_87") (pintype "output"))
      (node (ref "C1") (pin "88") (pinfunction "GND_88") (pintype "bidirectional"))
      (node (ref "C1") (pin "89") (pinfunction "GND_89") (pintype "unspecified"))
      (node (ref "C1") (pin "90") (pinfunction "GND_90") (pintype "bidirectional"))
      (node (ref "C1") (pin "99") (pinfunction "GND_99") (pintype "bidirectional"))
      (node (ref "C10") (pin "2") (pinfunction "2_2") (pintype "input"))
      (node (ref "C100A") (pin "2") (pinfunction "2_2") (pintype "input"))
      (node (ref "C101A") (pin "2") (pinfunction "2_2") (pintype "input"))
      (node (ref "C102A") (pin "2") (pinfunction "2_2") (pintype "input"))
      (node (ref "C103A") (pin "2") (pinfunction "2_2") (pintype "input"))
      (node (ref "C105A") (pin "2") (pinfunction "2_2") (pintype "input"))
      (node (ref "C106A") (pin "1") (pinfunction "1_1") (pintype "input"))
      (node (ref "C107A") (pin "2") (pinfunction "2_2") (pintype "input"))
      (node (ref "C108A") (pin "2") (pinfunction "2_2") (pintype "input"))
      (node (ref "C109A") (pin "2") (pinfunction "2_2") (pintype "input"))
      (node (ref "C11") (pin "2") (pinfunction "2_2") (pintype "input"))
      (node (ref "C12") (pin "2") (pinfunction "2_2") (pintype "input"))
      (node (ref "C13") (pin "2") (pinfunction "2_2") (pintype "input"))
      (node (ref "C1A") (pin "1") (pinfunction "1_1") (pintype "input"))
      (node (ref "C1B") (pin "2") (pinfunction "2_2") (pintype "input"))
      (node (ref "C1C") (pin "2") (pinfunction "2_2") (pintype "input"))
      (node (ref "C200A") (pin "1") (pinfunction "1_1") (pintype "input"))
      (node (ref "C201A") (pin "2") (pinfunction "2_2") (pintype "input"))
      (node (ref "C202A") (pin "2") (pinfunction "2_2") (pintype "input"))
      (node (ref "C203A") (pin "2") (pinfunction "2_2") (pintype "input"))
      (node (ref "C204A") (pin "1") (pinfunction "1_1") (pintype "input"))
      (node (ref "C205A") (pin "2") (pinfunction "2_2") (pintype "input"))
      (node (ref "C206A") (pin "1") (pinfunction "1_1") (pintype "input"))
      (node (ref "C207A") (pin "2") (pinfunction "2_2") (pintype "input"))
      (node (ref "C212A") (pin "2") (pinfunction "2_2") (pintype "input"))
      (node (ref "C300A") (pin "2") (pinfunction "2_2") (pintype "input"))
      (node (ref "C300B") (pin "2") (pinfunction "2_2") (pintype "input"))
      (node (ref "C300C") (pin "2") (pinfunction "2_2") (pintype "input"))
      (node (ref "C300D") (pin "1") (pinfunction "1_1") (pintype "input"))
      (node (ref "C300E") (pin "2") (pinfunction "2_2") (pintype "input"))
      (node (ref "C300F") (pin "2") (pinfunction "2_2") (pintype "input"))
      (node (ref "C300G") (pin "2") (pinfunction "2_2") (pintype "input"))
      (node (ref "C300H") (pin "1") (pinfunction "1_1") (pintype "input"))
      (node (ref "C300I") (pin "2") (pinfunction "2_2") (pintype "input"))
      (node (ref "C301A") (pin "1") (pinfunction "1_1") (pintype "input"))
      (node (ref "C302A") (pin "2") (pinfunction "2_2") (pintype "input"))
      (node (ref "C303A") (pin "1") (pinfunction "1_1") (pintype "input"))
      (node (ref "C304A") (pin "2") (pinfunction "2_2") (pintype "input"))
      (node (ref "C305A") (pin "2") (pinfunction "2_2") (pintype "input"))
      (node (ref "C306A") (pin "2") (pinfunction "2_2") (pintype "input"))
      (node (ref "C306B") (pin "2") (pinfunction "2_2") (pintype "input"))
      (node (ref "C307A") (pin "1") (pinfunction "1_1") (pintype "input"))
      (node (ref "C310A") (pin "1") (pinfunction "1_1") (pintype "unspecified"))
      (node (ref "C310B") (pin "1") (pinfunction "1_1") (pintype "unspecified"))
      (node (ref "C310C") (pin "1") (pinfunction "1_1") (pintype "unspecified"))
      (node (ref "C310D") (pin "1") (pinfunction "1_1") (pintype "unspecified"))
      (node (ref "C310E") (pin "1") (pinfunction "1_1") (pintype "unspecified"))
      (node (ref "C310F") (pin "1") (pinfunction "1_1") (pintype "unspecified"))
      (node (ref "C310G") (pin "1") (pinfunction "1_1") (pintype "unspecified"))
      (node (ref "C310H") (pin "1") (pinfunction "1_1") (pintype "unspecified"))
      (node (ref "C310I") (pin "1") (pinfunction "1_1") (pintype "unspecified"))
      (node (ref "C310J") (pin "2") (pinfunction "2_2") (pintype "unspecified"))
      (node (ref "C310K") (pin "2") (pinfunction "2_2") (pintype "unspecified"))
      (node (ref "C310L") (pin "2") (pinfunction "2_2") (pintype "unspecified"))
      (node (ref "C310M") (pin "2") (pinfunction "2_2") (pintype "unspecified"))
      (node (ref "C310N") (pin "2") (pinfunction "2_2") (pintype "unspecified"))
      (node (ref "C310O") (pin "2") (pinfunction "2_2") (pintype "unspecified"))
      (node (ref "C310P") (pin "2") (pinfunction "2_2") (pintype "unspecified"))
      (node (ref "C310Q") (pin "2") (pinfunction "2_2") (pintype "unspecified"))
      (node (ref "C310R") (pin "2") (pinfunction "2_2") (pintype "unspecified"))
      (node (ref "C350A") (pin "2") (pinfunction "2_2") (pintype "unspecified"))
      (node (ref "C350B") (pin "1") (pinfunction "1_1") (pintype "input"))
      (node (ref "C351A") (pin "2") (pinfunction "2_2") (pintype "unspecified"))
      (node (ref "C351B") (pin "2") (pinfunction "2_2") (pintype "input"))
      (node (ref "CN2") (pin "2") (pinfunction "2_2") (pintype "unspecified"))
      (node (ref "CN2") (pin "3") (pinfunction "3_3") (pintype "unspecified"))
      (node (ref "CN309") (pin "1") (pinfunction "1_1") (pintype "input"))
      (node (ref "CN309") (pin "11") (pinfunction "11_11") (pintype "input"))
      (node (ref "CN309") (pin "13") (pinfunction "13_13") (pintype "input"))
      (node (ref "CN309") (pin "15") (pinfunction "15_15") (pintype "input"))
      (node (ref "CN309") (pin "17") (pinfunction "17_17") (pintype "input"))
      (node (ref "CN309") (pin "19") (pinfunction "19_19") (pintype "input"))
      (node (ref "CN309") (pin "20") (pinfunction "20_20") (pintype "input"))
      (node (ref "CN309") (pin "21") (pinfunction "21_21") (pintype "input"))
      (node (ref "CN309") (pin "22") (pinfunction "22_22") (pintype "input"))
      (node (ref "CN309") (pin "23") (pinfunction "23_23") (pintype "input"))
      (node (ref "CN309") (pin "24") (pinfunction "24_24") (pintype "input"))
      (node (ref "CN309") (pin "27") (pinfunction "27_27") (pintype "input"))
      (node (ref "CN309") (pin "28") (pinfunction "28_28") (pintype "input"))
      (node (ref "CN309") (pin "29") (pinfunction "29_29") (pintype "input"))
      (node (ref "CN309") (pin "3") (pinfunction "3_3") (pintype "input"))
      (node (ref "CN309") (pin "30") (pinfunction "30_30") (pintype "input"))
      (node (ref "CN309") (pin "31") (pinfunction "31_31") (pintype "input"))
      (node (ref "CN309") (pin "33") (pinfunction "33_33") (pintype "input"))
      (node (ref "CN309") (pin "35") (pinfunction "35_35") (pintype "input"))
      (node (ref "CN309") (pin "37") (pinfunction "37_37") (pintype "input"))
      (node (ref "CN309") (pin "39") (pinfunction "39_39") (pintype "input"))
      (node (ref "CN309") (pin "41") (pinfunction "41_41") (pintype "input"))
      (node (ref "CN309") (pin "43") (pinfunction "43_43") (pintype "input"))
      (node (ref "CN309") (pin "45") (pinfunction "45_45") (pintype "input"))
      (node (ref "CN309") (pin "47") (pinfunction "47_47") (pintype "input"))
      (node (ref "CN309") (pin "49") (pinfunction "49_49") (pintype "input"))
      (node (ref "CN309") (pin "5") (pinfunction "5_5") (pintype "input"))
      (node (ref "CN309") (pin "7") (pinfunction "7_7") (pintype "input"))
      (node (ref "CN309") (pin "9") (pinfunction "9_9") (pintype "input"))
      (node (ref "CN310") (pin "1") (pinfunction "1_1") (pintype "unspecified"))
      (node (ref "CN310") (pin "10") (pinfunction "10_10") (pintype "unspecified"))
      (node (ref "CN310") (pin "11") (pinfunction "11_11") (pintype "unspecified"))
      (node (ref "CN310") (pin "15") (pinfunction "15_15") (pintype "unspecified"))
      (node (ref "CN310") (pin "16") (pinfunction "16_16") (pintype "unspecified"))
      (node (ref "CN310") (pin "17") (pinfunction "17_17") (pintype "unspecified"))
      (node (ref "CN310") (pin "18") (pinfunction "18_18") (pintype "unspecified"))
      (node (ref "CN310") (pin "19") (pinfunction "19_19") (pintype "unspecified"))
      (node (ref "CN310") (pin "2") (pinfunction "2_2") (pintype "unspecified"))
      (node (ref "CN310") (pin "20") (pinfunction "20_20") (pintype "unspecified"))
      (node (ref "CN310") (pin "21") (pinfunction "21_21") (pintype "unspecified"))
      (node (ref "CN310") (pin "22") (pinfunction "22_22") (pintype "unspecified"))
      (node (ref "CN310") (pin "23") (pinfunction "23_23") (pintype "unspecified"))
      (node (ref "CN310") (pin "24") (pinfunction "24_24") (pintype "unspecified"))
      (node (ref "CN310") (pin "25") (pinfunction "25_25") (pintype "unspecified"))
      (node (ref "CN310") (pin "3") (pinfunction "3_3") (pintype "unspecified"))
      (node (ref "CN310") (pin "35") (pinfunction "35_35") (pintype "unspecified"))
      (node (ref "CN310") (pin "36") (pinfunction "36_36") (pintype "unspecified"))
      (node (ref "CN310") (pin "4") (pinfunction "4_4") (pintype "unspecified"))
      (node (ref "CN310") (pin "40") (pinfunction "40_40") (pintype "unspecified"))
      (node (ref "CN310") (pin "42") (pinfunction "42_42") (pintype "unspecified"))
      (node (ref "CN310") (pin "5") (pinfunction "5_5") (pintype "unspecified"))
      (node (ref "CN310") (pin "6") (pinfunction "6_6") (pintype "unspecified"))
      (node (ref "CN310") (pin "7") (pinfunction "7_7") (pintype "unspecified"))
      (node (ref "CN310") (pin "8") (pinfunction "8_8") (pintype "unspecified"))
      (node (ref "CN310") (pin "9") (pinfunction "9_9") (pintype "unspecified"))
      (node (ref "MH1") (pin "1") (pinfunction "1_1") (pintype "unspecified"))
      (node (ref "MH2") (pin "1") (pinfunction "1_1") (pintype "unspecified"))
      (node (ref "MH3") (pin "1") (pinfunction "1_1") (pintype "unspecified"))
      (node (ref "MH4") (pin "1") (pinfunction "1_1") (pintype "unspecified"))
      (node (ref "R109H") (pin "1") (pinfunction "1_1") (pintype "input"))
      (node (ref "RP300A") (pin "1") (pinfunction "COM1_1") (pintype "unspecified"))
      (node (ref "RP300B") (pin "1") (pinfunction "COM1_1") (pintype "unspecified"))
      (node (ref "RP300C") (pin "1") (pinfunction "COM1_1") (pintype "unspecified"))
      (node (ref "SW1") (pin "10") (pinfunction "PIN10_10") (pintype "unspecified"))
      (node (ref "SW1") (pin "11") (pinfunction "PIN11_11") (pintype "unspecified"))
      (node (ref "SW1") (pin "12") (pinfunction "PIN12_12") (pintype "unspecified"))
      (node (ref "SW1") (pin "13") (pinfunction "PIN13_13") (pintype "unspecified"))
      (node (ref "SW1") (pin "14") (pinfunction "PIN14_14") (pintype "unspecified"))
      (node (ref "SW1") (pin "15") (pinfunction "PIN15_15") (pintype "unspecified"))
      (node (ref "SW1") (pin "16") (pinfunction "PIN16_16") (pintype "unspecified"))
      (node (ref "SW1") (pin "9") (pinfunction "PIN9_9") (pintype "unspecified"))
      (node (ref "U100") (pin "12") (pinfunction "GND_12") (pintype "passive"))
      (node (ref "U100") (pin "14") (pinfunction "LEAB_14") (pintype "unspecified"))
      (node (ref "U101") (pin "12") (pinfunction "GND_12") (pintype "passive"))
      (node (ref "U101") (pin "14") (pinfunction "LEAB_14") (pintype "unspecified"))
      (node (ref "U102") (pin "12") (pinfunction "GND_12") (pintype "passive"))
      (node (ref "U102") (pin "14") (pinfunction "LEAB_14") (pintype "unspecified"))
      (node (ref "U103") (pin "10") (pinfunction "GND_10") (pintype "unspecified"))
      (node (ref "U105") (pin "12") (pinfunction "GND_12") (pintype "passive"))
      (node (ref "U106") (pin "12") (pinfunction "GND_12") (pintype "passive"))
      (node (ref "U107") (pin "12") (pinfunction "GND_12") (pintype "passive"))
      (node (ref "U108") (pin "12") (pinfunction "GND_12") (pintype "passive"))
      (node (ref "U109") (pin "10") (pinfunction "GND_10") (pintype "unspecified"))
      (node (ref "U200") (pin "10") (pinfunction "GND_10") (pintype "unspecified"))
      (node (ref "U201") (pin "1") (pinfunction "IA=B_1") (pintype "unspecified"))
      (node (ref "U201") (pin "10") (pinfunction "GND_10") (pintype "unspecified"))
      (node (ref "U202") (pin "14") (pinfunction "GND_14") (pintype "unspecified"))
      (node (ref "U203") (pin "14") (pinfunction "GND_14") (pintype "unspecified"))
      (node (ref "U204") (pin "10") (pinfunction "GND_10") (pintype "unspecified"))
      (node (ref "U205") (pin "14") (pinfunction "GND_14") (pintype "unspecified"))
      (node (ref "U206") (pin "14") (pinfunction "GND_14") (pintype "output"))
      (node (ref "U206") (pin "20") (pinfunction "CE#_20") (pintype "output"))
      (node (ref "U207") (pin "14") (pinfunction "GND_14") (pintype "unspecified"))
      (node (ref "U213") (pin "10") (pinfunction "GND_10") (pintype "unspecified"))
      (node (ref "U300") (pin "109") (pinfunction "Vss_109") (pintype "unspecified"))
      (node (ref "U300") (pin "113") (pinfunction "Vss_113") (pintype "unspecified"))
      (node (ref "U300") (pin "118") (pinfunction "Vss_118") (pintype "unspecified"))
      (node (ref "U300") (pin "123") (pinfunction "Vss_123") (pintype "unspecified"))
      (node (ref "U300") (pin "128") (pinfunction "Vss_128") (pintype "unspecified"))
      (node (ref "U300") (pin "136") (pinfunction "Vss_136") (pintype "unspecified"))
      (node (ref "U300") (pin "143") (pinfunction "Vss_143") (pintype "unspecified"))
      (node (ref "U300") (pin "149") (pinfunction "Vss_149") (pintype "unspecified"))
      (node (ref "U300") (pin "15") (pinfunction "Vss_15") (pintype "unspecified"))
      (node (ref "U300") (pin "156") (pinfunction "Vss_156") (pintype "unspecified"))
      (node (ref "U300") (pin "2") (pinfunction "Vss_2") (pintype "unspecified"))
      (node (ref "U300") (pin "22") (pinfunction "Vss_22") (pintype "unspecified"))
      (node (ref "U300") (pin "31") (pinfunction "Vss_31") (pintype "unspecified"))
      (node (ref "U300") (pin "46") (pinfunction "Vss_46") (pintype "unspecified"))
      (node (ref "U300") (pin "54") (pinfunction "Vss_54") (pintype "unspecified"))
      (node (ref "U300") (pin "61") (pinfunction "Vss_61") (pintype "unspecified"))
      (node (ref "U300") (pin "69") (pinfunction "Vss_69") (pintype "unspecified"))
      (node (ref "U300") (pin "75") (pinfunction "Vss_75") (pintype "unspecified"))
      (node (ref "U300") (pin "82") (pinfunction "Vss_82") (pintype "unspecified"))
      (node (ref "U300") (pin "9") (pinfunction "Vss_9") (pintype "unspecified"))
      (node (ref "U300") (pin "96") (pinfunction "Vss_96") (pintype "unspecified"))
      (node (ref "U301") (pin "7") (pinfunction "Gnd_7") (pintype "unspecified"))
      (node (ref "U302") (pin "7") (pinfunction "GND_7") (pintype "unspecified"))
      (node (ref "U303") (pin "14") (pinfunction "GND_14") (pintype "unspecified"))
      (node (ref "U304") (pin "14") (pinfunction "GND_14") (pintype "unspecified"))
      (node (ref "U305") (pin "14") (pinfunction "GND_14") (pintype "unspecified"))
      (node (ref "U306") (pin "14") (pinfunction "GND_14") (pintype "unspecified"))
      (node (ref "U307") (pin "11") (pinfunction "5A_11") (pintype "unspecified"))
      (node (ref "U307") (pin "13") (pinfunction "6A_13") (pintype "unspecified"))
      (node (ref "U307") (pin "7") (pinfunction "GND_7") (pintype "unspecified"))
      (node (ref "U310") (pin "8") (pinfunction "GND_8") (pintype "passive"))
      (node (ref "U311") (pin "8") (pinfunction "GND_8") (pintype "passive"))
    )
    (net (code "88") (name "IORST") (class "Default")
      (node (ref "R307A") (pin "1") (pinfunction "1_1") (pintype "input"))
      (node (ref "U202") (pin "19") (pinfunction "IOQ_19") (pintype "unspecified"))
      (node (ref "U203") (pin "27") (pinfunction "IOQ_27") (pintype "unspecified"))
      (node (ref "U207") (pin "9") (pinfunction "I_9") (pintype "unspecified"))
      (node (ref "U300") (pin "94") (pinfunction "RESET/_94") (pintype "unspecified"))
      (node (ref "U303") (pin "11") (pinfunction "I_11") (pintype "unspecified"))
      (node (ref "U306") (pin "12") (pinfunction "I_12") (pintype "unspecified"))
      (node (ref "U307") (pin "8") (pinfunction "4Y_8") (pintype "unspecified"))
    )
    (net (code "89") (name "LED") (class "Default")
      (node (ref "R398") (pin "2") (pinfunction "2_2") (pintype "unspecified"))
      (node (ref "U307") (pin "2") (pinfunction "1Y_2") (pintype "unspecified"))
      (node (ref "U307") (pin "4") (pinfunction "2Y_4") (pintype "unspecified"))
    )
    (net (code "90") (name "LEDR") (class "Default")
      (node (ref "CN308") (pin "1") (pinfunction "1_1") (pintype "input"))
      (node (ref "CN308") (pin "3") (pinfunction "3_3") (pintype "input"))
      (node (ref "CN351") (pin "1") (pinfunction "1_1") (pintype "input"))
      (node (ref "CN351") (pin "3") (pinfunction "3_3") (pintype "input"))
      (node (ref "R398") (pin "1") (pinfunction "1_1") (pintype "unspecified"))
    )
    (net (code "91") (name "M24") (class "Default")
      (node (ref "R200H") (pin "1") (pinfunction "1_1") (pintype "input"))
      (node (ref "U200") (pin "19") (pinfunction "Q7_19") (pintype "unspecified"))
      (node (ref "U201") (pin "18") (pinfunction "B7_18") (pintype "unspecified"))
    )
    (net (code "92") (name "M25") (class "Default")
      (node (ref "R200G") (pin "1") (pinfunction "1_1") (pintype "input"))
      (node (ref "U200") (pin "16") (pinfunction "Q6_16") (pintype "unspecified"))
      (node (ref "U201") (pin "16") (pinfunction "B6_16") (pintype "unspecified"))
    )
    (net (code "93") (name "M26") (class "Default")
      (node (ref "R200F") (pin "1") (pinfunction "1_1") (pintype "input"))
      (node (ref "U200") (pin "15") (pinfunction "Q5_15") (pintype "unspecified"))
      (node (ref "U201") (pin "14") (pinfunction "B5_14") (pintype "unspecified"))
    )
    (net (code "94") (name "M27") (class "Default")
      (node (ref "R200E") (pin "1") (pinfunction "1_1") (pintype "input"))
      (node (ref "U200") (pin "12") (pinfunction "Q4_12") (pintype "unspecified"))
      (node (ref "U201") (pin "12") (pinfunction "B4_12") (pintype "unspecified"))
    )
    (net (code "95") (name "M28") (class "Default")
      (node (ref "R200D") (pin "1") (pinfunction "1_1") (pintype "input"))
      (node (ref "U200") (pin "9") (pinfunction "Q3_9") (pintype "unspecified"))
      (node (ref "U201") (pin "9") (pinfunction "B3_9") (pintype "unspecified"))
    )
    (net (code "96") (name "M29") (class "Default")
      (node (ref "R200C") (pin "1") (pinfunction "1_1") (pintype "input"))
      (node (ref "U200") (pin "6") (pinfunction "Q2_6") (pintype "unspecified"))
      (node (ref "U201") (pin "7") (pinfunction "B2_7") (pintype "unspecified"))
    )
    (net (code "97") (name "M30") (class "Default")
      (node (ref "R200B") (pin "1") (pinfunction "1_1") (pintype "input"))
      (node (ref "U200") (pin "5") (pinfunction "Q1_5") (pintype "unspecified"))
      (node (ref "U201") (pin "5") (pinfunction "B1_5") (pintype "unspecified"))
    )
    (net (code "98") (name "M31") (class "Default")
      (node (ref "R200A") (pin "1") (pinfunction "1_1") (pintype "input"))
      (node (ref "U200") (pin "2") (pinfunction "Q0_2") (pintype "unspecified"))
      (node (ref "U201") (pin "3") (pinfunction "B0_3") (pintype "unspecified"))
    )
    (net (code "99") (name "MASTER") (class "Default")
      (node (ref "FB502") (pin "1") (pinfunction "1_1") (pintype "unspecified"))
      (node (ref "U100") (pin "11") (pinfunction "CEAB_11") (pintype "unspecified"))
      (node (ref "U101") (pin "11") (pinfunction "CEAB_11") (pintype "unspecified"))
      (node (ref "U102") (pin "11") (pinfunction "CEAB_11") (pintype "unspecified"))
      (node (ref "U205") (pin "18") (pinfunction "IOQ_18") (pintype "unspecified"))
      (node (ref "U303") (pin "3") (pinfunction "I_3") (pintype "unspecified"))
    )
    (net (code "100") (name "MATCH") (class "Default")
      (node (ref "U201") (pin "19") (pinfunction "OA=B_19") (pintype "unspecified"))
      (node (ref "U202") (pin "2") (pinfunction "CLK/I_2") (pintype "unspecified"))
    )
    (net (code "101") (name "NCR_INT") (class "Default")
      (node (ref "U207") (pin "10") (pinfunction "I_10") (pintype "unspecified"))
      (node (ref "U300") (pin "105") (pinfunction "IRQ/_105") (pintype "unspecified"))
    )
    (net (code "102") (name "Net-(C310A-Pad2)") (class "Default")
      (node (ref "C310A") (pin "2") (pinfunction "2_2") (pintype "unspecified"))
      (node (ref "CN310") (pin "50") (pinfunction "50_50") (pintype "unspecified"))
      (node (ref "FB310A") (pin "2") (pinfunction "2_2") (pintype "unspecified"))
    )
    (net (code "103") (name "Net-(C310B-Pad2)") (class "Default")
      (node (ref "C310B") (pin "2") (pinfunction "2_2") (pintype "unspecified"))
      (node (ref "CN310") (pin "49") (pinfunction "49_49") (pintype "unspecified"))
      (node (ref "FB310B") (pin "2") (pinfunction "2_2") (pintype "unspecified"))
    )
    (net (code "104") (name "Net-(C310C-Pad2)") (class "Default")
      (node (ref "C310C") (pin "2") (pinfunction "2_2") (pintype "unspecified"))
      (node (ref "CN310") (pin "48") (pinfunction "48_48") (pintype "unspecified"))
      (node (ref "FB310C") (pin "2") (pinfunction "2_2") (pintype "unspecified"))
    )
    (net (code "105") (name "Net-(C310D-Pad2)") (class "Default")
      (node (ref "C310D") (pin "2") (pinfunction "2_2") (pintype "unspecified"))
      (node (ref "CN310") (pin "47") (pinfunction "47_47") (pintype "unspecified"))
      (node (ref "FB310D") (pin "2") (pinfunction "2_2") (pintype "unspecified"))
    )
    (net (code "106") (name "Net-(C310E-Pad2)") (class "Default")
      (node (ref "C310E") (pin "2") (pinfunction "2_2") (pintype "unspecified"))
      (node (ref "CN310") (pin "46") (pinfunction "46_46") (pintype "unspecified"))
      (node (ref "FB310E") (pin "2") (pinfunction "2_2") (pintype "unspecified"))
    )
    (net (code "107") (name "Net-(C310F-Pad2)") (class "Default")
      (node (ref "C310F") (pin "2") (pinfunction "2_2") (pintype "unspecified"))
      (node (ref "CN310") (pin "45") (pinfunction "45_45") (pintype "unspecified"))
      (node (ref "FB310F") (pin "2") (pinfunction "2_2") (pintype "unspecified"))
    )
    (net (code "108") (name "Net-(C310G-Pad2)") (class "Default")
      (node (ref "C310G") (pin "2") (pinfunction "2_2") (pintype "unspecified"))
      (node (ref "CN310") (pin "44") (pinfunction "44_44") (pintype "unspecified"))
      (node (ref "FB310G") (pin "2") (pinfunction "2_2") (pintype "unspecified"))
    )
    (net (code "109") (name "Net-(C310H-Pad2)") (class "Default")
      (node (ref "C310H") (pin "2") (pinfunction "2_2") (pintype "unspecified"))
      (node (ref "CN310") (pin "43") (pinfunction "43_43") (pintype "unspecified"))
      (node (ref "FB310H") (pin "2") (pinfunction "2_2") (pintype "unspecified"))
    )
    (net (code "110") (name "Net-(C310I-Pad2)") (class "Default")
      (node (ref "C310I") (pin "2") (pinfunction "2_2") (pintype "unspecified"))
      (node (ref "CN310") (pin "41") (pinfunction "41_41") (pintype "unspecified"))
      (node (ref "FB310I") (pin "2") (pinfunction "2_2") (pintype "unspecified"))
    )
    (net (code "111") (name "Net-(C310J-Pad1)") (class "Default")
      (node (ref "C310J") (pin "1") (pinfunction "1_1") (pintype "unspecified"))
      (node (ref "CN310") (pin "34") (pinfunction "34_34") (pintype "unspecified"))
      (node (ref "FB310J") (pin "2") (pinfunction "2_2") (pintype "unspecified"))
    )
    (net (code "112") (name "Net-(C310K-Pad1)") (class "Default")
      (node (ref "C310K") (pin "1") (pinfunction "1_1") (pintype "unspecified"))
      (node (ref "CN310") (pin "26") (pinfunction "26_26") (pintype "unspecified"))
      (node (ref "FB310K") (pin "2") (pinfunction "2_2") (pintype "unspecified"))
    )
    (net (code "113") (name "Net-(C310L-Pad1)") (class "Default")
      (node (ref "C310L") (pin "1") (pinfunction "1_1") (pintype "unspecified"))
      (node (ref "CN310") (pin "27") (pinfunction "27_27") (pintype "unspecified"))
      (node (ref "FB310L") (pin "2") (pinfunction "2_2") (pintype "unspecified"))
    )
    (net (code "114") (name "Net-(C310M-Pad1)") (class "Default")
      (node (ref "C310M") (pin "1") (pinfunction "1_1") (pintype "unspecified"))
      (node (ref "CN310") (pin "28") (pinfunction "28_28") (pintype "unspecified"))
      (node (ref "FB310M") (pin "2") (pinfunction "2_2") (pintype "unspecified"))
    )
    (net (code "115") (name "Net-(C310N-Pad1)") (class "Default")
      (node (ref "C310N") (pin "1") (pinfunction "1_1") (pintype "unspecified"))
      (node (ref "CN310") (pin "29") (pinfunction "29_29") (pintype "unspecified"))
      (node (ref "FB310N") (pin "2") (pinfunction "2_2") (pintype "unspecified"))
    )
    (net (code "116") (name "Net-(C310O-Pad1)") (class "Default")
      (node (ref "C310O") (pin "1") (pinfunction "1_1") (pintype "unspecified"))
      (node (ref "CN310") (pin "30") (pinfunction "30_30") (pintype "unspecified"))
      (node (ref "FB310O") (pin "2") (pinfunction "2_2") (pintype "unspecified"))
    )
    (net (code "117") (name "Net-(C310P-Pad1)") (class "Default")
      (node (ref "C310P") (pin "1") (pinfunction "1_1") (pintype "unspecified"))
      (node (ref "CN310") (pin "31") (pinfunction "31_31") (pintype "unspecified"))
      (node (ref "FB310P") (pin "2") (pinfunction "2_2") (pintype "unspecified"))
    )
    (net (code "118") (name "Net-(C310Q-Pad1)") (class "Default")
      (node (ref "C310Q") (pin "1") (pinfunction "1_1") (pintype "unspecified"))
      (node (ref "CN310") (pin "32") (pinfunction "32_32") (pintype "unspecified"))
      (node (ref "FB310Q") (pin "2") (pinfunction "2_2") (pintype "unspecified"))
    )
    (net (code "119") (name "Net-(C310R-Pad1)") (class "Default")
      (node (ref "C310R") (pin "1") (pinfunction "1_1") (pintype "unspecified"))
      (node (ref "CN310") (pin "33") (pinfunction "33_33") (pintype "unspecified"))
      (node (ref "FB310R") (pin "2") (pinfunction "2_2") (pintype "unspecified"))
    )
    (net (code "120") (name "Net-(CN309-Pad2)") (class "Default")
      (node (ref "CN309") (pin "2") (pinfunction "2_2") (pintype "input"))
      (node (ref "FB311A") (pin "1") (pinfunction "1_1") (pintype "unspecified"))
    )
    (net (code "121") (name "Net-(CN309-Pad4)") (class "Default")
      (node (ref "CN309") (pin "4") (pinfunction "4_4") (pintype "input"))
      (node (ref "FB311B") (pin "1") (pinfunction "1_1") (pintype "unspecified"))
    )
    (net (code "122") (name "Net-(CN309-Pad6)") (class "Default")
      (node (ref "CN309") (pin "6") (pinfunction "6_6") (pintype "input"))
      (node (ref "FB311C") (pin "1") (pinfunction "1_1") (pintype "unspecified"))
    )
    (net (code "123") (name "Net-(CN309-Pad8)") (class "Default")
      (node (ref "CN309") (pin "8") (pinfunction "8_8") (pintype "input"))
      (node (ref "FB311D") (pin "1") (pinfunction "1_1") (pintype "unspecified"))
    )
    (net (code "124") (name "Net-(CN309-Pad10)") (class "Default")
      (node (ref "CN309") (pin "10") (pinfunction "10_10") (pintype "input"))
      (node (ref "FB311E") (pin "1") (pinfunction "1_1") (pintype "unspecified"))
    )
    (net (code "125") (name "Net-(CN309-Pad12)") (class "Default")
      (node (ref "CN309") (pin "12") (pinfunction "12_12") (pintype "input"))
      (node (ref "FB311F") (pin "1") (pinfunction "1_1") (pintype "unspecified"))
    )
    (net (code "126") (name "Net-(CN309-Pad14)") (class "Default")
      (node (ref "CN309") (pin "14") (pinfunction "14_14") (pintype "input"))
      (node (ref "FB311G") (pin "1") (pinfunction "1_1") (pintype "unspecified"))
    )
    (net (code "127") (name "Net-(CN309-Pad16)") (class "Default")
      (node (ref "CN309") (pin "16") (pinfunction "16_16") (pintype "input"))
      (node (ref "FB311H") (pin "1") (pinfunction "1_1") (pintype "unspecified"))
    )
    (net (code "128") (name "Net-(CN309-Pad18)") (class "Default")
      (node (ref "CN309") (pin "18") (pinfunction "18_18") (pintype "input"))
      (node (ref "FB311I") (pin "1") (pinfunction "1_1") (pintype "unspecified"))
    )
    (net (code "129") (name "Net-(CN309-Pad32)") (class "Default")
      (node (ref "CN309") (pin "32") (pinfunction "32_32") (pintype "input"))
      (node (ref "FB311J") (pin "1") (pinfunction "1_1") (pintype "unspecified"))
    )
    (net (code "130") (name "Net-(CN309-Pad38)") (class "Default")
      (node (ref "CN309") (pin "38") (pinfunction "38_38") (pintype "input"))
      (node (ref "FB311Q") (pin "1") (pinfunction "1_1") (pintype "unspecified"))
    )
    (net (code "131") (name "Net-(CN309-Pad40)") (class "Default")
      (node (ref "CN309") (pin "40") (pinfunction "40_40") (pintype "input"))
      (node (ref "FB311P") (pin "1") (pinfunction "1_1") (pintype "unspecified"))
    )
    (net (code "132") (name "Net-(CN309-Pad42)") (class "Default")
      (node (ref "CN309") (pin "42") (pinfunction "42_42") (pintype "input"))
      (node (ref "FB311O") (pin "1") (pinfunction "1_1") (pintype "unspecified"))
    )
    (net (code "133") (name "Net-(CN309-Pad44)") (class "Default")
      (node (ref "CN309") (pin "44") (pinfunction "44_44") (pintype "input"))
      (node (ref "FB311N") (pin "1") (pinfunction "1_1") (pintype "unspecified"))
    )
    (net (code "134") (name "Net-(CN309-Pad46)") (class "Default")
      (node (ref "CN309") (pin "46") (pinfunction "46_46") (pintype "input"))
      (node (ref "FB311M") (pin "1") (pinfunction "1_1") (pintype "unspecified"))
    )
    (net (code "135") (name "Net-(CN309-Pad48)") (class "Default")
      (node (ref "CN309") (pin "48") (pinfunction "48_48") (pintype "input"))
      (node (ref "FB311L") (pin "1") (pinfunction "1_1") (pintype "unspecified"))
    )
    (net (code "136") (name "Net-(CN309-Pad50)") (class "Default")
      (node (ref "CN309") (pin "50") (pinfunction "50_50") (pintype "input"))
      (node (ref "FB311K") (pin "1") (pinfunction "1_1") (pintype "unspecified"))
    )
    (net (code "137") (name "Net-(D309A-C)") (class "Default")
      (node (ref "D309A") (pin "1") (pinfunction "C_1") (pintype "unspecified"))
      (node (ref "F309A") (pin "1") (pinfunction "1_1") (pintype "unspecified"))
      (node (ref "F309B") (pin "1") (pinfunction "1_1") (pintype "unspecified"))
    )
    (net (code "138") (name "Net-(FB500-Pad1)") (class "Default")
      (node (ref "FB500") (pin "1") (pinfunction "1_1") (pintype "unspecified"))
      (node (ref "U305") (pin "19") (pinfunction "IOQ_19") (pintype "unspecified"))
    )
    (net (code "139") (name "Net-(FB501-Pad1)") (class "Default")
      (node (ref "FB501") (pin "1") (pinfunction "1_1") (pintype "unspecified"))
      (node (ref "U306") (pin "21") (pinfunction "IOQ_21") (pintype "unspecified"))
    )
    (net (code "140") (name "Net-(FB504-Pad1)") (class "Default")
      (node (ref "FB504") (pin "1") (pinfunction "1_1") (pintype "unspecified"))
      (node (ref "U205") (pin "23") (pinfunction "IOQ_23") (pintype "unspecified"))
    )
    (net (code "141") (name "Net-(FB505-Pad1)") (class "Default")
      (node (ref "FB505") (pin "1") (pinfunction "1_1") (pintype "unspecified"))
      (node (ref "U205") (pin "25") (pinfunction "IOQ_25") (pintype "unspecified"))
    )
    (net (code "142") (name "Net-(U109-B4)") (class "Default")
      (node (ref "FB507") (pin "1") (pinfunction "1_1") (pintype "unspecified"))
      (node (ref "U109") (pin "14") (pinfunction "B4_14") (pintype "unspecified"))
    )
    (net (code "143") (name "Net-(U109-B5)") (class "Default")
      (node (ref "FB508") (pin "1") (pinfunction "1_1") (pintype "unspecified"))
      (node (ref "U109") (pin "13") (pinfunction "B5_13") (pintype "unspecified"))
    )
    (net (code "144") (name "Net-(U300-BR{slash})") (class "Default")
      (node (ref "FB503") (pin "1") (pinfunction "1_1") (pintype "unspecified"))
      (node (ref "U300") (pin "101") (pinfunction "BR/_101") (pintype "unspecified"))
    )
    (net (code "145") (name "Net-(U300-DP0)") (class "Default")
      (node (ref "R300M") (pin "2") (pinfunction "2_2") (pintype "input"))
      (node (ref "U300") (pin "86") (pinfunction "DP0_86") (pintype "unspecified"))
    )
    (net (code "146") (name "Net-(U300-DP1)") (class "Default")
      (node (ref "R300N") (pin "1") (pinfunction "1_1") (pintype "input"))
      (node (ref "U300") (pin "74") (pinfunction "DP1_74") (pintype "unspecified"))
    )
    (net (code "147") (name "Net-(U300-DP2)") (class "Default")
      (node (ref "R300O") (pin "1") (pinfunction "1_1") (pintype "input"))
      (node (ref "U300") (pin "63") (pinfunction "DP2_63") (pintype "unspecified"))
    )
    (net (code "148") (name "Net-(U300-MASTER{slash})") (class "Default")
      (node (ref "FB502") (pin "2") (pinfunction "2_2") (pintype "unspecified"))
      (node (ref "U300") (pin "38") (pinfunction "MASTER/_38") (pintype "unspecified"))
    )
    (net (code "149") (name "Net-(U300-R_W{slash})") (class "Default")
      (node (ref "FB506") (pin "2") (pinfunction "2_2") (pintype "unspecified"))
      (node (ref "U300") (pin "32") (pinfunction "R_W/_32") (pintype "unspecified"))
    )
    (net (code "150") (name "Net-(U301-Out)") (class "Default")
      (node (ref "R301A") (pin "2") (pinfunction "2_2") (pintype "input"))
      (node (ref "U301") (pin "8") (pinfunction "Out_8") (pintype "unspecified"))
    )
    (net (code "151") (name "Net-(U302-Q0#)") (class "Default")
      (node (ref "R302A") (pin "2") (pinfunction "2_2") (pintype "input"))
      (node (ref "U302") (pin "6") (pinfunction "Q0#_6") (pintype "unspecified"))
    )
    (net (code "152") (name "Net-(U302-Q0)") (class "Default")
      (node (ref "R302B") (pin "2") (pinfunction "2_2") (pintype "input"))
      (node (ref "U302") (pin "5") (pinfunction "Q0_5") (pintype "unspecified"))
    )
    (net (code "153") (name "Net-(U310-VREF1)") (class "Default")
      (node (ref "C350A") (pin "1") (pinfunction "1_1") (pintype "unspecified"))
      (node (ref "C350B") (pin "2") (pinfunction "2_2") (pintype "input"))
      (node (ref "U310") (pin "15") (pinfunction "VREF2_15") (pintype "passive"))
      (node (ref "U310") (pin "7") (pinfunction "VREF1_7") (pintype "passive"))
    )
    (net (code "154") (name "Net-(U311-VREF1)") (class "Default")
      (node (ref "C351A") (pin "1") (pinfunction "1_1") (pintype "unspecified"))
      (node (ref "C351B") (pin "1") (pinfunction "1_1") (pintype "input"))
      (node (ref "U311") (pin "15") (pinfunction "VREF2_15") (pintype "passive"))
      (node (ref "U311") (pin "7") (pinfunction "VREF1_7") (pintype "passive"))
    )
    (net (code "155") (name "Net-(U400-VREF1)") (class "Default")
      (node (ref "C400A") (pin "1") (pinfunction "1_1") (pintype "unspecified"))
      (node (ref "C400B") (pin "2") (pinfunction "2_2") (pintype "input"))
      (node (ref "U400") (pin "15") (pinfunction "VREF2_15") (pintype "passive"))
      (node (ref "U400") (pin "7") (pinfunction "VREF1_7") (pintype "passive"))
    )
    (net (code "156") (name "Net-(U401-VREF1)") (class "Default")
      (node (ref "C401A") (pin "1") (pinfunction "1_1") (pintype "unspecified"))
      (node (ref "C401B") (pin "2") (pinfunction "2_2") (pintype "input"))
      (node (ref "U401") (pin "15") (pinfunction "VREF2_15") (pintype "passive"))
      (node (ref "U401") (pin "7") (pinfunction "VREF1_7") (pintype "passive"))
    )
    (net (code "157") (name "PLD_AS") (class "Default")
      (node (ref "R300H") (pin "1") (pinfunction "1_1") (pintype "input"))
      (node (ref "U300") (pin "25") (pinfunction "AS/-TS/_25") (pintype "unspecified"))
      (node (ref "U304") (pin "21") (pinfunction "IOQ_21") (pintype "unspecified"))
      (node (ref "U305") (pin "4") (pinfunction "I_4") (pintype "unspecified"))
    )
    (net (code "158") (name "PLD_ASQ") (class "Default")
      (node (ref "U305") (pin "20") (pinfunction "IOQ_20") (pintype "unspecified"))
      (node (ref "U306") (pin "13") (pinfunction "I_13") (pintype "unspecified"))
    )
    (net (code "159") (name "PLD_CFGLT") (class "Default")
      (node (ref "U200") (pin "11") (pinfunction "CP_11") (pintype "unspecified"))
      (node (ref "U202") (pin "23") (pinfunction "IOQ_23") (pintype "unspecified"))
    )
    (net (code "160") (name "PLD_DOE") (class "Default")
      (node (ref "R109H") (pin "2") (pinfunction "2_2") (pintype "input"))
      (node (ref "U109") (pin "4") (pinfunction "A2_4") (pintype "unspecified"))
      (node (ref "U205") (pin "5") (pinfunction "I_5") (pintype "unspecified"))
      (node (ref "U304") (pin "10") (pinfunction "I_10") (pintype "unspecified"))
      (node (ref "U305") (pin "27") (pinfunction "IOQ_27") (pintype "unspecified"))
      (node (ref "U306") (pin "23") (pinfunction "IOQ_23") (pintype "unspecified"))
    )
    (net (code "161") (name "PLD_DS") (class "Default")
      (node (ref "R300G") (pin "1") (pinfunction "1_1") (pintype "input"))
      (node (ref "U300") (pin "87") (pinfunction "DS/-DLE_87") (pintype "unspecified"))
      (node (ref "U304") (pin "20") (pinfunction "IOQ_20") (pintype "unspecified"))
    )
    (net (code "162") (name "PLD_DS0") (class "Default")
      (node (ref "R109A") (pin "1") (pinfunction "1_1") (pintype "input"))
      (node (ref "U109") (pin "9") (pinfunction "A7_9") (pintype "unspecified"))
      (node (ref "U203") (pin "10") (pinfunction "I_10") (pintype "unspecified"))
      (node (ref "U207") (pin "6") (pinfunction "I_6") (pintype "unspecified"))
      (node (ref "U304") (pin "9") (pinfunction "I_9") (pintype "unspecified"))
      (node (ref "U305") (pin "23") (pinfunction "IOQ_23") (pintype "unspecified"))
    )
    (net (code "163") (name "PLD_DS1") (class "Default")
      (node (ref "R109B") (pin "1") (pinfunction "1_1") (pintype "input"))
      (node (ref "U109") (pin "8") (pinfunction "A6_8") (pintype "unspecified"))
      (node (ref "U304") (pin "7") (pinfunction "I_7") (pintype "unspecified"))
      (node (ref "U305") (pin "24") (pinfunction "IOQ_24") (pintype "unspecified"))
    )
    (net (code "164") (name "PLD_DS2") (class "Default")
      (node (ref "R109C") (pin "1") (pinfunction "1_1") (pintype "input"))
      (node (ref "U109") (pin "7") (pinfunction "A5_7") (pintype "unspecified"))
      (node (ref "U304") (pin "6") (pinfunction "I_6") (pintype "unspecified"))
      (node (ref "U305") (pin "25") (pinfunction "IOQ_25") (pintype "unspecified"))
    )
    (net (code "165") (name "PLD_DS3") (class "Default")
      (node (ref "R109D") (pin "1") (pinfunction "1_1") (pintype "input"))
      (node (ref "U109") (pin "6") (pinfunction "A4_6") (pintype "unspecified"))
      (node (ref "U202") (pin "11") (pinfunction "I_11") (pintype "unspecified"))
      (node (ref "U304") (pin "5") (pinfunction "I_5") (pintype "unspecified"))
      (node (ref "U305") (pin "26") (pinfunction "IOQ_26") (pintype "unspecified"))
    )
    (net (code "166") (name "PLD_DTACK") (class "Default")
      (node (ref "U303") (pin "9") (pinfunction "I_9") (pintype "unspecified"))
      (node (ref "U304") (pin "11") (pinfunction "I_11") (pintype "unspecified"))
      (node (ref "U306") (pin "17") (pinfunction "IOQ_17") (pintype "unspecified"))
    )
    (net (code "167") (name "PLD_FC0") (class "Default")
      (node (ref "R109F") (pin "1") (pinfunction "1_1") (pintype "input"))
      (node (ref "U109") (pin "3") (pinfunction "A1_3") (pintype "unspecified"))
      (node (ref "U202") (pin "16") (pinfunction "I_16") (pintype "unspecified"))
      (node (ref "U300") (pin "30") (pinfunction "FC0-TM0_30") (pintype "unspecified"))
    )
    (net (code "168") (name "PLD_FC1") (class "Default")
      (node (ref "R109G") (pin "1") (pinfunction "1_1") (pintype "input"))
      (node (ref "U109") (pin "2") (pinfunction "A0_2") (pintype "unspecified"))
      (node (ref "U202") (pin "13") (pinfunction "I_13") (pintype "unspecified"))
      (node (ref "U300") (pin "29") (pinfunction "FC1-TM1_29") (pintype "unspecified"))
    )
    (net (code "169") (name "PLD_FC2") (class "Default")
      (node (ref "R103A") (pin "1") (pinfunction "1_1") (pintype "input"))
      (node (ref "U103") (pin "8") (pinfunction "A6_8") (pintype "unspecified"))
      (node (ref "U203") (pin "11") (pinfunction "I_11") (pintype "unspecified"))
      (node (ref "U300") (pin "28") (pinfunction "FC2-TM2_28") (pintype "unspecified"))
    )
    (net (code "170") (name "PLD_FCS") (class "Default")
      (node (ref "FB500") (pin "2") (pinfunction "2_2") (pintype "unspecified"))
      (node (ref "U100") (pin "1") (pinfunction "LEBA_1") (pintype "unspecified"))
      (node (ref "U101") (pin "1") (pinfunction "LEBA_1") (pintype "unspecified"))
      (node (ref "U102") (pin "1") (pinfunction "LEBA_1") (pintype "unspecified"))
      (node (ref "U202") (pin "12") (pinfunction "I_12") (pintype "unspecified"))
      (node (ref "U203") (pin "12") (pinfunction "I_12") (pintype "unspecified"))
      (node (ref "U205") (pin "6") (pinfunction "I_6") (pintype "unspecified"))
      (node (ref "U207") (pin "12") (pinfunction "I_12") (pintype "unspecified"))
      (node (ref "U303") (pin "6") (pinfunction "I_6") (pintype "unspecified"))
      (node (ref "U306") (pin "4") (pinfunction "I_4") (pintype "unspecified"))
    )
    (net (code "171") (name "PLD_INT") (class "Default")
      (node (ref "U203") (pin "7") (pinfunction "I_7") (pintype "unspecified"))
      (node (ref "U207") (pin "26") (pinfunction "IOQ_26") (pintype "unspecified"))
    )
    (net (code "172") (name "PLD_INTREG") (class "Default")
      (node (ref "U203") (pin "24") (pinfunction "IOQ_24") (pintype "unspecified"))
      (node (ref "U204") (pin "11") (pinfunction "CP_11") (pintype "unspecified"))
      (node (ref "U205") (pin "11") (pinfunction "I_11") (pintype "unspecified"))
    )
    (net (code "173") (name "PLD_INTSPC") (class "Default")
      (node (ref "U202") (pin "27") (pinfunction "IOQ_27") (pintype "unspecified"))
      (node (ref "U203") (pin "16") (pinfunction "I_16") (pintype "unspecified"))
    )
    (net (code "174") (name "PLD_INTVEC") (class "Default")
      (node (ref "U203") (pin "23") (pinfunction "IOQ_23") (pintype "unspecified"))
      (node (ref "U204") (pin "1") (pinfunction "OE#_1") (pintype "unspecified"))
      (node (ref "U205") (pin "12") (pinfunction "I_12") (pintype "unspecified"))
      (node (ref "U207") (pin "11") (pinfunction "I_11") (pintype "unspecified"))
    )
    (net (code "175") (name "PLD_MTCR") (class "Default")
      (node (ref "R109E") (pin "1") (pinfunction "1_1") (pintype "input"))
      (node (ref "U109") (pin "5") (pinfunction "A3_5") (pintype "unspecified"))
      (node (ref "U203") (pin "13") (pinfunction "I_13") (pintype "unspecified"))
      (node (ref "U205") (pin "17") (pinfunction "IOQ_17") (pintype "unspecified"))
      (node (ref "U305") (pin "10") (pinfunction "I_10") (pintype "unspecified"))
      (node (ref "U306") (pin "25") (pinfunction "IOQ_25") (pintype "unspecified"))
    )
    (net (code "176") (name "PLD_MYBUS") (class "Default")
      (node (ref "U205") (pin "4") (pinfunction "I_4") (pintype "unspecified"))
      (node (ref "U303") (pin "20") (pinfunction "IOQ_20") (pintype "unspecified"))
      (node (ref "U304") (pin "13") (pinfunction "I_13") (pintype "unspecified"))
      (node (ref "U305") (pin "3") (pinfunction "I_3") (pintype "unspecified"))
      (node (ref "U306") (pin "3") (pinfunction "I_3") (pintype "unspecified"))
    )
    (net (code "177") (name "PLD_NACK") (class "Default")
      (node (ref "U205") (pin "16") (pinfunction "I_16") (pintype "unspecified"))
      (node (ref "U207") (pin "24") (pinfunction "IOQ_24") (pintype "unspecified"))
    )
    (net (code "178") (name "PLD_NOZ3") (class "Default")
      (node (ref "U205") (pin "10") (pinfunction "I_10") (pintype "unspecified"))
      (node (ref "U305") (pin "9") (pinfunction "I_9") (pintype "unspecified"))
      (node (ref "U306") (pin "20") (pinfunction "IOQ_20") (pintype "unspecified"))
    )
    (net (code "179") (name "PLD_READ") (class "Default")
      (node (ref "FB506") (pin "1") (pinfunction "1_1") (pintype "unspecified"))
      (node (ref "R103B") (pin "1") (pinfunction "1_1") (pintype "input"))
      (node (ref "U103") (pin "9") (pinfunction "A7_9") (pintype "unspecified"))
      (node (ref "U202") (pin "10") (pinfunction "I_10") (pintype "unspecified"))
      (node (ref "U203") (pin "9") (pinfunction "I_9") (pintype "unspecified"))
      (node (ref "U205") (pin "7") (pinfunction "I_7") (pintype "unspecified"))
      (node (ref "U207") (pin "7") (pinfunction "I_7") (pintype "unspecified"))
      (node (ref "U304") (pin "4") (pinfunction "I_4") (pintype "unspecified"))
      (node (ref "U305") (pin "5") (pinfunction "I_5") (pintype "unspecified"))
    )
    (net (code "180") (name "PLD_SCSI") (class "Default")
      (node (ref "U203") (pin "26") (pinfunction "IOQ_26") (pintype "unspecified"))
      (node (ref "U304") (pin "3") (pinfunction "I_3") (pintype "unspecified"))
      (node (ref "U306") (pin "7") (pinfunction "I_7") (pintype "unspecified"))
    )
    (net (code "181") (name "PLD_SID") (class "Default")
      (node (ref "U203") (pin "17") (pinfunction "IOQ_17") (pintype "unspecified"))
      (node (ref "U205") (pin "19") (pinfunction "IOQ_19") (pintype "unspecified"))
      (node (ref "U213") (pin "1") (pinfunction "OE1#_1") (pintype "unspecified"))
      (node (ref "U213") (pin "19") (pinfunction "OE2#_19") (pintype "unspecified"))
    )
    (net (code "182") (name "PLD_SIZ0") (class "Default")
      (node (ref "R300E") (pin "1") (pinfunction "1_1") (pintype "input"))
      (node (ref "U300") (pin "27") (pinfunction "SIZ0_27") (pintype "unspecified"))
      (node (ref "U304") (pin "24") (pinfunction "IOQ_24") (pintype "unspecified"))
      (node (ref "U305") (pin "7") (pinfunction "I_7") (pintype "unspecified"))
    )
    (net (code "183") (name "PLD_SIZ1") (class "Default")
      (node (ref "R300F") (pin "1") (pinfunction "1_1") (pintype "input"))
      (node (ref "U300") (pin "26") (pinfunction "SIZ1_26") (pintype "unspecified"))
      (node (ref "U304") (pin "25") (pinfunction "IOQ_25") (pintype "unspecified"))
      (node (ref "U305") (pin "6") (pinfunction "I_6") (pintype "unspecified"))
    )
    (net (code "184") (name "ROM_A15") (class "Default")
      (node (ref "J100") (pin "2") (pinfunction "2_2") (pintype "input"))
      (node (ref "U206") (pin "1") (pinfunction "VPP_1") (pintype "input"))
    )
    (net (code "185") (name "ROM_OE") (class "Default")
      (node (ref "U203") (pin "25") (pinfunction "IOQ_25") (pintype "unspecified"))
      (node (ref "U206") (pin "22") (pinfunction "OE#_22") (pintype "passive"))
      (node (ref "U207") (pin "19") (pinfunction "IOQ_19") (pintype "unspecified"))
    )
    (net (code "186") (name "SBG") (class "Default")
      (node (ref "U300") (pin "100") (pinfunction "BG/_100") (pintype "unspecified"))
      (node (ref "U303") (pin "21") (pinfunction "IOQ_21") (pintype "unspecified"))
    )
    (net (code "187") (name "SBR") (class "Default")
      (node (ref "FB503") (pin "2") (pinfunction "2_2") (pintype "unspecified"))
      (node (ref "U303") (pin "4") (pinfunction "I_4") (pintype "unspecified"))
    )
    (net (code "188") (name "SCDAT0") (class "Default")
      (node (ref "FB310K") (pin "1") (pinfunction "1_1") (pintype "unspecified"))
      (node (ref "FB311A") (pin "2") (pinfunction "2_2") (pintype "unspecified"))
      (node (ref "RP300B") (pin "5") (pinfunction "R4_5") (pintype "unspecified"))
      (node (ref "U300") (pin "131") (pinfunction "SD0/_131") (pintype "unspecified"))
      (node (ref "U311") (pin "3") (pinfunction "R2_3") (pintype "unspecified"))
    )
    (net (code "189") (name "SCDAT1") (class "Default")
      (node (ref "FB310L") (pin "1") (pinfunction "1_1") (pintype "unspecified"))
      (node (ref "FB311B") (pin "2") (pinfunction "2_2") (pintype "unspecified"))
      (node (ref "RP300B") (pin "6") (pinfunction "R5_6") (pintype "unspecified"))
      (node (ref "U300") (pin "130") (pinfunction "SD1/_130") (pintype "unspecified"))
      (node (ref "U311") (pin "4") (pinfunction "R3_4") (pintype "unspecified"))
    )
    (net (code "190") (name "SCDAT2") (class "Default")
      (node (ref "FB310M") (pin "1") (pinfunction "1_1") (pintype "unspecified"))
      (node (ref "FB311C") (pin "2") (pinfunction "2_2") (pintype "unspecified"))
      (node (ref "RP300B") (pin "7") (pinfunction "R6_7") (pintype "unspecified"))
      (node (ref "U300") (pin "129") (pinfunction "SD2/_129") (pintype "unspecified"))
      (node (ref "U311") (pin "5") (pinfunction "R4_5") (pintype "unspecified"))
    )
    (net (code "191") (name "SCDAT3") (class "Default")
      (node (ref "FB310N") (pin "1") (pinfunction "1_1") (pintype "unspecified"))
      (node (ref "FB311D") (pin "2") (pinfunction "2_2") (pintype "unspecified"))
      (node (ref "RP300A") (pin "7") (pinfunction "R6_7") (pintype "unspecified"))
      (node (ref "U300") (pin "127") (pinfunction "SD3/_127") (pintype "unspecified"))
      (node (ref "U311") (pin "6") (pinfunction "R5_6") (pintype "unspecified"))
    )
    (net (code "192") (name "SCDAT4") (class "Default")
      (node (ref "FB310O") (pin "1") (pinfunction "1_1") (pintype "unspecified"))
      (node (ref "FB311E") (pin "2") (pinfunction "2_2") (pintype "unspecified"))
      (node (ref "RP300A") (pin "6") (pinfunction "R5_6") (pintype "unspecified"))
      (node (ref "U300") (pin "126") (pinfunction "SD4/_126") (pintype "unspecified"))
      (node (ref "U310") (pin "5") (pinfunction "R4_5") (pintype "unspecified"))
    )
    (net (code "193") (name "SCDAT5") (class "Default")
      (node (ref "FB310P") (pin "1") (pinfunction "1_1") (pintype "unspecified"))
      (node (ref "FB311F") (pin "2") (pinfunction "2_2") (pintype "unspecified"))
      (node (ref "RP300A") (pin "5") (pinfunction "R4_5") (pintype "unspecified"))
      (node (ref "U300") (pin "125") (pinfunction "SD5/_125") (pintype "unspecified"))
      (node (ref "U311") (pin "10") (pinfunction "R6_10") (pintype "unspecified"))
    )
    (net (code "194") (name "SCDAT6") (class "Default")
      (node (ref "FB310Q") (pin "1") (pinfunction "1_1") (pintype "unspecified"))
      (node (ref "FB311G") (pin "2") (pinfunction "2_2") (pintype "unspecified"))
      (node (ref "RP300A") (pin "4") (pinfunction "R3_4") (pintype "unspecified"))
      (node (ref "U300") (pin "124") (pinfunction "SD6/_124") (pintype "unspecified"))
      (node (ref "U311") (pin "11") (pinfunction "R7_11") (pintype "unspecified"))
    )
    (net (code "195") (name "SCDAT7") (class "Default")
      (node (ref "FB310R") (pin "1") (pinfunction "1_1") (pintype "unspecified"))
      (node (ref "FB311H") (pin "2") (pinfunction "2_2") (pintype "unspecified"))
      (node (ref "RP300A") (pin "3") (pinfunction "R2_3") (pintype "unspecified"))
      (node (ref "U300") (pin "122") (pinfunction "SD7/_122") (pintype "unspecified"))
      (node (ref "U311") (pin "12") (pinfunction "R8_12") (pintype "unspecified"))
    )
    (net (code "196") (name "SCDATP") (class "Default")
      (node (ref "FB310J") (pin "1") (pinfunction "1_1") (pintype "unspecified"))
      (node (ref "FB311I") (pin "2") (pinfunction "2_2") (pintype "unspecified"))
      (node (ref "RP300A") (pin "2") (pinfunction "R1_2") (pintype "unspecified"))
      (node (ref "U300") (pin "121") (pinfunction "SDP/_121") (pintype "unspecified"))
      (node (ref "U311") (pin "13") (pinfunction "R9_13") (pintype "unspecified"))
    )
    (net (code "197") (name "SCSI_BUSY") (class "Default")
      (node (ref "CN309") (pin "36") (pinfunction "36_36") (pintype "input"))
      (node (ref "FB311R") (pin "1") (pinfunction "1_1") (pintype "unspecified"))
      (node (ref "U307") (pin "1") (pinfunction "1A_1") (pintype "unspecified"))
      (node (ref "U307") (pin "3") (pinfunction "2A_3") (pintype "unspecified"))
    )
    (net (code "198") (name "SCSI_TERMPWR") (class "Default")
      (node (ref "CN309") (pin "26") (pinfunction "26_26") (pintype "input"))
      (node (ref "CN310") (pin "38") (pinfunction "38_38") (pintype "unspecified"))
      (node (ref "F309A") (pin "2") (pinfunction "2_2") (pintype "unspecified"))
      (node (ref "F309B") (pin "2") (pinfunction "2_2") (pintype "unspecified"))
      (node (ref "U310") (pin "1") (pinfunction "TPWR1_1") (pintype "passive"))
      (node (ref "U310") (pin "9") (pinfunction "TPWR2_9") (pintype "passive"))
      (node (ref "U311") (pin "1") (pinfunction "TPWR1_1") (pintype "passive"))
      (node (ref "U311") (pin "9") (pinfunction "TPWR2_9") (pintype "passive"))
    )
    (net (code "199") (name "SCTRL_ACK") (class "Default")
      (node (ref "FB310G") (pin "1") (pinfunction "1_1") (pintype "unspecified"))
      (node (ref "FB311Q") (pin "2") (pinfunction "2_2") (pintype "unspecified"))
      (node (ref "RP300C") (pin "7") (pinfunction "R6_7") (pintype "unspecified"))
      (node (ref "U300") (pin "117") (pinfunction "ACK/_117") (pintype "unspecified"))
      (node (ref "U310") (pin "10") (pinfunction "R6_10") (pintype "unspecified"))
    )
    (net (code "200") (name "SCTRL_ATN") (class "Default")
      (node (ref "FB310I") (pin "1") (pinfunction "1_1") (pintype "unspecified"))
      (node (ref "FB311J") (pin "2") (pinfunction "2_2") (pintype "unspecified"))
      (node (ref "RP300C") (pin "6") (pinfunction "R5_6") (pintype "unspecified"))
      (node (ref "U300") (pin "120") (pinfunction "ATN/_120") (pintype "unspecified"))
      (node (ref "U310") (pin "6") (pinfunction "R5_6") (pintype "unspecified"))
    )
    (net (code "201") (name "SCTRL_BSY") (class "Default")
      (node (ref "FB310H") (pin "1") (pinfunction "1_1") (pintype "unspecified"))
      (node (ref "FB311R") (pin "2") (pinfunction "2_2") (pintype "unspecified"))
      (node (ref "RP300C") (pin "3") (pinfunction "R2_3") (pintype "unspecified"))
      (node (ref "U300") (pin "119") (pinfunction "BSY/_119") (pintype "unspecified"))
      (node (ref "U310") (pin "2") (pinfunction "R1_2") (pintype "unspecified"))
    )
    (net (code "202") (name "SCTRL_CD") (class "Default")
      (node (ref "FB310C") (pin "1") (pinfunction "1_1") (pintype "unspecified"))
      (node (ref "FB311M") (pin "2") (pinfunction "2_2") (pintype "unspecified"))
      (node (ref "RP300B") (pin "2") (pinfunction "R1_2") (pintype "unspecified"))
      (node (ref "U300") (pin "112") (pinfunction "C/D_112") (pintype "unspecified"))
      (node (ref "U311") (pin "2") (pinfunction "R1_2") (pintype "unspecified"))
    )
    (net (code "203") (name "SCTRL_IO") (class "Default")
      (node (ref "FB310A") (pin "1") (pinfunction "1_1") (pintype "unspecified"))
      (node (ref "FB311K") (pin "2") (pinfunction "2_2") (pintype "unspecified"))
      (node (ref "RP300B") (pin "3") (pinfunction "R2_3") (pintype "unspecified"))
      (node (ref "U300") (pin "110") (pinfunction "I/O_110") (pintype "unspecified"))
      (node (ref "U310") (pin "13") (pinfunction "R9_13") (pintype "unspecified"))
    )
    (net (code "204") (name "SCTRL_MSG") (class "Default")
      (node (ref "FB310E") (pin "1") (pinfunction "1_1") (pintype "unspecified"))
      (node (ref "FB311O") (pin "2") (pinfunction "2_2") (pintype "unspecified"))
      (node (ref "RP300B") (pin "4") (pinfunction "R3_4") (pintype "unspecified"))
      (node (ref "U300") (pin "115") (pinfunction "MSG/_115") (pintype "unspecified"))
      (node (ref "U310") (pin "12") (pinfunction "R8_12") (pintype "unspecified"))
    )
    (net (code "205") (name "SCTRL_REQ") (class "Default")
      (node (ref "FB310B") (pin "1") (pinfunction "1_1") (pintype "unspecified"))
      (node (ref "FB311L") (pin "2") (pinfunction "2_2") (pintype "unspecified"))
      (node (ref "RP300C") (pin "2") (pinfunction "R1_2") (pintype "unspecified"))
      (node (ref "U300") (pin "111") (pinfunction "REQ/_111") (pintype "unspecified"))
      (node (ref "U310") (pin "11") (pinfunction "R7_11") (pintype "unspecified"))
    )
    (net (code "206") (name "SCTRL_RST") (class "Default")
      (node (ref "FB310F") (pin "1") (pinfunction "1_1") (pintype "unspecified"))
      (node (ref "FB311P") (pin "2") (pinfunction "2_2") (pintype "unspecified"))
      (node (ref "RP300C") (pin "5") (pinfunction "R4_5") (pintype "unspecified"))
      (node (ref "U300") (pin "116") (pinfunction "RST/_116") (pintype "unspecified"))
      (node (ref "U310") (pin "4") (pinfunction "R3_4") (pintype "unspecified"))
    )
    (net (code "207") (name "SCTRL_SEL") (class "Default")
      (node (ref "FB310D") (pin "1") (pinfunction "1_1") (pintype "unspecified"))
      (node (ref "FB311N") (pin "2") (pinfunction "2_2") (pintype "unspecified"))
      (node (ref "RP300C") (pin "4") (pinfunction "R3_4") (pintype "unspecified"))
      (node (ref "U300") (pin "114") (pinfunction "SEL/_114") (pintype "unspecified"))
      (node (ref "U310") (pin "3") (pinfunction "R2_3") (pintype "unspecified"))
    )
    (net (code "208") (name "SLACK") (class "Default")
      (node (ref "U205") (pin "9") (pinfunction "I_9") (pintype "unspecified"))
      (node (ref "U300") (pin "92") (pinfunction "SLACK/_92") (pintype "unspecified"))
    )
    (net (code "209") (name "SREG") (class "Default")
      (node (ref "U300") (pin "93") (pinfunction "CS/_93") (pintype "unspecified"))
      (node (ref "U304") (pin "19") (pinfunction "IOQ_19") (pintype "unspecified"))
    )
    (net (code "210") (name "STERM") (class "Default")
      (node (ref "R300D") (pin "2") (pinfunction "2_2") (pintype "input"))
      (node (ref "U300") (pin "36") (pinfunction "STERM/-TA/_36") (pintype "unspecified"))
      (node (ref "U304") (pin "12") (pinfunction "I_12") (pintype "unspecified"))
      (node (ref "U306") (pin "19") (pinfunction "IOQ_19") (pintype "unspecified"))
    )
    (net (code "211") (name "T_GND") (class "Default")
      (node (ref "C400A") (pin "2") (pinfunction "2_2") (pintype "unspecified"))
      (node (ref "C400B") (pin "1") (pinfunction "1_1") (pintype "input"))
      (node (ref "C401A") (pin "2") (pinfunction "2_2") (pintype "unspecified"))
      (node (ref "C401B") (pin "1") (pinfunction "1_1") (pintype "input"))
      (node (ref "C402") (pin "1") (pinfunction "1_1") (pintype "input"))
      (node (ref "C403") (pin "2") (pinfunction "2_2") (pintype "unspecified"))
      (node (ref "CN400") (pin "1") (pinfunction "1_1") (pintype "unspecified"))
      (node (ref "CN400") (pin "11") (pinfunction "11_11") (pintype "unspecified"))
      (node (ref "CN400") (pin "13") (pinfunction "13_13") (pintype "unspecified"))
      (node (ref "CN400") (pin "15") (pinfunction "15_15") (pintype "unspecified"))
      (node (ref "CN400") (pin "17") (pinfunction "17_17") (pintype "unspecified"))
      (node (ref "CN400") (pin "19") (pinfunction "19_19") (pintype "unspecified"))
      (node (ref "CN400") (pin "20") (pinfunction "20_20") (pintype "unspecified"))
      (node (ref "CN400") (pin "21") (pinfunction "21_21") (pintype "unspecified"))
      (node (ref "CN400") (pin "22") (pinfunction "22_22") (pintype "unspecified"))
      (node (ref "CN400") (pin "23") (pinfunction "23_23") (pintype "unspecified"))
      (node (ref "CN400") (pin "24") (pinfunction "24_24") (pintype "unspecified"))
      (node (ref "CN400") (pin "27") (pinfunction "27_27") (pintype "unspecified"))
      (node (ref "CN400") (pin "28") (pinfunction "28_28") (pintype "unspecified"))
      (node (ref "CN400") (pin "29") (pinfunction "29_29") (pintype "unspecified"))
      (node (ref "CN400") (pin "3") (pinfunction "3_3") (pintype "unspecified"))
      (node (ref "CN400") (pin "30") (pinfunction "30_30") (pintype "unspecified"))
      (node (ref "CN400") (pin "31") (pinfunction "31_31") (pintype "unspecified"))
      (node (ref "CN400") (pin "33") (pinfunction "33_33") (pintype "unspecified"))
      (node (ref "CN400") (pin "34") (pinfunction "34_34") (pintype "unspecified"))
      (node (ref "CN400") (pin "35") (pinfunction "35_35") (pintype "unspecified"))
      (node (ref "CN400") (pin "37") (pinfunction "37_37") (pintype "unspecified"))
      (node (ref "CN400") (pin "39") (pinfunction "39_39") (pintype "unspecified"))
      (node (ref "CN400") (pin "41") (pinfunction "41_41") (pintype "unspecified"))
      (node (ref "CN400") (pin "43") (pinfunction "43_43") (pintype "unspecified"))
      (node (ref "CN400") (pin "45") (pinfunction "45_45") (pintype "unspecified"))
      (node (ref "CN400") (pin "47") (pinfunction "47_47") (pintype "unspecified"))
      (node (ref "CN400") (pin "49") (pinfunction "49_49") (pintype "unspecified"))
      (node (ref "CN400") (pin "5") (pinfunction "5_5") (pintype "unspecified"))
      (node (ref "CN400") (pin "7") (pinfunction "7_7") (pintype "unspecified"))
      (node (ref "CN400") (pin "9") (pinfunction "9_9") (pintype "unspecified"))
      (node (ref "U400") (pin "8") (pinfunction "GND_8") (pintype "passive"))
      (node (ref "U401") (pin "8") (pinfunction "GND_8") (pintype "passive"))
    )
    (net (code "212") (name "T_SCDAT0") (class "Default")
      (node (ref "CN400") (pin "2") (pinfunction "2_2") (pintype "unspecified"))
      (node (ref "U401") (pin "13") (pinfunction "R9_13") (pintype "unspecified"))
    )
    (net (code "213") (name "T_SCDAT1") (class "Default")
      (node (ref "CN400") (pin "4") (pinfunction "4_4") (pintype "unspecified"))
      (node (ref "U401") (pin "12") (pinfunction "R8_12") (pintype "unspecified"))
    )
    (net (code "214") (name "T_SCDAT2") (class "Default")
      (node (ref "CN400") (pin "6") (pinfunction "6_6") (pintype "unspecified"))
      (node (ref "U401") (pin "11") (pinfunction "R7_11") (pintype "unspecified"))
    )
    (net (code "215") (name "T_SCDAT3") (class "Default")
      (node (ref "CN400") (pin "8") (pinfunction "8_8") (pintype "unspecified"))
      (node (ref "U401") (pin "10") (pinfunction "R6_10") (pintype "unspecified"))
    )
    (net (code "216") (name "T_SCDAT4") (class "Default")
      (node (ref "CN400") (pin "10") (pinfunction "10_10") (pintype "unspecified"))
      (node (ref "U401") (pin "6") (pinfunction "R5_6") (pintype "unspecified"))
    )
    (net (code "217") (name "T_SCDAT5") (class "Default")
      (node (ref "CN400") (pin "12") (pinfunction "12_12") (pintype "unspecified"))
      (node (ref "U401") (pin "5") (pinfunction "R4_5") (pintype "unspecified"))
    )
    (net (code "218") (name "T_SCDAT6") (class "Default")
      (node (ref "CN400") (pin "14") (pinfunction "14_14") (pintype "unspecified"))
      (node (ref "U401") (pin "4") (pinfunction "R3_4") (pintype "unspecified"))
    )
    (net (code "219") (name "T_SCDAT7") (class "Default")
      (node (ref "CN400") (pin "16") (pinfunction "16_16") (pintype "unspecified"))
      (node (ref "U401") (pin "3") (pinfunction "R2_3") (pintype "unspecified"))
    )
    (net (code "220") (name "T_SCDATP") (class "Default")
      (node (ref "CN400") (pin "18") (pinfunction "18_18") (pintype "unspecified"))
      (node (ref "U401") (pin "2") (pinfunction "R1_2") (pintype "unspecified"))
    )
    (net (code "221") (name "T_SCSI_TERMPWR") (class "Default")
      (node (ref "C402") (pin "2") (pinfunction "2_2") (pintype "input"))
      (node (ref "C403") (pin "1") (pinfunction "1_1") (pintype "unspecified"))
      (node (ref "CN400") (pin "26") (pinfunction "26_26") (pintype "unspecified"))
      (node (ref "U400") (pin "1") (pinfunction "TPWR1_1") (pintype "passive"))
      (node (ref "U400") (pin "9") (pinfunction "TPWR2_9") (pintype "passive"))
      (node (ref "U401") (pin "1") (pinfunction "TPWR1_1") (pintype "passive"))
      (node (ref "U401") (pin "9") (pinfunction "TPWR2_9") (pintype "passive"))
    )
    (net (code "222") (name "T_SCTRL_ACK") (class "Default")
      (node (ref "CN400") (pin "38") (pinfunction "38_38") (pintype "unspecified"))
      (node (ref "U400") (pin "11") (pinfunction "R7_11") (pintype "unspecified"))
    )
    (net (code "223") (name "T_SCTRL_ATN") (class "Default")
      (node (ref "CN400") (pin "32") (pinfunction "32_32") (pintype "unspecified"))
      (node (ref "U400") (pin "13") (pinfunction "R9_13") (pintype "unspecified"))
    )
    (net (code "224") (name "T_SCTRL_BSY") (class "Default")
      (node (ref "CN400") (pin "36") (pinfunction "36_36") (pintype "unspecified"))
      (node (ref "U400") (pin "12") (pinfunction "R8_12") (pintype "unspecified"))
    )
    (net (code "225") (name "T_SCTRL_CD") (class "Default")
      (node (ref "CN400") (pin "46") (pinfunction "46_46") (pintype "unspecified"))
      (node (ref "U400") (pin "4") (pinfunction "R3_4") (pintype "unspecified"))
    )
    (net (code "226") (name "T_SCTRL_IO") (class "Default")
      (node (ref "CN400") (pin "50") (pinfunction "50_50") (pintype "unspecified"))
      (node (ref "U400") (pin "2") (pinfunction "R1_2") (pintype "unspecified"))
    )
    (net (code "227") (name "T_SCTRL_MSG") (class "Default")
      (node (ref "CN400") (pin "42") (pinfunction "42_42") (pintype "unspecified"))
      (node (ref "U400") (pin "6") (pinfunction "R5_6") (pintype "unspecified"))
    )
    (net (code "228") (name "T_SCTRL_REQ") (class "Default")
      (node (ref "CN400") (pin "48") (pinfunction "48_48") (pintype "unspecified"))
      (node (ref "U400") (pin "3") (pinfunction "R2_3") (pintype "unspecified"))
    )
    (net (code "229") (name "T_SCTRL_RST") (class "Default")
      (node (ref "CN400") (pin "40") (pinfunction "40_40") (pintype "unspecified"))
      (node (ref "U400") (pin "10") (pinfunction "R6_10") (pintype "unspecified"))
    )
    (net (code "230") (name "T_SCTRL_SEL") (class "Default")
      (node (ref "CN400") (pin "44") (pinfunction "44_44") (pintype "unspecified"))
      (node (ref "U400") (pin "5") (pinfunction "R4_5") (pintype "unspecified"))
    )
    (net (code "231") (name "V5") (class "Default")
      (node (ref "C1") (pin "05") (pinfunction "+5V_05") (pintype "bidirectional"))
      (node (ref "C1") (pin "06") (pinfunction "+5V_06") (pintype "bidirectional"))
      (node (ref "C10") (pin "1") (pinfunction "1_1") (pintype "input"))
      (node (ref "C100A") (pin "1") (pinfunction "1_1") (pintype "input"))
      (node (ref "C101A") (pin "1") (pinfunction "1_1") (pintype "input"))
      (node (ref "C102A") (pin "1") (pinfunction "1_1") (pintype "input"))
      (node (ref "C103A") (pin "1") (pinfunction "1_1") (pintype "input"))
      (node (ref "C105A") (pin "1") (pinfunction "1_1") (pintype "input"))
      (node (ref "C106A") (pin "2") (pinfunction "2_2") (pintype "input"))
      (node (ref "C107A") (pin "1") (pinfunction "1_1") (pintype "input"))
      (node (ref "C108A") (pin "1") (pinfunction "1_1") (pintype "input"))
      (node (ref "C109A") (pin "1") (pinfunction "1_1") (pintype "input"))
      (node (ref "C11") (pin "1") (pinfunction "1_1") (pintype "input"))
      (node (ref "C12") (pin "1") (pinfunction "1_1") (pintype "input"))
      (node (ref "C13") (pin "1") (pinfunction "1_1") (pintype "input"))
      (node (ref "C1A") (pin "2") (pinfunction "2_2") (pintype "input"))
      (node (ref "C1B") (pin "1") (pinfunction "1_1") (pintype "input"))
      (node (ref "C200A") (pin "2") (pinfunction "2_2") (pintype "input"))
      (node (ref "C201A") (pin "1") (pinfunction "1_1") (pintype "input"))
      (node (ref "C202A") (pin "1") (pinfunction "1_1") (pintype "input"))
      (node (ref "C203A") (pin "1") (pinfunction "1_1") (pintype "input"))
      (node (ref "C204A") (pin "2") (pinfunction "2_2") (pintype "input"))
      (node (ref "C205A") (pin "1") (pinfunction "1_1") (pintype "input"))
      (node (ref "C206A") (pin "2") (pinfunction "2_2") (pintype "input"))
      (node (ref "C207A") (pin "1") (pinfunction "1_1") (pintype "input"))
      (node (ref "C212A") (pin "1") (pinfunction "1_1") (pintype "input"))
      (node (ref "C300A") (pin "1") (pinfunction "1_1") (pintype "input"))
      (node (ref "C300B") (pin "1") (pinfunction "1_1") (pintype "input"))
      (node (ref "C300C") (pin "1") (pinfunction "1_1") (pintype "input"))
      (node (ref "C300D") (pin "2") (pinfunction "2_2") (pintype "input"))
      (node (ref "C300E") (pin "1") (pinfunction "1_1") (pintype "input"))
      (node (ref "C300F") (pin "1") (pinfunction "1_1") (pintype "input"))
      (node (ref "C300G") (pin "1") (pinfunction "1_1") (pintype "input"))
      (node (ref "C300H") (pin "2") (pinfunction "2_2") (pintype "input"))
      (node (ref "C300I") (pin "1") (pinfunction "1_1") (pintype "input"))
      (node (ref "C301A") (pin "2") (pinfunction "2_2") (pintype "input"))
      (node (ref "C302A") (pin "1") (pinfunction "1_1") (pintype "input"))
      (node (ref "C303A") (pin "2") (pinfunction "2_2") (pintype "input"))
      (node (ref "C304A") (pin "1") (pinfunction "1_1") (pintype "input"))
      (node (ref "C305A") (pin "1") (pinfunction "1_1") (pintype "input"))
      (node (ref "C306A") (pin "1") (pinfunction "1_1") (pintype "input"))
      (node (ref "C307A") (pin "2") (pinfunction "2_2") (pintype "input"))
      (node (ref "CN2") (pin "4") (pinfunction "4_4") (pintype "unspecified"))
      (node (ref "CN308") (pin "2") (pinfunction "2_2") (pintype "input"))
      (node (ref "CN351") (pin "2") (pinfunction "2_2") (pintype "input"))
      (node (ref "D309A") (pin "2") (pinfunction "A_2") (pintype "unspecified"))
      (node (ref "J100") (pin "1") (pinfunction "1_1") (pintype "input"))
      (node (ref "R100A") (pin "2") (pinfunction "2_2") (pintype "input"))
      (node (ref "R103A") (pin "2") (pinfunction "2_2") (pintype "input"))
      (node (ref "R103B") (pin "2") (pinfunction "2_2") (pintype "input"))
      (node (ref "R109A") (pin "2") (pinfunction "2_2") (pintype "input"))
      (node (ref "R109B") (pin "2") (pinfunction "2_2") (pintype "input"))
      (node (ref "R109C") (pin "2") (pinfunction "2_2") (pintype "input"))
      (node (ref "R109D") (pin "2") (pinfunction "2_2") (pintype "input"))
      (node (ref "R109E") (pin "2") (pinfunction "2_2") (pintype "input"))
      (node (ref "R109F") (pin "2") (pinfunction "2_2") (pintype "input"))
      (node (ref "R109G") (pin "2") (pinfunction "2_2") (pintype "input"))
      (node (ref "R200A") (pin "2") (pinfunction "2_2") (pintype "input"))
      (node (ref "R200B") (pin "2") (pinfunction "2_2") (pintype "input"))
      (node (ref "R200C") (pin "2") (pinfunction "2_2") (pintype "input"))
      (node (ref "R200D") (pin "2") (pinfunction "2_2") (pintype "input"))
      (node (ref "R200E") (pin "2") (pinfunction "2_2") (pintype "input"))
      (node (ref "R200F") (pin "2") (pinfunction "2_2") (pintype "input"))
      (node (ref "R200G") (pin "2") (pinfunction "2_2") (pintype "input"))
      (node (ref "R200H") (pin "2") (pinfunction "2_2") (pintype "input"))
      (node (ref "R212A") (pin "1") (pinfunction "1_1") (pintype "input"))
      (node (ref "R212B") (pin "2") (pinfunction "2_2") (pintype "input"))
      (node (ref "R212C") (pin "2") (pinfunction "2_2") (pintype "input"))
      (node (ref "R212D") (pin "2") (pinfunction "2_2") (pintype "input"))
      (node (ref "R212E") (pin "1") (pinfunction "1_1") (pintype "input"))
      (node (ref "R212F") (pin "1") (pinfunction "1_1") (pintype "input"))
      (node (ref "R212G") (pin "1") (pinfunction "1_1") (pintype "input"))
      (node (ref "R212H") (pin "1") (pinfunction "1_1") (pintype "input"))
      (node (ref "R300A") (pin "2") (pinfunction "2_2") (pintype "input"))
      (node (ref "R300B") (pin "1") (pinfunction "1_1") (pintype "input"))
      (node (ref "R300C") (pin "2") (pinfunction "2_2") (pintype "input"))
      (node (ref "R300D") (pin "1") (pinfunction "1_1") (pintype "input"))
      (node (ref "R300E") (pin "2") (pinfunction "2_2") (pintype "input"))
      (node (ref "R300F") (pin "2") (pinfunction "2_2") (pintype "input"))
      (node (ref "R300G") (pin "2") (pinfunction "2_2") (pintype "input"))
      (node (ref "R300H") (pin "2") (pinfunction "2_2") (pintype "input"))
      (node (ref "R300I") (pin "2") (pinfunction "2_2") (pintype "input"))
      (node (ref "R300J") (pin "2") (pinfunction "2_2") (pintype "input"))
      (node (ref "R300K") (pin "2") (pinfunction "2_2") (pintype "input"))
      (node (ref "R300L") (pin "2") (pinfunction "2_2") (pintype "input"))
      (node (ref "R300M") (pin "1") (pinfunction "1_1") (pintype "input"))
      (node (ref "R300N") (pin "2") (pinfunction "2_2") (pintype "input"))
      (node (ref "R300O") (pin "2") (pinfunction "2_2") (pintype "input"))
      (node (ref "R300P") (pin "2") (pinfunction "2_2") (pintype "input"))
      (node (ref "R307A") (pin "2") (pinfunction "2_2") (pintype "input"))
      (node (ref "R307B") (pin "1") (pinfunction "1_1") (pintype "input"))
      (node (ref "RP300A") (pin "8") (pinfunction "COM2_8") (pintype "unspecified"))
      (node (ref "RP300B") (pin "8") (pinfunction "COM2_8") (pintype "unspecified"))
      (node (ref "RP300C") (pin "8") (pinfunction "COM2_8") (pintype "unspecified"))
      (node (ref "U100") (pin "24") (pinfunction "VCC_24") (pintype "passive"))
      (node (ref "U101") (pin "24") (pinfunction "VCC_24") (pintype "passive"))
      (node (ref "U102") (pin "24") (pinfunction "VCC_24") (pintype "passive"))
      (node (ref "U103") (pin "20") (pinfunction "VCC_20") (pintype "unspecified"))
      (node (ref "U105") (pin "24") (pinfunction "VCC_24") (pintype "passive"))
      (node (ref "U106") (pin "24") (pinfunction "VCC_24") (pintype "passive"))
      (node (ref "U107") (pin "24") (pinfunction "VCC_24") (pintype "passive"))
      (node (ref "U108") (pin "24") (pinfunction "VCC_24") (pintype "passive"))
      (node (ref "U109") (pin "20") (pinfunction "VCC_20") (pintype "unspecified"))
      (node (ref "U200") (pin "20") (pinfunction "VCC_20") (pintype "unspecified"))
      (node (ref "U201") (pin "20") (pinfunction "VCC_20") (pintype "unspecified"))
      (node (ref "U202") (pin "28") (pinfunction "VCC_28") (pintype "unspecified"))
      (node (ref "U203") (pin "28") (pinfunction "VCC_28") (pintype "unspecified"))
      (node (ref "U204") (pin "20") (pinfunction "VCC_20") (pintype "unspecified"))
      (node (ref "U205") (pin "28") (pinfunction "VCC_28") (pintype "unspecified"))
      (node (ref "U206") (pin "28") (pinfunction "VCC_28") (pintype "output"))
      (node (ref "U207") (pin "28") (pinfunction "VCC_28") (pintype "unspecified"))
      (node (ref "U213") (pin "20") (pinfunction "VCC_20") (pintype "unspecified"))
      (node (ref "U300") (pin "139") (pinfunction "Vdd_139") (pintype "unspecified"))
      (node (ref "U300") (pin "153") (pinfunction "Vdd_153") (pintype "unspecified"))
      (node (ref "U300") (pin "19") (pinfunction "Vdd_19") (pintype "unspecified"))
      (node (ref "U300") (pin "39") (pinfunction "Vdd_39") (pintype "unspecified"))
      (node (ref "U300") (pin "40") (pinfunction "HALT/-TIP/_40") (pintype "unspecified"))
      (node (ref "U300") (pin "49") (pinfunction "Vdd_49") (pintype "unspecified"))
      (node (ref "U300") (pin "6") (pinfunction "Vdd_6") (pintype "unspecified"))
      (node (ref "U300") (pin "64") (pinfunction "Vdd_64") (pintype "unspecified"))
      (node (ref "U300") (pin "79") (pinfunction "Vdd_79") (pintype "unspecified"))
      (node (ref "U300") (pin "90") (pinfunction "BIG_LIT/_90") (pintype "unspecified"))
      (node (ref "U300") (pin "91") (pinfunction "BS_91") (pintype "unspecified"))
      (node (ref "U300") (pin "95") (pinfunction "BOFF/_95") (pintype "unspecified"))
      (node (ref "U300") (pin "99") (pinfunction "Vdd_99") (pintype "unspecified"))
      (node (ref "U301") (pin "14") (pinfunction "Vcc_14") (pintype "unspecified"))
      (node (ref "U302") (pin "1") (pinfunction "RD0#_1") (pintype "unspecified"))
      (node (ref "U302") (pin "10") (pinfunction "SD1#_10") (pintype "unspecified"))
      (node (ref "U302") (pin "11") (pinfunction "CP1_11") (pintype "unspecified"))
      (node (ref "U302") (pin "12") (pinfunction "D1_12") (pintype "unspecified"))
      (node (ref "U302") (pin "13") (pinfunction "RD1#_13") (pintype "unspecified"))
      (node (ref "U302") (pin "14") (pinfunction "VCC_14") (pintype "unspecified"))
      (node (ref "U302") (pin "4") (pinfunction "SD0#_4") (pintype "unspecified"))
      (node (ref "U303") (pin "28") (pinfunction "VCC_28") (pintype "unspecified"))
      (node (ref "U304") (pin "28") (pinfunction "VCC_28") (pintype "unspecified"))
      (node (ref "U305") (pin "28") (pinfunction "VCC_28") (pintype "unspecified"))
      (node (ref "U306") (pin "28") (pinfunction "VCC_28") (pintype "unspecified"))
      (node (ref "U307") (pin "14") (pinfunction "VCC_14") (pintype "unspecified"))
    )
    (net (code "232") (name "V12") (class "Default")
      (node (ref "C1") (pin "10") (pinfunction "+12V_10") (pintype "bidirectional"))
      (node (ref "C1C") (pin "1") (pinfunction "1_1") (pintype "input"))
      (node (ref "CN2") (pin "1") (pinfunction "1_1") (pintype "unspecified"))
    )
    (net (code "233") (name "Z2D") (class "Default")
      (node (ref "FB504") (pin "2") (pinfunction "2_2") (pintype "unspecified"))
      (node (ref "U105") (pin "23") (pinfunction "CEBA_23") (pintype "unspecified"))
      (node (ref "U106") (pin "23") (pinfunction "CEBA_23") (pintype "unspecified"))
      (node (ref "U107") (pin "23") (pinfunction "CEBA_23") (pintype "unspecified"))
      (node (ref "U108") (pin "23") (pinfunction "CEBA_23") (pintype "unspecified"))
    )
    (net (code "234") (name "Z_7M") (class "Default")
      (node (ref "C1") (pin "92") (pinfunction "7M_Clock_92") (pintype "bidirectional"))
      (node (ref "U303") (pin "2") (pinfunction "CLK/I_2") (pintype "unspecified"))
    )
    (net (code "235") (name "Z_A2") (class "Default")
      (node (ref "C1") (pin "27") (pinfunction "A2_27") (pintype "output"))
      (node (ref "U103") (pin "13") (pinfunction "B5_13") (pintype "unspecified"))
    )
    (net (code "236") (name "Z_A3") (class "Default")
      (node (ref "C1") (pin "26") (pinfunction "A3_26") (pintype "bidirectional"))
      (node (ref "U103") (pin "14") (pinfunction "B4_14") (pintype "unspecified"))
    )
    (net (code "237") (name "Z_A4") (class "Default")
      (node (ref "C1") (pin "24") (pinfunction "A4_24") (pintype "bidirectional"))
      (node (ref "U103") (pin "15") (pinfunction "B3_15") (pintype "unspecified"))
    )
    (net (code "238") (name "Z_A5") (class "Default")
      (node (ref "C1") (pin "21") (pinfunction "A5_21") (pintype "output"))
      (node (ref "U103") (pin "16") (pinfunction "B2_16") (pintype "unspecified"))
    )
    (net (code "239") (name "Z_A6") (class "Default")
      (node (ref "C1") (pin "23") (pinfunction "A6_23") (pintype "output"))
      (node (ref "U103") (pin "17") (pinfunction "B1_17") (pintype "unspecified"))
    )
    (net (code "240") (name "Z_A7") (class "Default")
      (node (ref "C1") (pin "28") (pinfunction "A7_28") (pintype "bidirectional"))
      (node (ref "U103") (pin "18") (pinfunction "B0_18") (pintype "unspecified"))
    )
    (net (code "241") (name "Z_A8D0") (class "Default")
      (node (ref "C1") (pin "30") (pinfunction "A8+D0,A8_30") (pintype "bidirectional"))
      (node (ref "U102") (pin "15") (pinfunction "B7_15") (pintype "bidirectional"))
      (node (ref "U107") (pin "15") (pinfunction "B7_15") (pintype "bidirectional"))
    )
    (net (code "242") (name "Z_A9D1") (class "Default")
      (node (ref "C1") (pin "32") (pinfunction "A9+D1,A9_32") (pintype "bidirectional"))
      (node (ref "U102") (pin "16") (pinfunction "B6_16") (pintype "bidirectional"))
      (node (ref "U107") (pin "16") (pinfunction "B6_16") (pintype "bidirectional"))
    )
    (net (code "243") (name "Z_A10D2") (class "Default")
      (node (ref "C1") (pin "34") (pinfunction "A10+D2,A10_34") (pintype "bidirectional"))
      (node (ref "U102") (pin "17") (pinfunction "B5_17") (pintype "bidirectional"))
      (node (ref "U107") (pin "17") (pinfunction "B5_17") (pintype "bidirectional"))
    )
    (net (code "244") (name "Z_A11D3") (class "Default")
      (node (ref "C1") (pin "36") (pinfunction "A11+D3,A11_36") (pintype "bidirectional"))
      (node (ref "U102") (pin "18") (pinfunction "B4_18") (pintype "bidirectional"))
      (node (ref "U107") (pin "18") (pinfunction "B4_18") (pintype "bidirectional"))
    )
    (net (code "245") (name "Z_A12D4") (class "Default")
      (node (ref "C1") (pin "38") (pinfunction "A12+D4,A12_38") (pintype "bidirectional"))
      (node (ref "U102") (pin "19") (pinfunction "B3_19") (pintype "bidirectional"))
      (node (ref "U107") (pin "19") (pinfunction "B3_19") (pintype "bidirectional"))
    )
    (net (code "246") (name "Z_A13D5") (class "Default")
      (node (ref "C1") (pin "39") (pinfunction "A13+D5,A13_39") (pintype "unspecified"))
      (node (ref "U102") (pin "20") (pinfunction "B2_20") (pintype "bidirectional"))
      (node (ref "U107") (pin "20") (pinfunction "B2_20") (pintype "bidirectional"))
    )
    (net (code "247") (name "Z_A14D6") (class "Default")
      (node (ref "C1") (pin "41") (pinfunction "A14+D6,A14_41") (pintype "unspecified"))
      (node (ref "U102") (pin "21") (pinfunction "B1_21") (pintype "bidirectional"))
      (node (ref "U107") (pin "21") (pinfunction "B1_21") (pintype "bidirectional"))
    )
    (net (code "248") (name "Z_A15D7") (class "Default")
      (node (ref "C1") (pin "43") (pinfunction "A15+D7,A15_43") (pintype "unspecified"))
      (node (ref "U102") (pin "22") (pinfunction "B0_22") (pintype "bidirectional"))
      (node (ref "U107") (pin "22") (pinfunction "B0_22") (pintype "bidirectional"))
    )
    (net (code "249") (name "Z_A16D8") (class "Default")
      (node (ref "C1") (pin "45") (pinfunction "A16+D8,A16_45") (pintype "unspecified"))
      (node (ref "U101") (pin "15") (pinfunction "B7_15") (pintype "bidirectional"))
      (node (ref "U106") (pin "15") (pinfunction "B7_15") (pintype "bidirectional"))
    )
    (net (code "250") (name "Z_A17D9") (class "Default")
      (node (ref "C1") (pin "47") (pinfunction "A17+D9,A17_47") (pintype "unspecified"))
      (node (ref "U101") (pin "16") (pinfunction "B6_16") (pintype "bidirectional"))
      (node (ref "U106") (pin "16") (pinfunction "B6_16") (pintype "bidirectional"))
    )
    (net (code "251") (name "Z_A18D10") (class "Default")
      (node (ref "C1") (pin "52") (pinfunction "A18+D10,A18_52") (pintype "bidirectional"))
      (node (ref "U101") (pin "17") (pinfunction "B5_17") (pintype "bidirectional"))
      (node (ref "U106") (pin "17") (pinfunction "B5_17") (pintype "bidirectional"))
    )
    (net (code "252") (name "Z_A19D11") (class "Default")
      (node (ref "C1") (pin "54") (pinfunction "A19+D11,A19_54") (pintype "bidirectional"))
      (node (ref "U101") (pin "18") (pinfunction "B4_18") (pintype "bidirectional"))
      (node (ref "U106") (pin "18") (pinfunction "B4_18") (pintype "bidirectional"))
    )
    (net (code "253") (name "Z_A20D12") (class "Default")
      (node (ref "C1") (pin "56") (pinfunction "A20+D12,A20_56") (pintype "bidirectional"))
      (node (ref "U101") (pin "19") (pinfunction "B3_19") (pintype "bidirectional"))
      (node (ref "U106") (pin "19") (pinfunction "B3_19") (pintype "bidirectional"))
    )
    (net (code "254") (name "Z_A21D13") (class "Default")
      (node (ref "C1") (pin "58") (pinfunction "A21+D13,A21_58") (pintype "bidirectional"))
      (node (ref "U101") (pin "20") (pinfunction "B2_20") (pintype "bidirectional"))
      (node (ref "U106") (pin "20") (pinfunction "B2_20") (pintype "bidirectional"))
    )
    (net (code "255") (name "Z_A22D14") (class "Default")
      (node (ref "C1") (pin "57") (pinfunction "A22+D14,A22_57") (pintype "bidirectional"))
      (node (ref "U101") (pin "21") (pinfunction "B1_21") (pintype "bidirectional"))
      (node (ref "U106") (pin "21") (pinfunction "B1_21") (pintype "bidirectional"))
    )
    (net (code "256") (name "Z_A23D15") (class "Default")
      (node (ref "C1") (pin "59") (pinfunction "A23+D15,A23_59") (pintype "output"))
      (node (ref "U101") (pin "22") (pinfunction "B0_22") (pintype "bidirectional"))
      (node (ref "U106") (pin "22") (pinfunction "B0_22") (pintype "bidirectional"))
    )
    (net (code "257") (name "Z_A24D24") (class "Default")
      (node (ref "C1") (pin "80") (pinfunction "A24+D24,D8_80") (pintype "unspecified"))
      (node (ref "U100") (pin "15") (pinfunction "B7_15") (pintype "bidirectional"))
      (node (ref "U105") (pin "22") (pinfunction "B0_22") (pintype "bidirectional"))
    )
    (net (code "258") (name "Z_A25D25") (class "Default")
      (node (ref "C1") (pin "78") (pinfunction "A25+D25,D9_78") (pintype "unspecified"))
      (node (ref "U100") (pin "16") (pinfunction "B6_16") (pintype "bidirectional"))
      (node (ref "U105") (pin "21") (pinfunction "B1_21") (pintype "bidirectional"))
    )
    (net (code "259") (name "Z_A26D26") (class "Default")
      (node (ref "C1") (pin "76") (pinfunction "A26+D26,D10_76") (pintype "unspecified"))
      (node (ref "U100") (pin "17") (pinfunction "B5_17") (pintype "bidirectional"))
      (node (ref "U105") (pin "20") (pinfunction "B2_20") (pintype "bidirectional"))
    )
    (net (code "260") (name "Z_A27D27") (class "Default")
      (node (ref "C1") (pin "71") (pinfunction "A27+D27,D11_71") (pintype "unspecified"))
      (node (ref "U100") (pin "18") (pinfunction "B4_18") (pintype "bidirectional"))
      (node (ref "U105") (pin "19") (pinfunction "B3_19") (pintype "bidirectional"))
    )
    (net (code "261") (name "Z_A28D28") (class "Default")
      (node (ref "C1") (pin "69") (pinfunction "A28+D28,D12_69") (pintype "unspecified"))
      (node (ref "U100") (pin "19") (pinfunction "B3_19") (pintype "bidirectional"))
      (node (ref "U105") (pin "18") (pinfunction "B4_18") (pintype "bidirectional"))
    )
    (net (code "262") (name "Z_A29D29") (class "Default")
      (node (ref "C1") (pin "67") (pinfunction "A29+D29,D13_67") (pintype "unspecified"))
      (node (ref "U100") (pin "20") (pinfunction "B2_20") (pintype "bidirectional"))
      (node (ref "U105") (pin "17") (pinfunction "B5_17") (pintype "bidirectional"))
    )
    (net (code "263") (name "Z_A30D30") (class "Default")
      (node (ref "C1") (pin "65") (pinfunction "A30+D30,D14_65") (pintype "unspecified"))
      (node (ref "U100") (pin "21") (pinfunction "B1_21") (pintype "bidirectional"))
      (node (ref "U105") (pin "16") (pinfunction "B6_16") (pintype "bidirectional"))
    )
    (net (code "264") (name "Z_A31D31") (class "Default")
      (node (ref "C1") (pin "63") (pinfunction "A31+D31,D15_63") (pintype "bidirectional"))
      (node (ref "U100") (pin "22") (pinfunction "B0_22") (pintype "bidirectional"))
      (node (ref "U105") (pin "15") (pinfunction "B7_15") (pintype "bidirectional"))
    )
    (net (code "265") (name "Z_BERR") (class "Default")
      (node (ref "C1") (pin "46") (pinfunction "/BERR_46") (pintype "bidirectional"))
      (node (ref "U307") (pin "5") (pinfunction "3A_5") (pintype "unspecified"))
    )
    (net (code "266") (name "Z_BGn") (class "Default")
      (node (ref "C1") (pin "64") (pinfunction "/BGn_64") (pintype "bidirectional"))
      (node (ref "U303") (pin "5") (pinfunction "I_5") (pintype "unspecified"))
    )
    (net (code "267") (name "Z_BRn") (class "Default")
      (node (ref "C1") (pin "60") (pinfunction "/BRn_60") (pintype "bidirectional"))
      (node (ref "U303") (pin "25") (pinfunction "IOQ_25") (pintype "unspecified"))
    )
    (net (code "268") (name "Z_CFGIN") (class "Default")
      (node (ref "C1") (pin "12") (pinfunction "/CFGINn_12") (pintype "bidirectional"))
      (node (ref "U202") (pin "18") (pinfunction "IOQ_18") (pintype "unspecified"))
    )
    (net (code "269") (name "Z_CFGOUT") (class "Default")
      (node (ref "C1") (pin "11") (pinfunction "/CFGOUTn_11") (pintype "unspecified"))
      (node (ref "U200") (pin "1") (pinfunction "OE#_1") (pintype "unspecified"))
      (node (ref "U202") (pin "21") (pinfunction "IOQ_21") (pintype "unspecified"))
      (node (ref "U205") (pin "13") (pinfunction "I_13") (pintype "unspecified"))
      (node (ref "U207") (pin "16") (pinfunction "I_16") (pintype "unspecified"))
    )
    (net (code "270") (name "Z_CINH") (class "Default")
      (node (ref "C1") (pin "17") (pinfunction "/CINH,/OVR_17") (pintype "bidirectional"))
      (node (ref "U202") (pin "24") (pinfunction "IOQ_24") (pintype "unspecified"))
    )
    (net (code "271") (name "Z_D16") (class "Default")
      (node (ref "C1") (pin "75") (pinfunction "RSVD+D16,D0_75") (pintype "unspecified"))
      (node (ref "U108") (pin "22") (pinfunction "B0_22") (pintype "bidirectional"))
    )
    (net (code "272") (name "Z_D17") (class "Default")
      (node (ref "C1") (pin "77") (pinfunction "RSVD+D17,D1_77") (pintype "unspecified"))
      (node (ref "U108") (pin "21") (pinfunction "B1_21") (pintype "bidirectional"))
    )
    (net (code "273") (name "Z_D18") (class "Default")
      (node (ref "C1") (pin "79") (pinfunction "RSVD+D18,D2_79") (pintype "output"))
      (node (ref "U108") (pin "20") (pinfunction "B2_20") (pintype "bidirectional"))
    )
    (net (code "274") (name "Z_D19") (class "Default")
      (node (ref "C1") (pin "81") (pinfunction "RSVD+D19,D3_81") (pintype "unspecified"))
      (node (ref "U108") (pin "19") (pinfunction "B3_19") (pintype "bidirectional"))
    )
    (net (code "275") (name "Z_D20") (class "Default")
      (node (ref "C1") (pin "83") (pinfunction "RSVD+D20,D4_83") (pintype "output"))
      (node (ref "U108") (pin "18") (pinfunction "B4_18") (pintype "bidirectional"))
    )
    (net (code "276") (name "Z_D21") (class "Default")
      (node (ref "C1") (pin "86") (pinfunction "RSVD+D21,D5_86") (pintype "bidirectional"))
      (node (ref "U108") (pin "17") (pinfunction "B5_17") (pintype "bidirectional"))
    )
    (net (code "277") (name "Z_D22") (class "Default")
      (node (ref "C1") (pin "84") (pinfunction "RSVD+D22,D6_84") (pintype "output"))
      (node (ref "U108") (pin "16") (pinfunction "B6_16") (pintype "bidirectional"))
    )
    (net (code "278") (name "Z_D23") (class "Default")
      (node (ref "C1") (pin "82") (pinfunction "RSVD+D23,D7_82") (pintype "bidirectional"))
      (node (ref "U108") (pin "15") (pinfunction "B7_15") (pintype "bidirectional"))
    )
    (net (code "279") (name "Z_DOE") (class "Default")
      (node (ref "C1") (pin "93") (pinfunction "DOE_93") (pintype "unspecified"))
      (node (ref "U109") (pin "16") (pinfunction "B2_16") (pintype "unspecified"))
    )
    (net (code "280") (name "Z_DS0") (class "Default")
      (node (ref "C1") (pin "51") (pinfunction "/DS0,/VMA_51") (pintype "unspecified"))
      (node (ref "U109") (pin "11") (pinfunction "B7_11") (pintype "unspecified"))
    )
    (net (code "281") (name "Z_DS1") (class "Default")
      (node (ref "C1") (pin "98") (pinfunction "/DS1,NC_98") (pintype "bidirectional"))
      (node (ref "U109") (pin "12") (pinfunction "B6_12") (pintype "unspecified"))
    )
    (net (code "282") (name "Z_DS2") (class "Default")
      (node (ref "C1") (pin "70") (pinfunction "/DS2,/LDS_70") (pintype "unspecified"))
      (node (ref "FB508") (pin "2") (pinfunction "2_2") (pintype "unspecified"))
    )
    (net (code "283") (name "Z_DS3") (class "Default")
      (node (ref "C1") (pin "72") (pinfunction "/DS3,/UDS_72") (pintype "unspecified"))
      (node (ref "FB507") (pin "2") (pinfunction "2_2") (pintype "unspecified"))
    )
    (net (code "284") (name "Z_DTACK") (class "Default")
      (node (ref "C1") (pin "66") (pinfunction "/DTACK_66") (pintype "unspecified"))
      (node (ref "C306B") (pin "1") (pinfunction "1_1") (pintype "input"))
      (node (ref "U205") (pin "20") (pinfunction "IOQ_20") (pintype "unspecified"))
      (node (ref "U306") (pin "9") (pinfunction "I_9") (pintype "unspecified"))
    )
    (net (code "285") (name "Z_FC0") (class "Default")
      (node (ref "C1") (pin "31") (pinfunction "FC0_31") (pintype "unspecified"))
      (node (ref "U109") (pin "17") (pinfunction "B1_17") (pintype "unspecified"))
    )
    (net (code "286") (name "Z_FC1") (class "Default")
      (node (ref "C1") (pin "33") (pinfunction "FC1_33") (pintype "unspecified"))
      (node (ref "U109") (pin "18") (pinfunction "B0_18") (pintype "unspecified"))
    )
    (net (code "287") (name "Z_FC2") (class "Default")
      (node (ref "C1") (pin "35") (pinfunction "FC2_35") (pintype "unspecified"))
      (node (ref "U103") (pin "12") (pinfunction "B6_12") (pintype "unspecified"))
    )
    (net (code "288") (name "Z_FCS") (class "Default")
      (node (ref "C1") (pin "97") (pinfunction "/FCS,NC_97") (pintype "unspecified"))
      (node (ref "FB501") (pin "2") (pinfunction "2_2") (pintype "unspecified"))
      (node (ref "U305") (pin "21") (pinfunction "IOQ_21") (pintype "unspecified"))
    )
    (net (code "289") (name "Z_INT2") (class "Default")
      (node (ref "C1") (pin "19") (pinfunction "/INT2_19") (pintype "bidirectional"))
      (node (ref "U207") (pin "27") (pinfunction "IOQ_27") (pintype "unspecified"))
    )
    (net (code "290") (name "Z_IORST") (class "Default")
      (node (ref "C1") (pin "94") (pinfunction "/IORST,/BUSRST_94") (pintype "bidirectional"))
      (node (ref "U307") (pin "9") (pinfunction "4A_9") (pintype "unspecified"))
    )
    (net (code "291") (name "Z_LOCK") (class "Default")
      (node (ref "C1") (pin "29") (pinfunction "/LOCK,A1_29") (pintype "unspecified"))
      (node (ref "U203") (pin "6") (pinfunction "I_6") (pintype "unspecified"))
    )
    (net (code "292") (name "Z_MTACK") (class "Default")
      (node (ref "C1") (pin "48") (pinfunction "/MTACK,/VPA_48") (pintype "bidirectional"))
      (node (ref "U306") (pin "5") (pinfunction "I_5") (pintype "unspecified"))
    )
    (net (code "293") (name "Z_MTCR") (class "Default")
      (node (ref "C1") (pin "18") (pinfunction "/MTCR,XRDY_18") (pintype "bidirectional"))
      (node (ref "U109") (pin "15") (pinfunction "B3_15") (pintype "unspecified"))
    )
    (net (code "294") (name "Z_READ") (class "Default")
      (node (ref "C1") (pin "68") (pinfunction "READ_68") (pintype "unspecified"))
      (node (ref "U103") (pin "11") (pinfunction "B7_11") (pintype "unspecified"))
    )
    (net (code "295") (name "Z_SENSEZ3") (class "Default")
      (node (ref "C1") (pin "91") (pinfunction "SenseZ3,GND_91") (pintype "output"))
      (node (ref "R100A") (pin "1") (pinfunction "1_1") (pintype "input"))
      (node (ref "U202") (pin "20") (pinfunction "IOQ_20") (pintype "unspecified"))
    )
    (net (code "296") (name "Z_SLAVE") (class "Default")
      (node (ref "C1") (pin "09") (pinfunction "/SLAVEn_09") (pintype "bidirectional"))
      (node (ref "U202") (pin "26") (pinfunction "IOQ_26") (pintype "unspecified"))
      (node (ref "U203") (pin "20") (pinfunction "IOQ_20") (pintype "unspecified"))
      (node (ref "U205") (pin "3") (pinfunction "I_3") (pintype "unspecified"))
      (node (ref "U207") (pin "13") (pinfunction "I_13") (pintype "unspecified"))
      (node (ref "U303") (pin "7") (pinfunction "I_7") (pintype "unspecified"))
    )
    (net (code "297") (name "unconnected-(C1--5V-Pad08)") (class "Default")
      (node (ref "C1") (pin "08") (pinfunction "-5V_08") (pintype "bidirectional+no_connect"))
    )
    (net (code "298") (name "unconnected-(C1--12V-Pad20)") (class "Default")
      (node (ref "C1") (pin "20") (pinfunction "-12V_20") (pintype "unspecified+no_connect"))
    )
    (net (code "299") (name "unconnected-(C1-CDAC_Clock-Pad15)") (class "Default")
      (node (ref "C1") (pin "15") (pinfunction "CDAC_Clock_15") (pintype "unspecified+no_connect"))
    )
    (net (code "300") (name "unconnected-(C1-E_Clock-Pad50)") (class "Default")
      (node (ref "C1") (pin "50") (pinfunction "E_Clock_50") (pintype "bidirectional+no_connect"))
    )
    (net (code "301") (name "unconnected-(C1-RSVD,{slash}EINT1-Pad96)") (class "Default")
      (node (ref "C1") (pin "96") (pinfunction "RSVD,/EINT1_96") (pintype "bidirectional+no_connect"))
    )
    (net (code "302") (name "unconnected-(C1-RSVD,{slash}EINT4-Pad44)") (class "Default")
      (node (ref "C1") (pin "44") (pinfunction "RSVD,/EINT4_44") (pintype "bidirectional+no_connect"))
    )
    (net (code "303") (name "unconnected-(C1-RSVD,{slash}EINT5-Pad42)") (class "Default")
      (node (ref "C1") (pin "42") (pinfunction "RSVD,/EINT5_42") (pintype "bidirectional+no_connect"))
    )
    (net (code "304") (name "unconnected-(C1-RSVD,{slash}EINT7-Pad40)") (class "Default")
      (node (ref "C1") (pin "40") (pinfunction "RSVD,/EINT7_40") (pintype "bidirectional+no_connect"))
    )
    (net (code "305") (name "unconnected-(C1-{slash}BCLR,{slash}GBG-Pad95)") (class "Default")
      (node (ref "C1") (pin "95") (pinfunction "/BCLR,/GBG_95") (pintype "bidirectional+no_connect"))
    )
    (net (code "306") (name "unconnected-(C1-{slash}BGACK-Pad62)") (class "Default")
      (node (ref "C1") (pin "62") (pinfunction "/BGACK_62") (pintype "bidirectional+no_connect"))
    )
    (net (code "307") (name "unconnected-(C1-{slash}C1_Clock-Pad16)") (class "Default")
      (node (ref "C1") (pin "16") (pinfunction "/C1_Clock_16") (pintype "bidirectional+no_connect"))
    )
    (net (code "308") (name "unconnected-(C1-{slash}C3_Clock-Pad14)") (class "Default")
      (node (ref "C1") (pin "14") (pinfunction "/C3_Clock_14") (pintype "bidirectional+no_connect"))
    )
    (net (code "309") (name "unconnected-(C1-{slash}CCS,{slash}AS-Pad74)") (class "Default")
      (node (ref "C1") (pin "74") (pinfunction "/CCS,/AS_74") (pintype "unspecified+no_connect"))
    )
    (net (code "310") (name "unconnected-(C1-{slash}HLT-Pad55)") (class "Default")
      (node (ref "C1") (pin "55") (pinfunction "/HLT_55") (pintype "output+no_connect"))
    )
    (net (code "311") (name "unconnected-(C1-{slash}INT6-Pad22)") (class "Default")
      (node (ref "C1") (pin "22") (pinfunction "/INT6_22") (pintype "output+no_connect"))
    )
    (net (code "312") (name "unconnected-(C1-{slash}OWN-Pad07)") (class "Default")
      (node (ref "C1") (pin "07") (pinfunction "/OWN_07") (pintype "unspecified+no_connect"))
    )
    (net (code "313") (name "unconnected-(C1-{slash}RST-Pad53)") (class "Default")
      (node (ref "C1") (pin "53") (pinfunction "/RST_53") (pintype "unspecified+no_connect"))
    )
    (net (code "314") (name "unconnected-(CN309-Pad25)") (class "Default")
      (node (ref "CN309") (pin "25") (pinfunction "25_25") (pintype "input+no_connect"))
    )
    (net (code "315") (name "unconnected-(CN309-Pad34)") (class "Default")
      (node (ref "CN309") (pin "34") (pinfunction "34_34") (pintype "input+no_connect"))
    )
    (net (code "316") (name "unconnected-(CN310-Pad12)") (class "Default")
      (node (ref "CN310") (pin "12") (pinfunction "12_12") (pintype "unspecified+no_connect"))
    )
    (net (code "317") (name "unconnected-(CN310-Pad13)") (class "Default")
      (node (ref "CN310") (pin "13") (pinfunction "13_13") (pintype "unspecified+no_connect"))
    )
    (net (code "318") (name "unconnected-(CN310-Pad14)") (class "Default")
      (node (ref "CN310") (pin "14") (pinfunction "14_14") (pintype "unspecified+no_connect"))
    )
    (net (code "319") (name "unconnected-(CN310-Pad37)") (class "Default")
      (node (ref "CN310") (pin "37") (pinfunction "37_37") (pintype "unspecified+no_connect"))
    )
    (net (code "320") (name "unconnected-(CN310-Pad39)") (class "Default")
      (node (ref "CN310") (pin "39") (pinfunction "39_39") (pintype "unspecified+no_connect"))
    )
    (net (code "321") (name "unconnected-(CN400-Pad25)") (class "Default")
      (node (ref "CN400") (pin "25") (pinfunction "25_25") (pintype "unspecified+no_connect"))
    )
    (net (code "322") (name "unconnected-(U202-IOQ-Pad25)") (class "Default")
      (node (ref "U202") (pin "25") (pinfunction "IOQ_25") (pintype "unspecified+no_connect"))
    )
    (net (code "323") (name "unconnected-(U202-NC-Pad1)") (class "Default")
      (node (ref "U202") (pin "1") (pinfunction "NC_1") (pintype "unspecified+no_connect"))
    )
    (net (code "324") (name "unconnected-(U202-NC-Pad8)") (class "Default")
      (node (ref "U202") (pin "8") (pinfunction "NC_8") (pintype "unspecified+no_connect"))
    )
    (net (code "325") (name "unconnected-(U202-NC-Pad15)") (class "Default")
      (node (ref "U202") (pin "15") (pinfunction "NC_15") (pintype "unspecified+no_connect"))
    )
    (net (code "326") (name "unconnected-(U202-NC-Pad22)") (class "Default")
      (node (ref "U202") (pin "22") (pinfunction "NC_22") (pintype "unspecified+no_connect"))
    )
    (net (code "327") (name "unconnected-(U203-IOQ-Pad18)") (class "Default")
      (node (ref "U203") (pin "18") (pinfunction "IOQ_18") (pintype "unspecified+no_connect"))
    )
    (net (code "328") (name "unconnected-(U203-IOQ-Pad19)") (class "Default")
      (node (ref "U203") (pin "19") (pinfunction "IOQ_19") (pintype "unspecified+no_connect"))
    )
    (net (code "329") (name "unconnected-(U203-IOQ-Pad21)") (class "Default")
      (node (ref "U203") (pin "21") (pinfunction "IOQ_21") (pintype "unspecified+no_connect"))
    )
    (net (code "330") (name "unconnected-(U203-NC-Pad1)") (class "Default")
      (node (ref "U203") (pin "1") (pinfunction "NC_1") (pintype "unspecified+no_connect"))
    )
    (net (code "331") (name "unconnected-(U203-NC-Pad8)") (class "Default")
      (node (ref "U203") (pin "8") (pinfunction "NC_8") (pintype "unspecified+no_connect"))
    )
    (net (code "332") (name "unconnected-(U203-NC-Pad15)") (class "Default")
      (node (ref "U203") (pin "15") (pinfunction "NC_15") (pintype "unspecified+no_connect"))
    )
    (net (code "333") (name "unconnected-(U203-NC-Pad22)") (class "Default")
      (node (ref "U203") (pin "22") (pinfunction "NC_22") (pintype "unspecified+no_connect"))
    )
    (net (code "334") (name "unconnected-(U205-NC-Pad1)") (class "Default")
      (node (ref "U205") (pin "1") (pinfunction "NC_1") (pintype "unspecified+no_connect"))
    )
    (net (code "335") (name "unconnected-(U205-NC-Pad8)") (class "Default")
      (node (ref "U205") (pin "8") (pinfunction "NC_8") (pintype "unspecified+no_connect"))
    )
    (net (code "336") (name "unconnected-(U205-NC-Pad15)") (class "Default")
      (node (ref "U205") (pin "15") (pinfunction "NC_15") (pintype "unspecified+no_connect"))
    )
    (net (code "337") (name "unconnected-(U205-NC-Pad22)") (class "Default")
      (node (ref "U205") (pin "22") (pinfunction "NC_22") (pintype "unspecified+no_connect"))
    )
    (net (code "338") (name "unconnected-(U207-I-Pad3)") (class "Default")
      (node (ref "U207") (pin "3") (pinfunction "I_3") (pintype "unspecified+no_connect"))
    )
    (net (code "339") (name "unconnected-(U207-I-Pad4)") (class "Default")
      (node (ref "U207") (pin "4") (pinfunction "I_4") (pintype "unspecified+no_connect"))
    )
    (net (code "340") (name "unconnected-(U207-I-Pad5)") (class "Default")
      (node (ref "U207") (pin "5") (pinfunction "I_5") (pintype "unspecified+no_connect"))
    )
    (net (code "341") (name "unconnected-(U207-IOQ-Pad17)") (class "Default")
      (node (ref "U207") (pin "17") (pinfunction "IOQ_17") (pintype "unspecified+no_connect"))
    )
    (net (code "342") (name "unconnected-(U207-IOQ-Pad18)") (class "Default")
      (node (ref "U207") (pin "18") (pinfunction "IOQ_18") (pintype "unspecified+no_connect"))
    )
    (net (code "343") (name "unconnected-(U207-IOQ-Pad20)") (class "Default")
      (node (ref "U207") (pin "20") (pinfunction "IOQ_20") (pintype "unspecified+no_connect"))
    )
    (net (code "344") (name "unconnected-(U207-IOQ-Pad21)") (class "Default")
      (node (ref "U207") (pin "21") (pinfunction "IOQ_21") (pintype "unspecified+no_connect"))
    )
    (net (code "345") (name "unconnected-(U207-IOQ-Pad23)") (class "Default")
      (node (ref "U207") (pin "23") (pinfunction "IOQ_23") (pintype "unspecified+no_connect"))
    )
    (net (code "346") (name "unconnected-(U207-IOQ-Pad25)") (class "Default")
      (node (ref "U207") (pin "25") (pinfunction "IOQ_25") (pintype "unspecified+no_connect"))
    )
    (net (code "347") (name "unconnected-(U207-NC-Pad1)") (class "Default")
      (node (ref "U207") (pin "1") (pinfunction "NC_1") (pintype "unspecified+no_connect"))
    )
    (net (code "348") (name "unconnected-(U207-NC-Pad8)") (class "Default")
      (node (ref "U207") (pin "8") (pinfunction "NC_8") (pintype "unspecified+no_connect"))
    )
    (net (code "349") (name "unconnected-(U207-NC-Pad15)") (class "Default")
      (node (ref "U207") (pin "15") (pinfunction "NC_15") (pintype "unspecified+no_connect"))
    )
    (net (code "350") (name "unconnected-(U207-NC-Pad22)") (class "Default")
      (node (ref "U207") (pin "22") (pinfunction "NC_22") (pintype "unspecified+no_connect"))
    )
    (net (code "351") (name "unconnected-(U300-BSYDIR-Pad108)") (class "Default")
      (node (ref "U300") (pin "108") (pinfunction "BSYDIR_108") (pintype "unspecified+no_connect"))
    )
    (net (code "352") (name "unconnected-(U300-FETCH{slash}-Pad97)") (class "Default")
      (node (ref "U300") (pin "97") (pinfunction "FETCH/_97") (pintype "unspecified+no_connect"))
    )
    (net (code "353") (name "unconnected-(U300-IGS-Pad104)") (class "Default")
      (node (ref "U300") (pin "104") (pinfunction "IGS_104") (pintype "unspecified+no_connect"))
    )
    (net (code "354") (name "unconnected-(U300-RSTDIR-Pad107)") (class "Default")
      (node (ref "U300") (pin "107") (pinfunction "RSTDIR_107") (pintype "unspecified+no_connect"))
    )
    (net (code "355") (name "unconnected-(U300-SC0-Pad88)") (class "Default")
      (node (ref "U300") (pin "88") (pinfunction "SC0_88") (pintype "unspecified+no_connect"))
    )
    (net (code "356") (name "unconnected-(U300-SC1-Pad89)") (class "Default")
      (node (ref "U300") (pin "89") (pinfunction "SC1_89") (pintype "unspecified+no_connect"))
    )
    (net (code "357") (name "unconnected-(U300-SDIR0-Pad142)") (class "Default")
      (node (ref "U300") (pin "142") (pinfunction "SDIR0_142") (pintype "unspecified+no_connect"))
    )
    (net (code "358") (name "unconnected-(U300-SDIR1-Pad141)") (class "Default")
      (node (ref "U300") (pin "141") (pinfunction "SDIR1_141") (pintype "unspecified+no_connect"))
    )
    (net (code "359") (name "unconnected-(U300-SDIR2-Pad140)") (class "Default")
      (node (ref "U300") (pin "140") (pinfunction "SDIR2_140") (pintype "unspecified+no_connect"))
    )
    (net (code "360") (name "unconnected-(U300-SDIR3-Pad138)") (class "Default")
      (node (ref "U300") (pin "138") (pinfunction "SDIR3_138") (pintype "unspecified+no_connect"))
    )
    (net (code "361") (name "unconnected-(U300-SDIR4-Pad137)") (class "Default")
      (node (ref "U300") (pin "137") (pinfunction "SDIR4_137") (pintype "unspecified+no_connect"))
    )
    (net (code "362") (name "unconnected-(U300-SDIR5-Pad135)") (class "Default")
      (node (ref "U300") (pin "135") (pinfunction "SDIR5_135") (pintype "unspecified+no_connect"))
    )
    (net (code "363") (name "unconnected-(U300-SDIR6-Pad134)") (class "Default")
      (node (ref "U300") (pin "134") (pinfunction "SDIR6_134") (pintype "unspecified+no_connect"))
    )
    (net (code "364") (name "unconnected-(U300-SDIR7-Pad133)") (class "Default")
      (node (ref "U300") (pin "133") (pinfunction "SDIR7_133") (pintype "unspecified+no_connect"))
    )
    (net (code "365") (name "unconnected-(U300-SDIRP-Pad132)") (class "Default")
      (node (ref "U300") (pin "132") (pinfunction "SDIRP_132") (pintype "unspecified+no_connect"))
    )
    (net (code "366") (name "unconnected-(U300-SELDIR-Pad106)") (class "Default")
      (node (ref "U300") (pin "106") (pinfunction "SELDIR_106") (pintype "unspecified+no_connect"))
    )
    (net (code "367") (name "unconnected-(U300-TGS-Pad103)") (class "Default")
      (node (ref "U300") (pin "103") (pinfunction "TGS_103") (pintype "unspecified+no_connect"))
    )
    (net (code "368") (name "unconnected-(U300-UPS0-TT0{slash}-Pad34)") (class "Default")
      (node (ref "U300") (pin "34") (pinfunction "UPS0-TT0/_34") (pintype "unspecified+no_connect"))
    )
    (net (code "369") (name "unconnected-(U301-N.C-Pad1)") (class "Default")
      (node (ref "U301") (pin "1") (pinfunction "N.C_1") (pintype "unspecified+no_connect"))
    )
    (net (code "370") (name "unconnected-(U302-Q1#-Pad8)") (class "Default")
      (node (ref "U302") (pin "8") (pinfunction "Q1#_8") (pintype "unspecified+no_connect"))
    )
    (net (code "371") (name "unconnected-(U302-Q1-Pad9)") (class "Default")
      (node (ref "U302") (pin "9") (pinfunction "Q1_9") (pintype "unspecified+no_connect"))
    )
    (net (code "372") (name "unconnected-(U303-I-Pad13)") (class "Default")
      (node (ref "U303") (pin "13") (pinfunction "I_13") (pintype "unspecified+no_connect"))
    )
    (net (code "373") (name "unconnected-(U303-I-Pad16)") (class "Default")
      (node (ref "U303") (pin "16") (pinfunction "I_16") (pintype "unspecified+no_connect"))
    )
    (net (code "374") (name "unconnected-(U303-IOQ-Pad17)") (class "Default")
      (node (ref "U303") (pin "17") (pinfunction "IOQ_17") (pintype "unspecified+no_connect"))
    )
    (net (code "375") (name "unconnected-(U303-IOQ-Pad18)") (class "Default")
      (node (ref "U303") (pin "18") (pinfunction "IOQ_18") (pintype "unspecified+no_connect"))
    )
    (net (code "376") (name "unconnected-(U303-IOQ-Pad19)") (class "Default")
      (node (ref "U303") (pin "19") (pinfunction "IOQ_19") (pintype "unspecified+no_connect"))
    )
    (net (code "377") (name "unconnected-(U303-IOQ-Pad23)") (class "Default")
      (node (ref "U303") (pin "23") (pinfunction "IOQ_23") (pintype "unspecified+no_connect"))
    )
    (net (code "378") (name "unconnected-(U303-IOQ-Pad24)") (class "Default")
      (node (ref "U303") (pin "24") (pinfunction "IOQ_24") (pintype "unspecified+no_connect"))
    )
    (net (code "379") (name "unconnected-(U303-IOQ-Pad26)") (class "Default")
      (node (ref "U303") (pin "26") (pinfunction "IOQ_26") (pintype "unspecified+no_connect"))
    )
    (net (code "380") (name "unconnected-(U303-NC-Pad1)") (class "Default")
      (node (ref "U303") (pin "1") (pinfunction "NC_1") (pintype "unspecified+no_connect"))
    )
    (net (code "381") (name "unconnected-(U303-NC-Pad8)") (class "Default")
      (node (ref "U303") (pin "8") (pinfunction "NC_8") (pintype "unspecified+no_connect"))
    )
    (net (code "382") (name "unconnected-(U303-NC-Pad15)") (class "Default")
      (node (ref "U303") (pin "15") (pinfunction "NC_15") (pintype "unspecified+no_connect"))
    )
    (net (code "383") (name "unconnected-(U303-NC-Pad22)") (class "Default")
      (node (ref "U303") (pin "22") (pinfunction "NC_22") (pintype "unspecified+no_connect"))
    )
    (net (code "384") (name "unconnected-(U304-I-Pad16)") (class "Default")
      (node (ref "U304") (pin "16") (pinfunction "I_16") (pintype "unspecified+no_connect"))
    )
    (net (code "385") (name "unconnected-(U304-IOQ-Pad17)") (class "Default")
      (node (ref "U304") (pin "17") (pinfunction "IOQ_17") (pintype "unspecified+no_connect"))
    )
    (net (code "386") (name "unconnected-(U304-IOQ-Pad18)") (class "Default")
      (node (ref "U304") (pin "18") (pinfunction "IOQ_18") (pintype "unspecified+no_connect"))
    )
    (net (code "387") (name "unconnected-(U304-IOQ-Pad23)") (class "Default")
      (node (ref "U304") (pin "23") (pinfunction "IOQ_23") (pintype "unspecified+no_connect"))
    )
    (net (code "388") (name "unconnected-(U304-NC-Pad1)") (class "Default")
      (node (ref "U304") (pin "1") (pinfunction "NC_1") (pintype "unspecified+no_connect"))
    )
    (net (code "389") (name "unconnected-(U304-NC-Pad8)") (class "Default")
      (node (ref "U304") (pin "8") (pinfunction "NC_8") (pintype "unspecified+no_connect"))
    )
    (net (code "390") (name "unconnected-(U304-NC-Pad15)") (class "Default")
      (node (ref "U304") (pin "15") (pinfunction "NC_15") (pintype "unspecified+no_connect"))
    )
    (net (code "391") (name "unconnected-(U304-NC-Pad22)") (class "Default")
      (node (ref "U304") (pin "22") (pinfunction "NC_22") (pintype "unspecified+no_connect"))
    )
    (net (code "392") (name "unconnected-(U305-I-Pad11)") (class "Default")
      (node (ref "U305") (pin "11") (pinfunction "I_11") (pintype "unspecified+no_connect"))
    )
    (net (code "393") (name "unconnected-(U305-I-Pad12)") (class "Default")
      (node (ref "U305") (pin "12") (pinfunction "I_12") (pintype "unspecified+no_connect"))
    )
    (net (code "394") (name "unconnected-(U305-IOQ-Pad17)") (class "Default")
      (node (ref "U305") (pin "17") (pinfunction "IOQ_17") (pintype "unspecified+no_connect"))
    )
    (net (code "395") (name "unconnected-(U305-IOQ-Pad18)") (class "Default")
      (node (ref "U305") (pin "18") (pinfunction "IOQ_18") (pintype "unspecified+no_connect"))
    )
    (net (code "396") (name "unconnected-(U305-NC-Pad1)") (class "Default")
      (node (ref "U305") (pin "1") (pinfunction "NC_1") (pintype "unspecified+no_connect"))
    )
    (net (code "397") (name "unconnected-(U305-NC-Pad8)") (class "Default")
      (node (ref "U305") (pin "8") (pinfunction "NC_8") (pintype "unspecified+no_connect"))
    )
    (net (code "398") (name "unconnected-(U305-NC-Pad15)") (class "Default")
      (node (ref "U305") (pin "15") (pinfunction "NC_15") (pintype "unspecified+no_connect"))
    )
    (net (code "399") (name "unconnected-(U305-NC-Pad22)") (class "Default")
      (node (ref "U305") (pin "22") (pinfunction "NC_22") (pintype "unspecified+no_connect"))
    )
    (net (code "400") (name "unconnected-(U306-I-Pad16)") (class "Default")
      (node (ref "U306") (pin "16") (pinfunction "I_16") (pintype "unspecified+no_connect"))
    )
    (net (code "401") (name "unconnected-(U306-IOQ-Pad18)") (class "Default")
      (node (ref "U306") (pin "18") (pinfunction "IOQ_18") (pintype "unspecified+no_connect"))
    )
    (net (code "402") (name "unconnected-(U306-IOQ-Pad24)") (class "Default")
      (node (ref "U306") (pin "24") (pinfunction "IOQ_24") (pintype "unspecified+no_connect"))
    )
    (net (code "403") (name "unconnected-(U306-IOQ-Pad26)") (class "Default")
      (node (ref "U306") (pin "26") (pinfunction "IOQ_26") (pintype "unspecified+no_connect"))
    )
    (net (code "404") (name "unconnected-(U306-NC-Pad1)") (class "Default")
      (node (ref "U306") (pin "1") (pinfunction "NC_1") (pintype "unspecified+no_connect"))
    )
    (net (code "405") (name "unconnected-(U306-NC-Pad8)") (class "Default")
      (node (ref "U306") (pin "8") (pinfunction "NC_8") (pintype "unspecified+no_connect"))
    )
    (net (code "406") (name "unconnected-(U306-NC-Pad15)") (class "Default")
      (node (ref "U306") (pin "15") (pinfunction "NC_15") (pintype "unspecified+no_connect"))
    )
    (net (code "407") (name "unconnected-(U306-NC-Pad22)") (class "Default")
      (node (ref "U306") (pin "22") (pinfunction "NC_22") (pintype "unspecified+no_connect"))
    )
    (net (code "408") (name "unconnected-(U307-5Y-Pad10)") (class "Default")
      (node (ref "U307") (pin "10") (pinfunction "5Y_10") (pintype "unspecified+no_connect"))
    )
    (net (code "409") (name "unconnected-(U307-6Y-Pad12)") (class "Default")
      (node (ref "U307") (pin "12") (pinfunction "6Y_12") (pintype "unspecified+no_connect"))
    )
    (net (code "410") (name "unconnected-(U310-NC-Pad14)") (class "Default")
      (node (ref "U310") (pin "14") (pinfunction "NC_14") (pintype "unspecified+no_connect"))
    )
    (net (code "411") (name "unconnected-(U311-NC-Pad14)") (class "Default")
      (node (ref "U311") (pin "14") (pinfunction "NC_14") (pintype "unspecified+no_connect"))
    )
    (net (code "412") (name "unconnected-(U400-NC-Pad14)") (class "Default")
      (node (ref "U400") (pin "14") (pinfunction "NC_14") (pintype "unspecified+no_connect"))
    )
    (net (code "413") (name "unconnected-(U400-PD#-Pad16)") (class "Default")
      (node (ref "U400") (pin "16") (pinfunction "PD#_16") (pintype "unspecified+no_connect"))
    )
    (net (code "414") (name "unconnected-(U401-NC-Pad14)") (class "Default")
      (node (ref "U401") (pin "14") (pinfunction "NC_14") (pintype "unspecified+no_connect"))
    )
    (net (code "415") (name "unconnected-(U401-PD#-Pad16)") (class "Default")
      (node (ref "U401") (pin "16") (pinfunction "PD#_16") (pintype "unspecified+no_connect"))
    )
  )
)
